# display-board.net
KiCad netlist of a schematic drawn in EAGLE
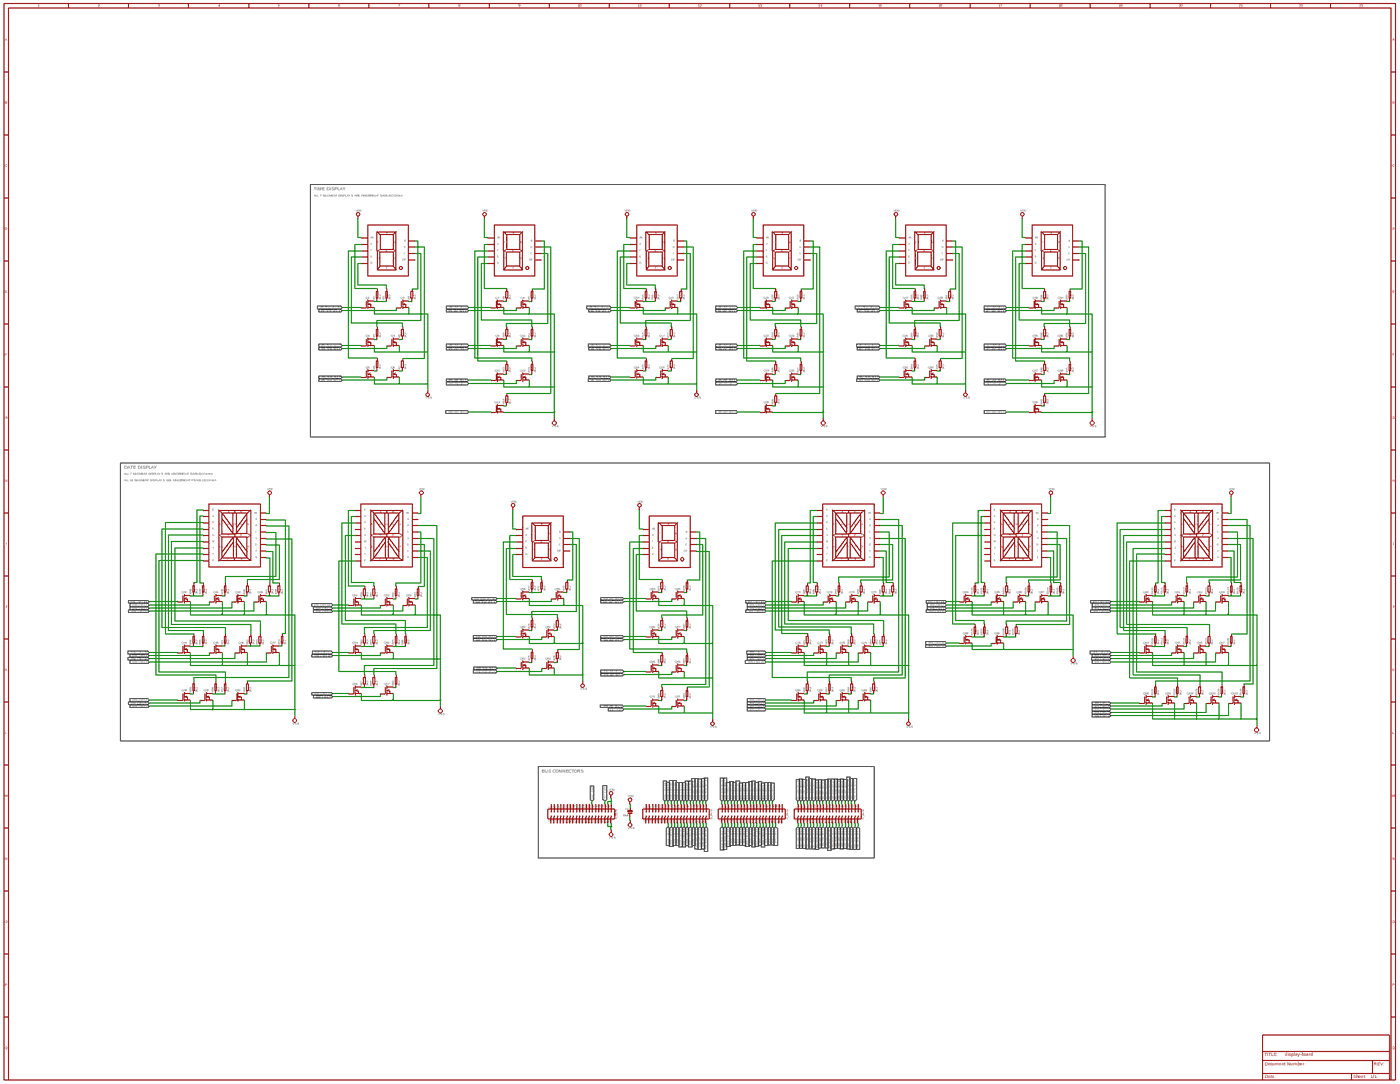
[diagram p0: schematic, sheet 1, overview]
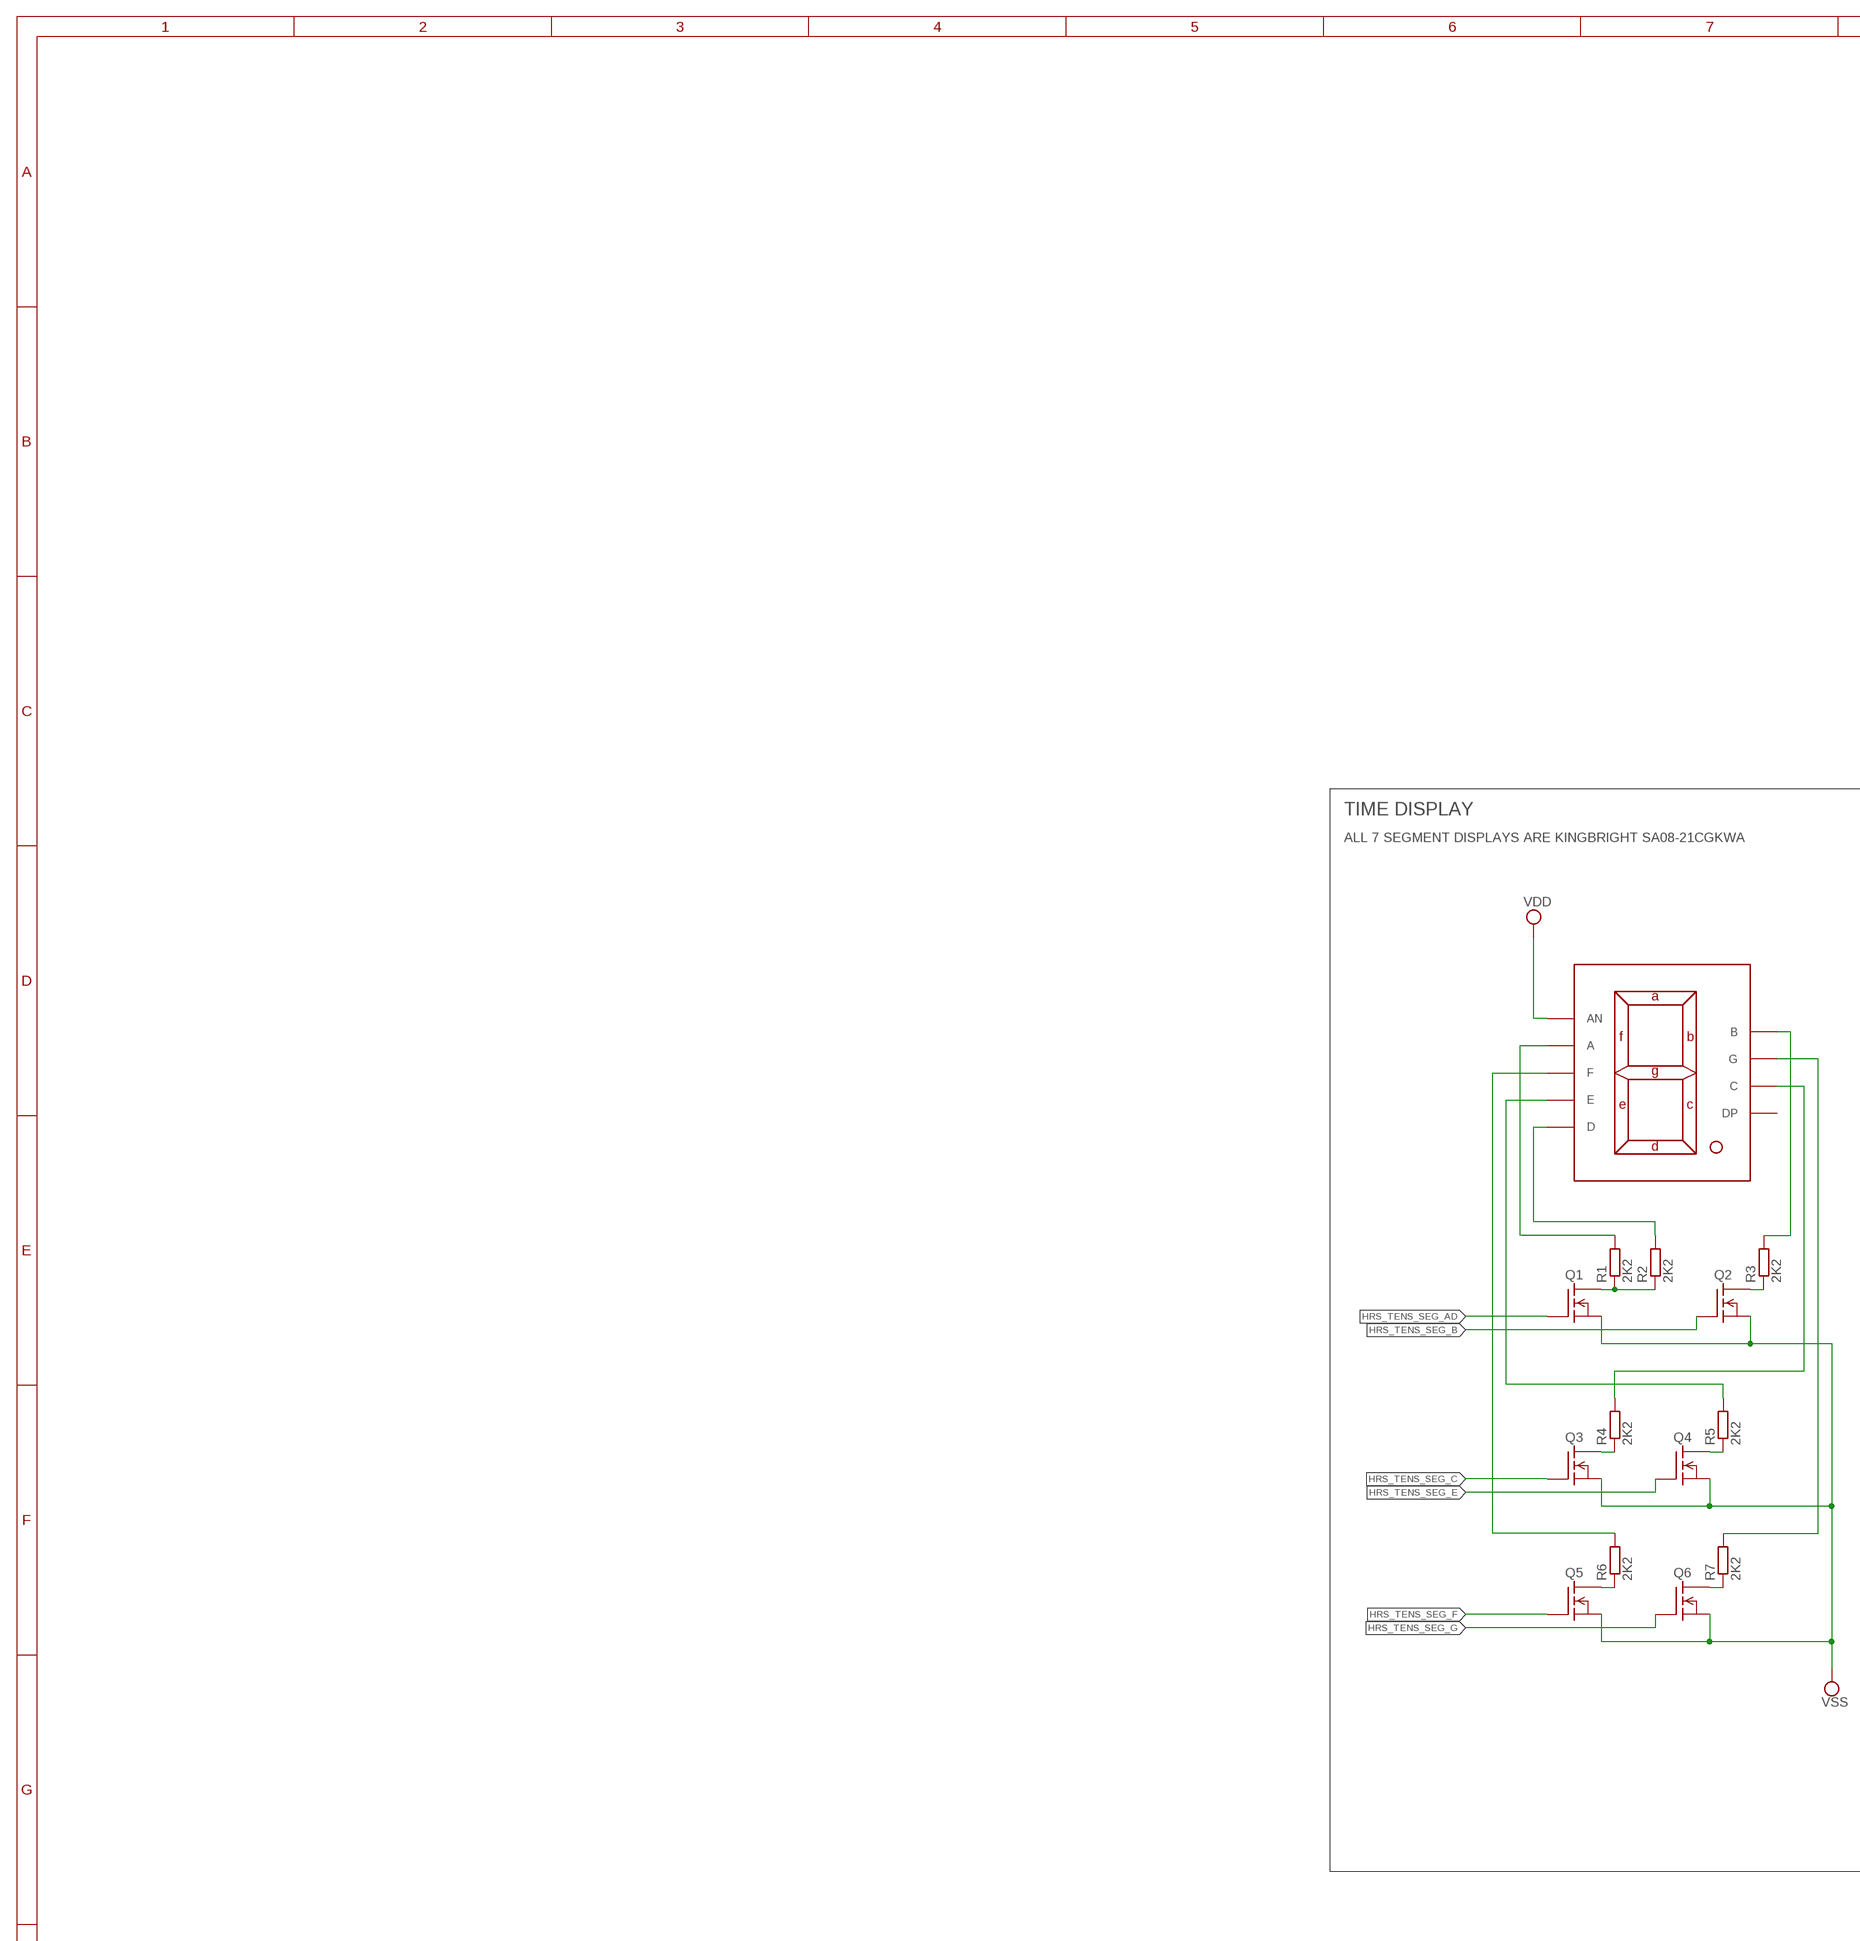
[diagram p1: schematic, sheet 1, part 1 of 6]
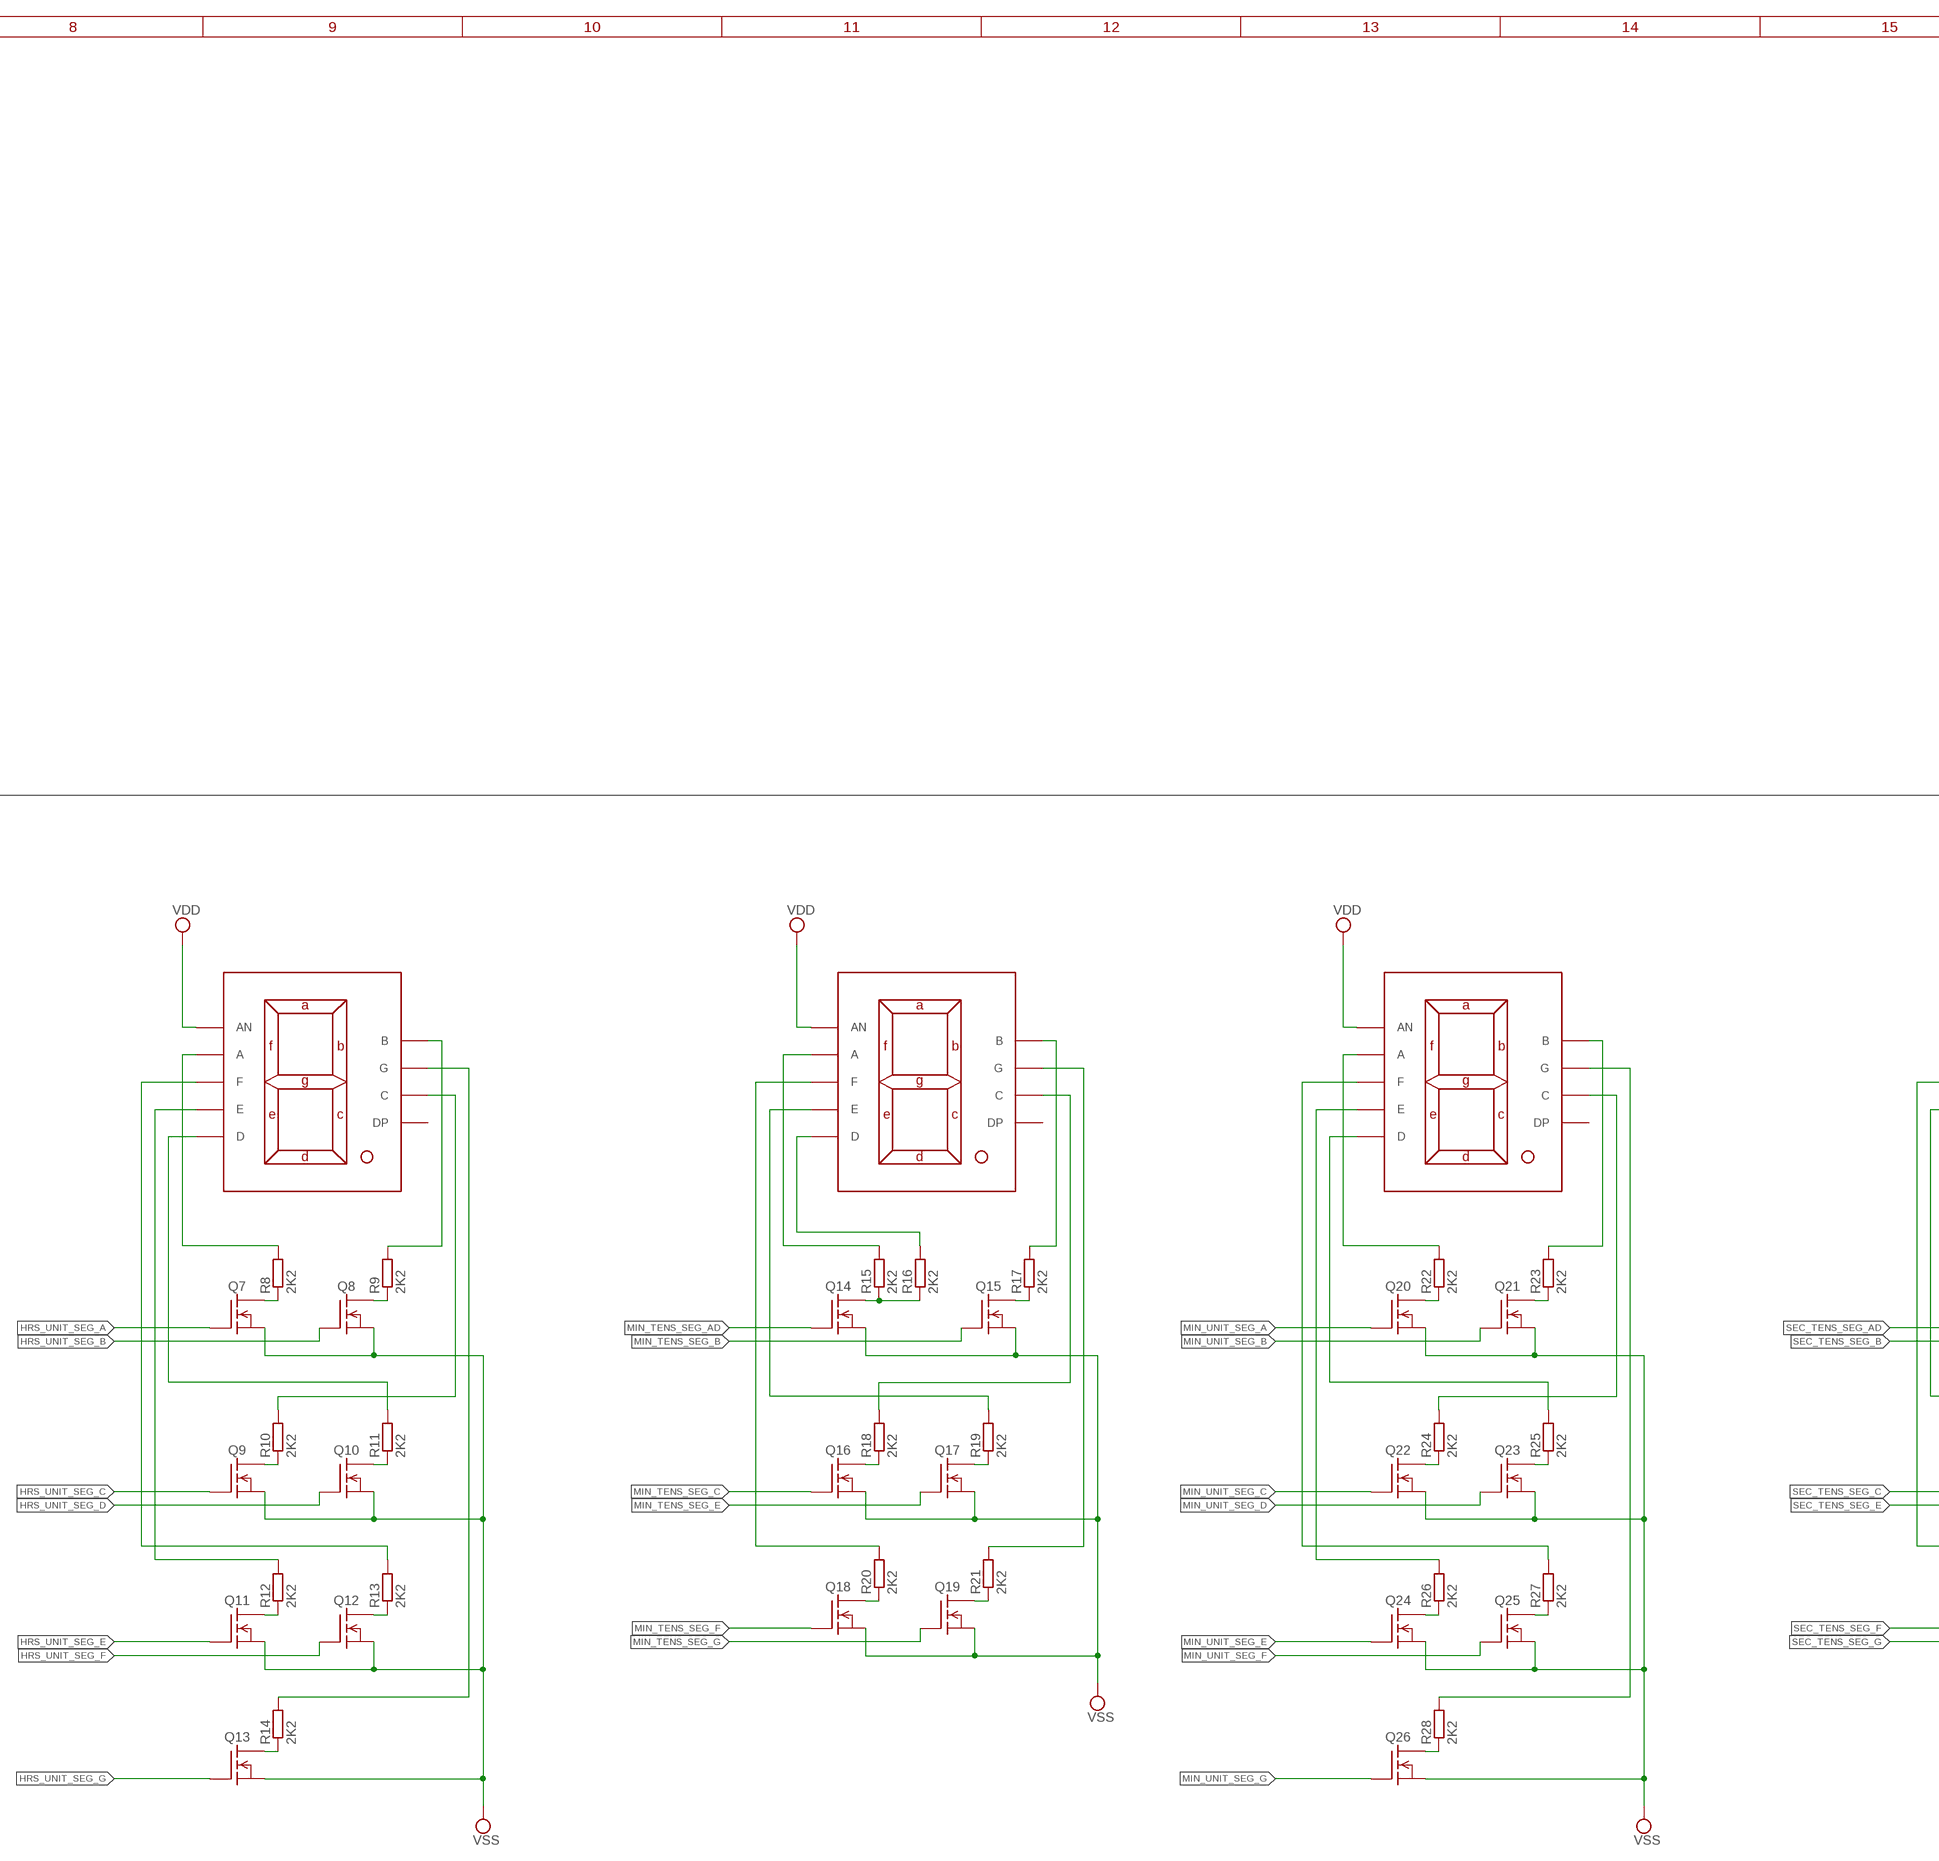
[diagram p2: schematic, sheet 1, part 2 of 6]
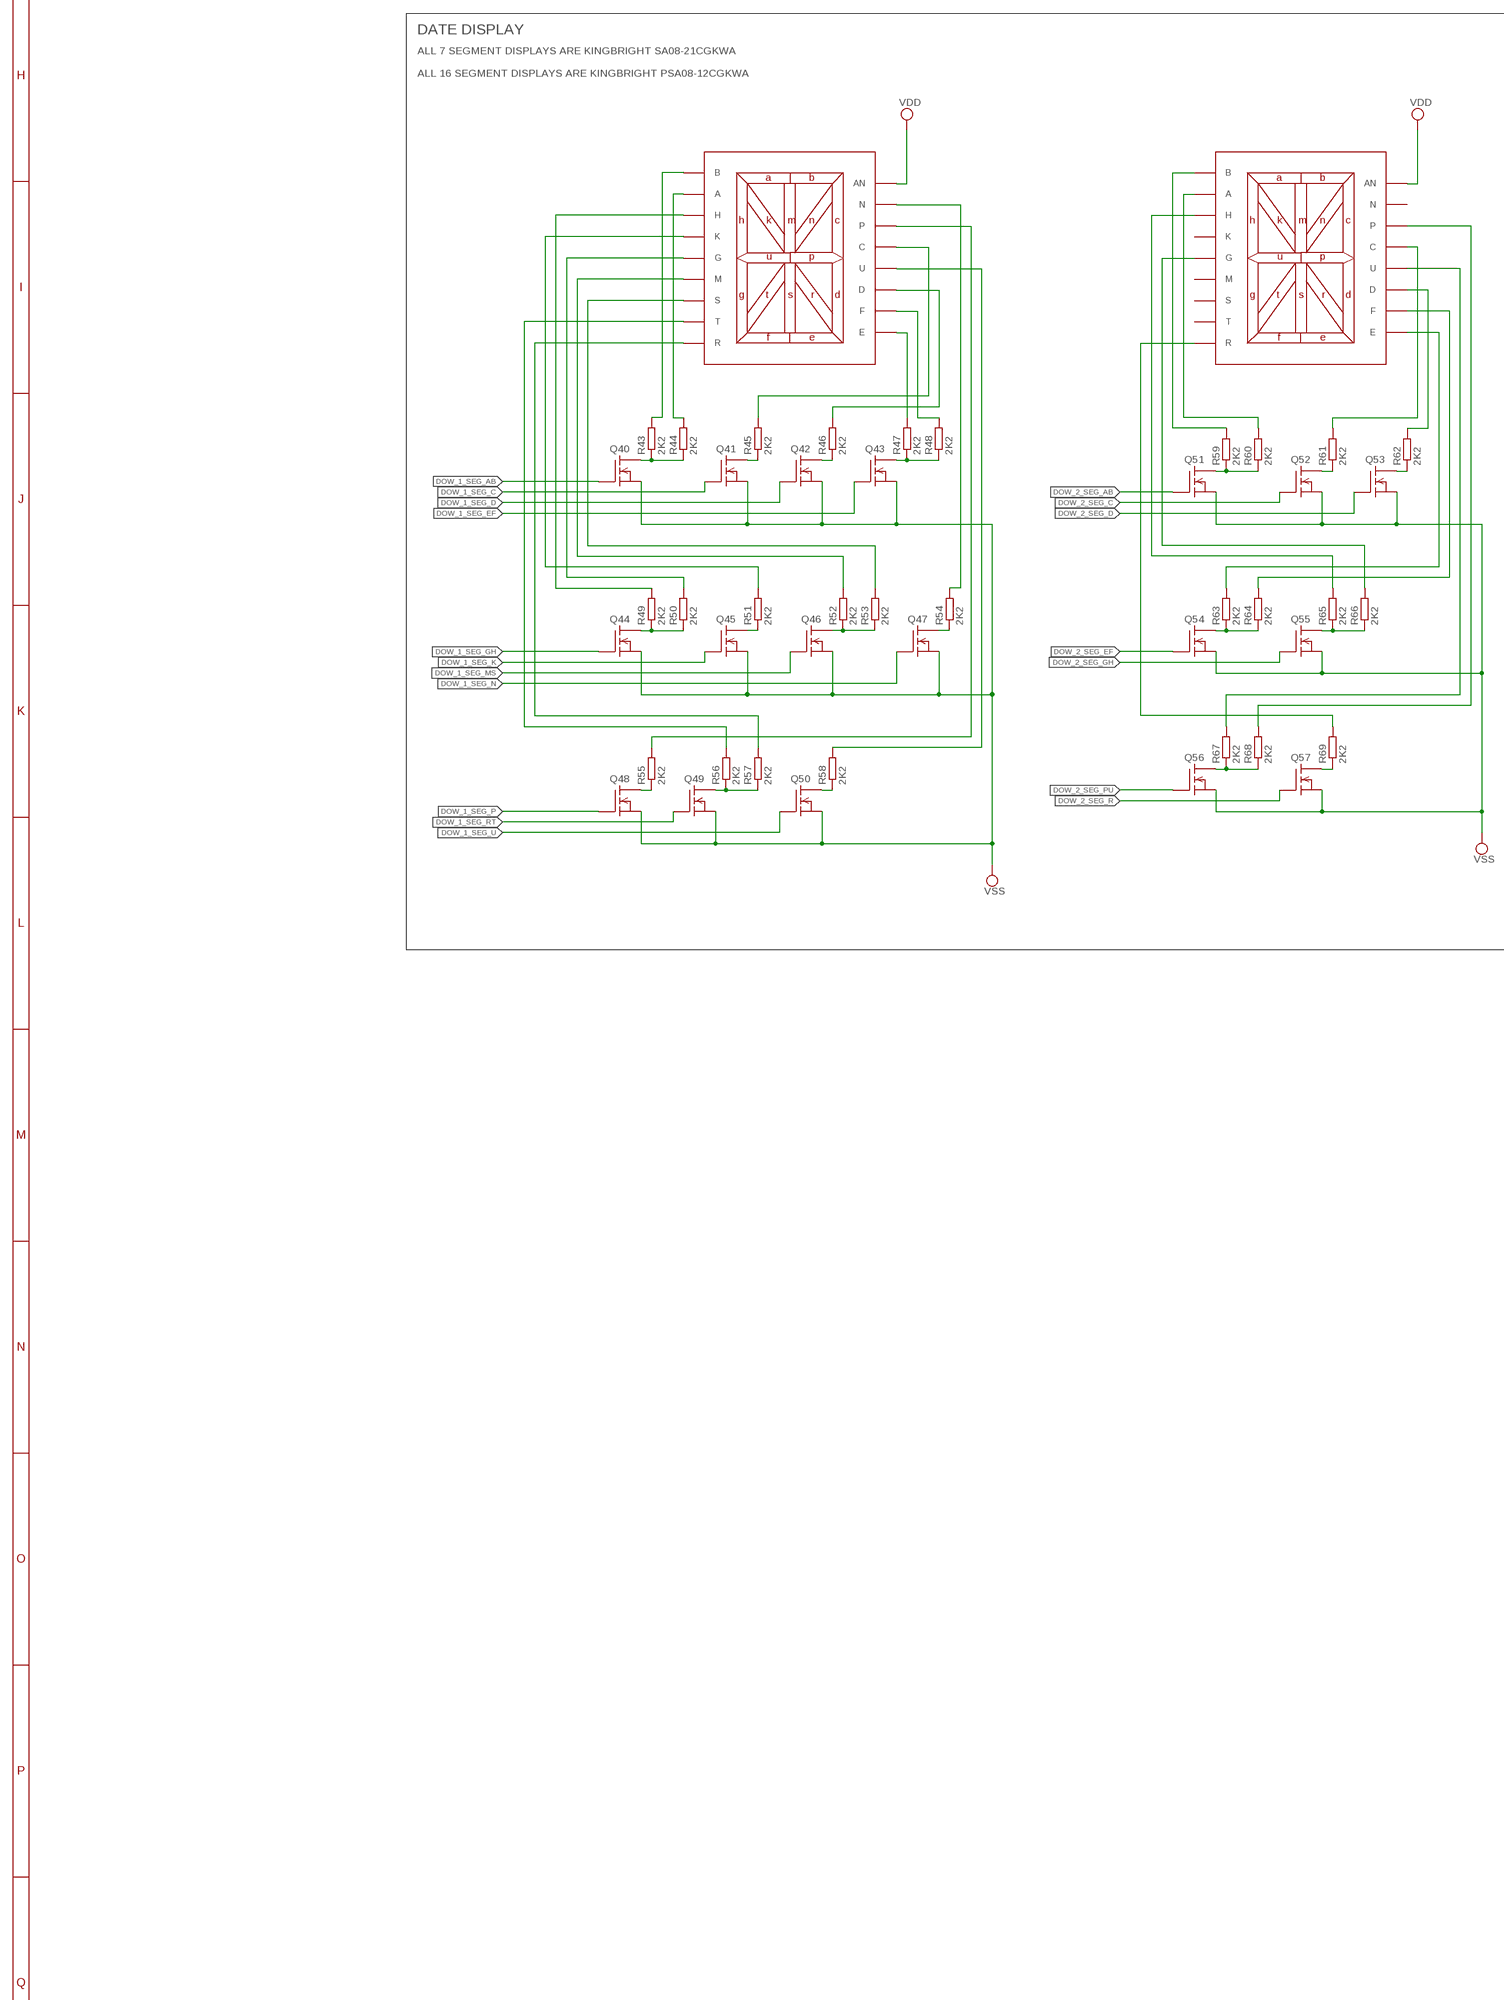
[diagram p3: schematic, sheet 1, part 3 of 6]
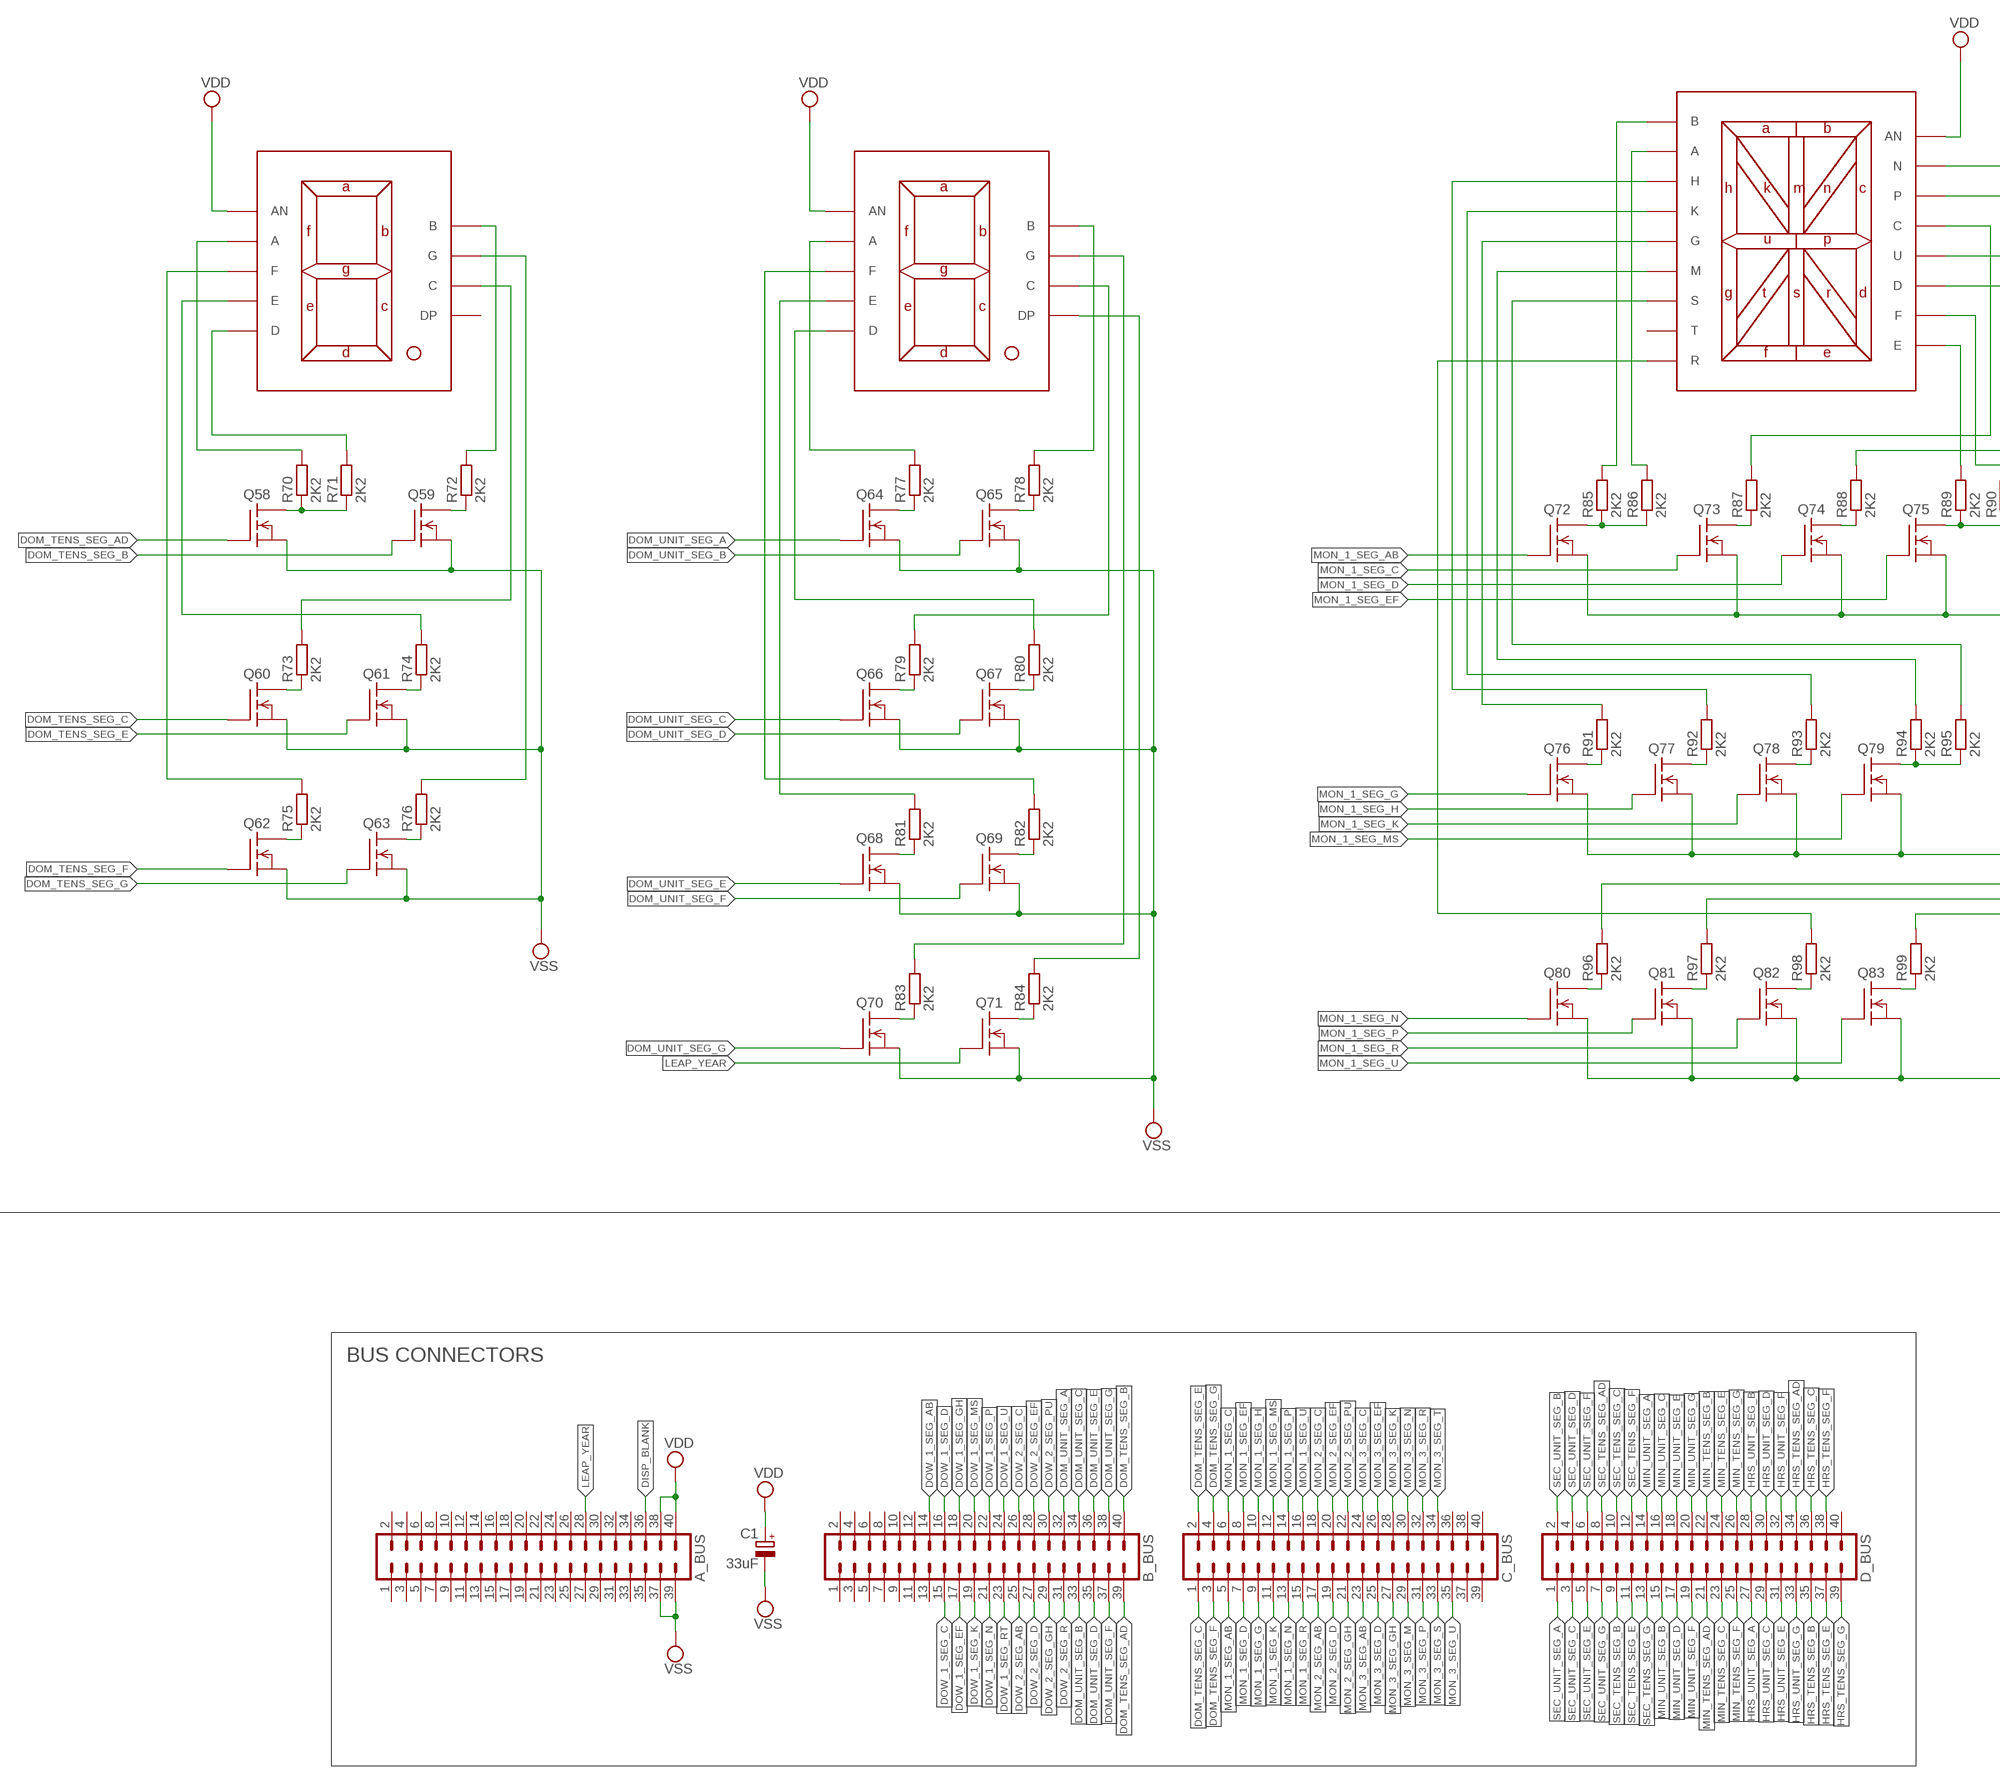
[diagram p4: schematic, sheet 1, part 4 of 6]
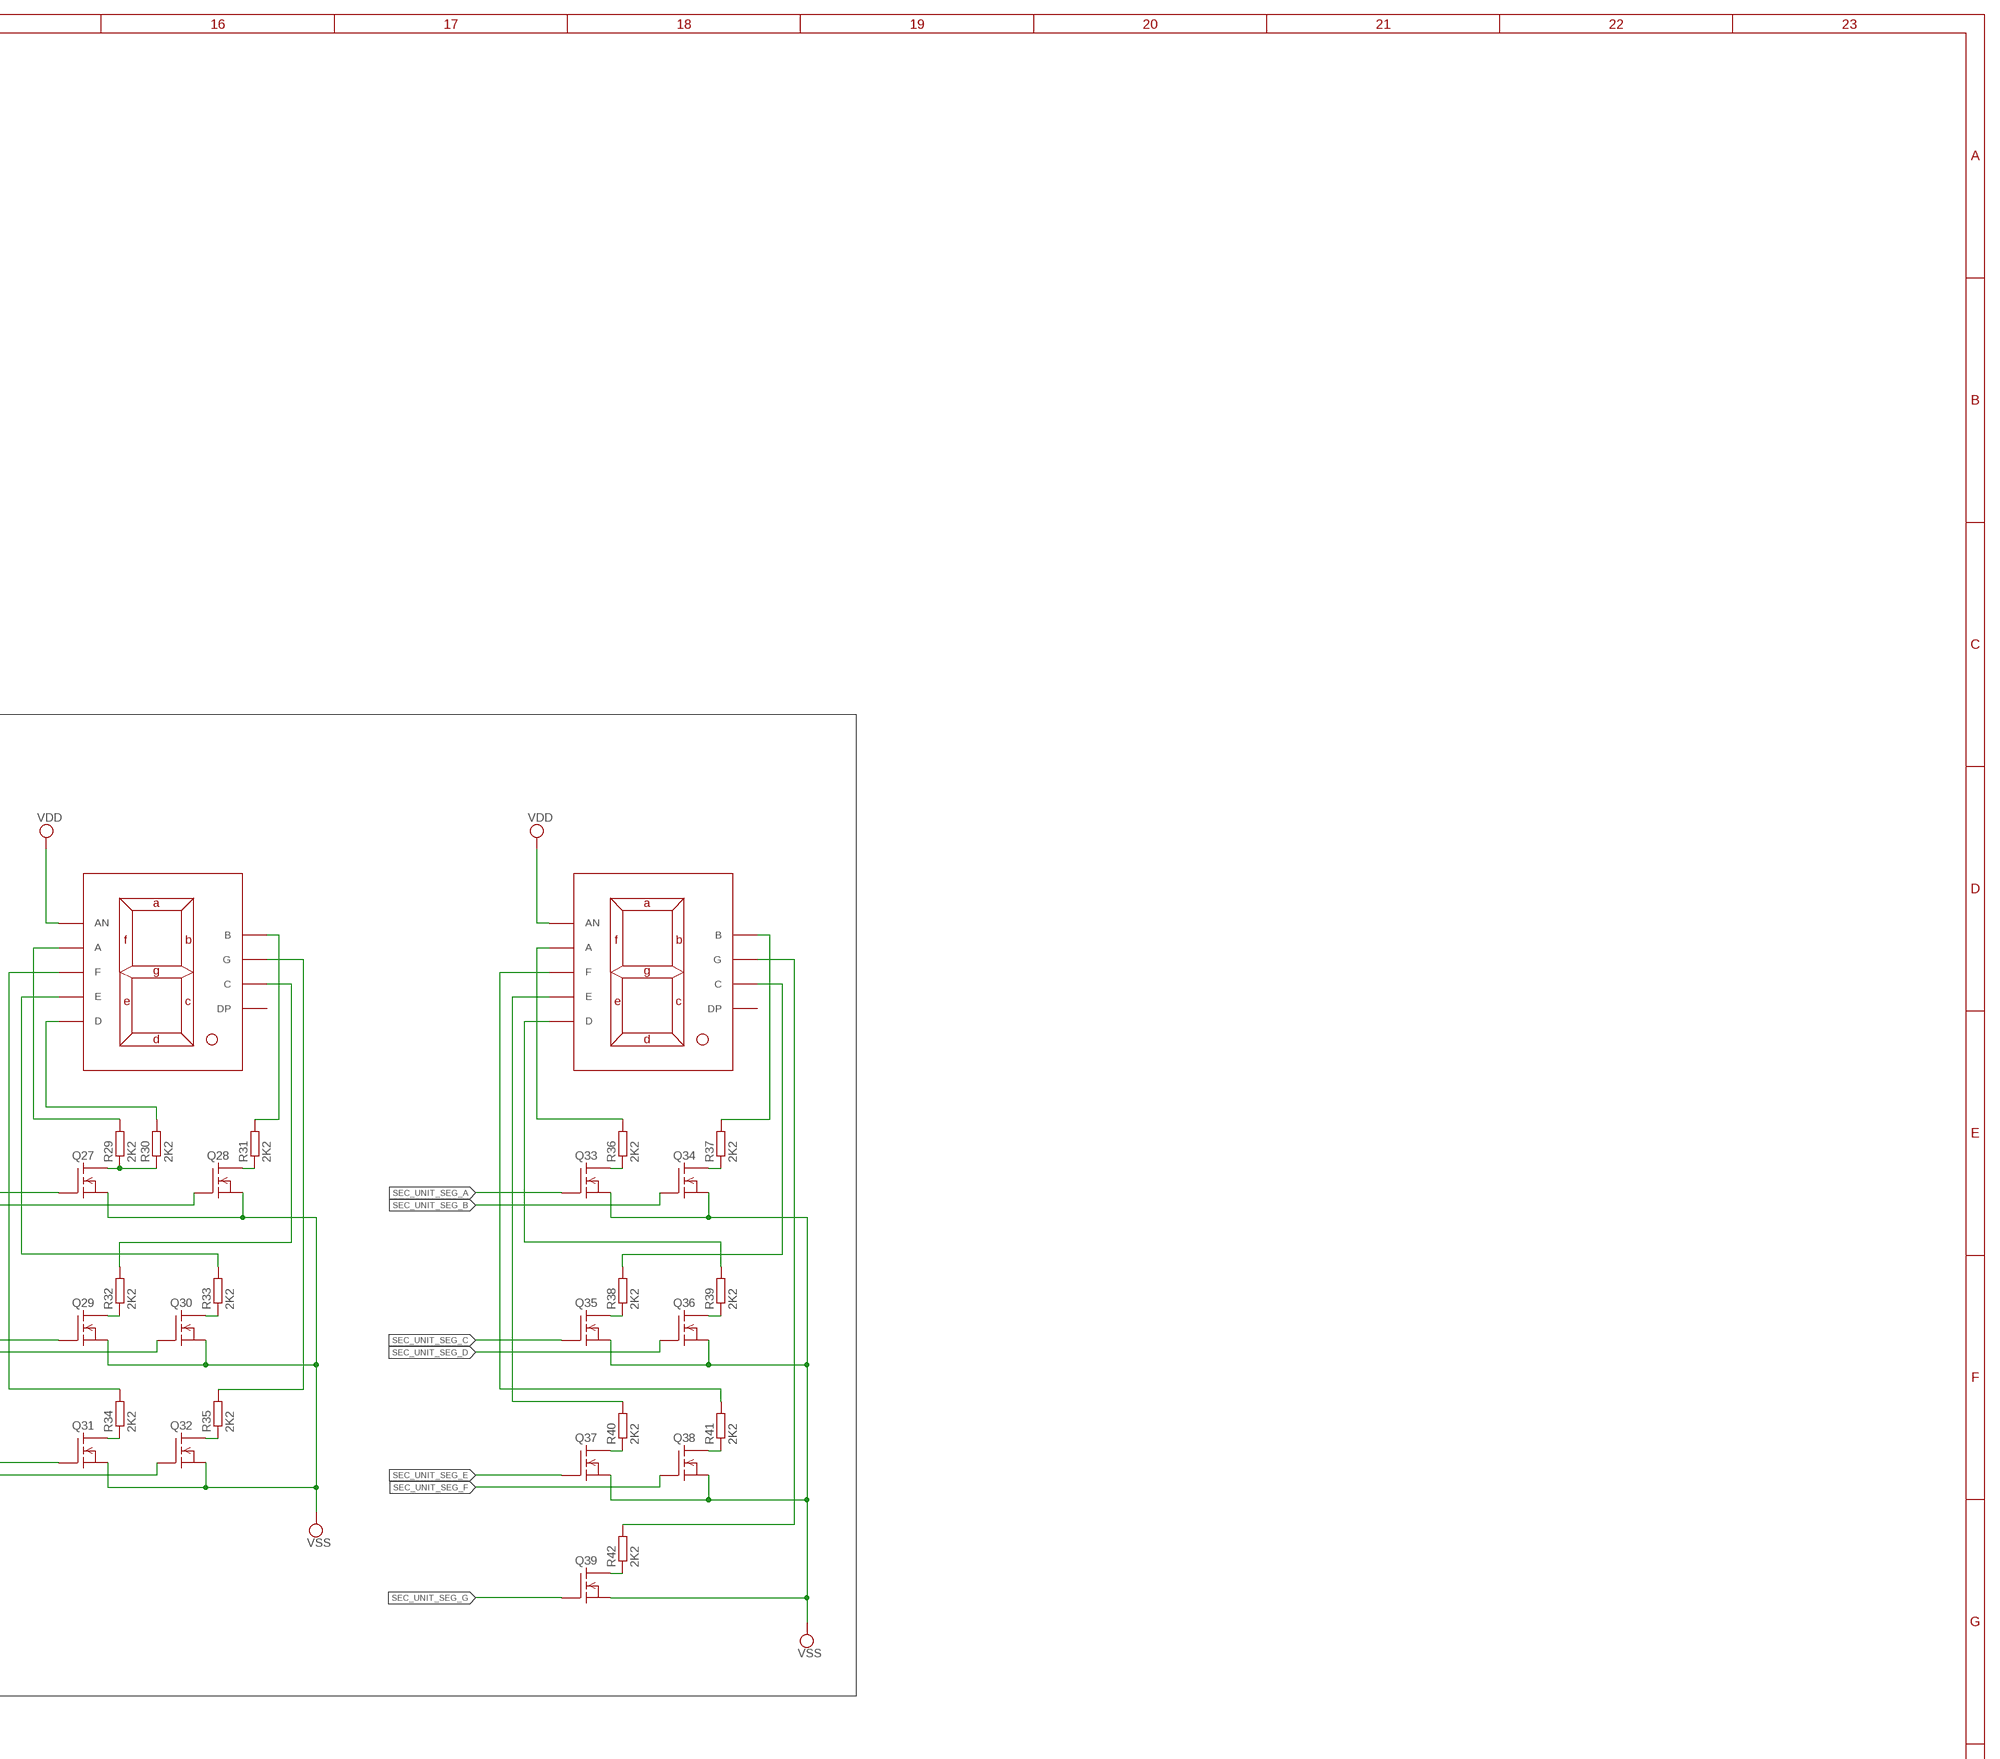
[diagram p5: schematic, sheet 1, part 5 of 6]
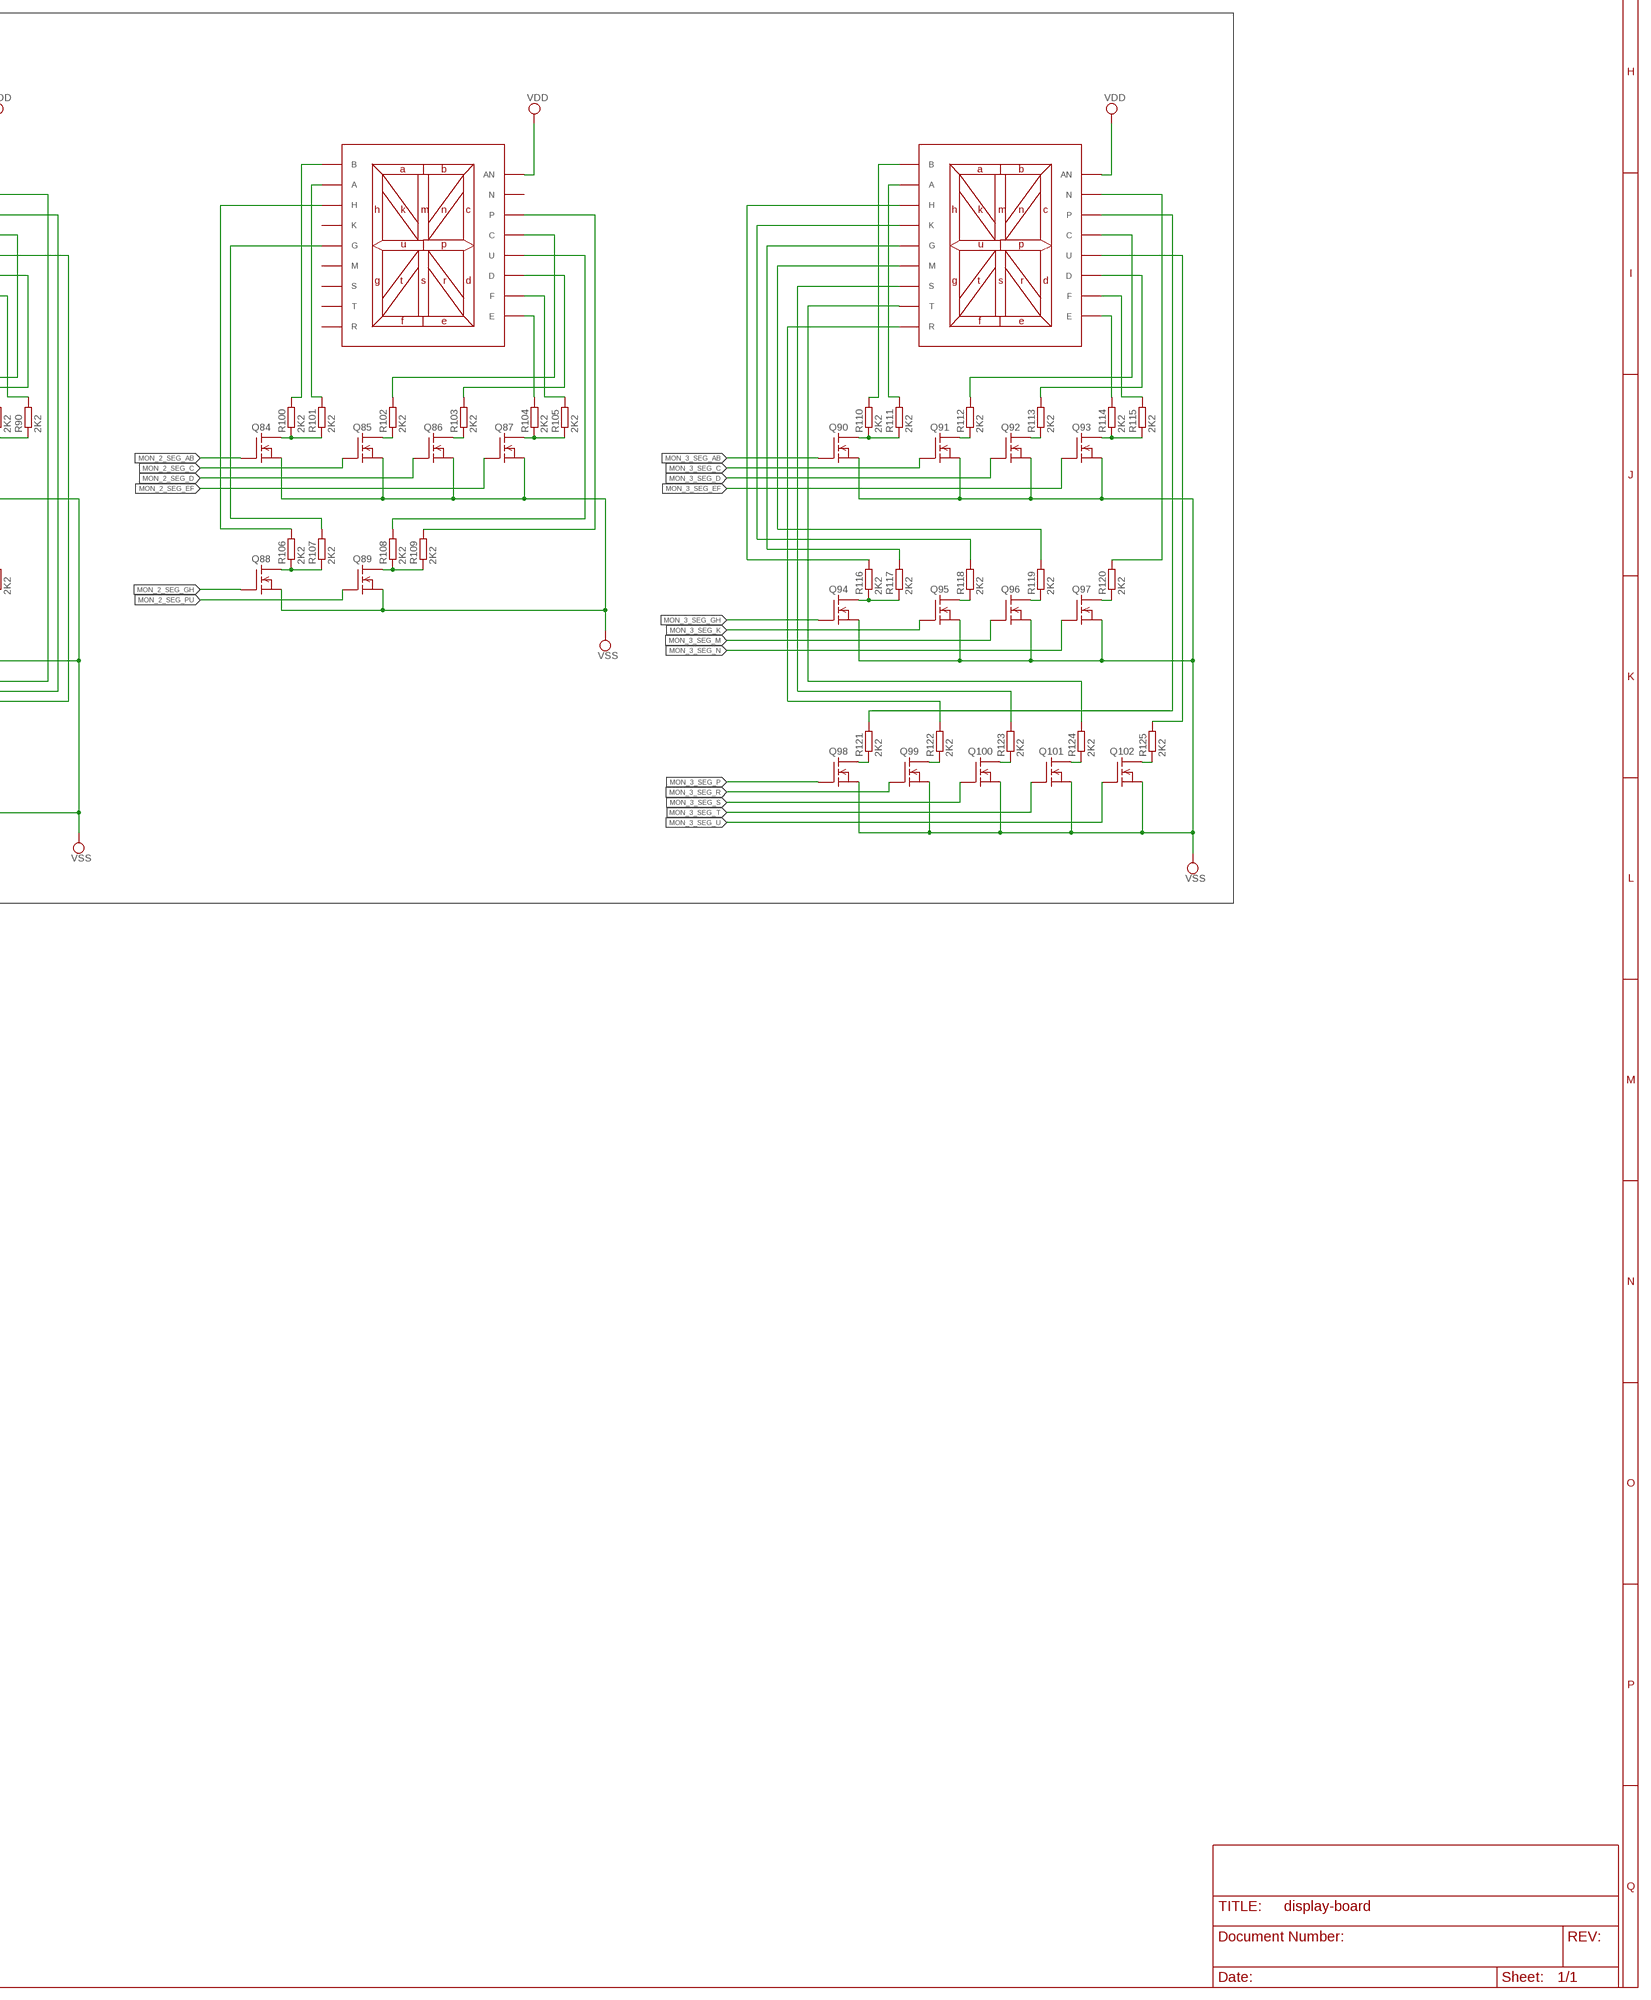
[diagram p6: schematic, sheet 1, part 6 of 6]

(export (version "E")
  (design (tool "Eeschema 10.0.6"))
  (components
    (comp (ref "A_BUS")
      (value "MA20-2")
      (footprint "eagle-import:MA20-2")
      (libsource (lib "eagle-import") (part "MA20-2"))
    )
    (comp (ref "B_BUS")
      (value "MA20-2")
      (footprint "eagle-import:MA20-2")
      (libsource (lib "eagle-import") (part "MA20-2"))
    )
    (comp (ref "C1")
      (value "33uF")
      (footprint "eagle-import:E2,5-6")
      (libsource (lib "eagle-import") (part "CPOL-EUE2.5-6"))
    )
    (comp (ref "C_BUS")
      (value "MA20-2")
      (footprint "eagle-import:MA20-2")
      (libsource (lib "eagle-import") (part "MA20-2"))
    )
    (comp (ref "D_BUS")
      (value "MA20-2")
      (footprint "eagle-import:MA20-2")
      (libsource (lib "eagle-import") (part "MA20-2"))
    )
    (comp (ref "LED1")
      (value "SA08-21CGKWA")
      (footprint "eagle-import:SA08-21CGKWA")
      (libsource (lib "eagle-import") (part "SA08-21CGKWA"))
    )
    (comp (ref "LED2")
      (value "SA08-21CGKWA")
      (footprint "eagle-import:SA08-21CGKWA")
      (libsource (lib "eagle-import") (part "SA08-21CGKWA"))
    )
    (comp (ref "LED3")
      (value "SA08-21CGKWA")
      (footprint "eagle-import:SA08-21CGKWA")
      (libsource (lib "eagle-import") (part "SA08-21CGKWA"))
    )
    (comp (ref "LED4")
      (value "SA08-21CGKWA")
      (footprint "eagle-import:SA08-21CGKWA")
      (libsource (lib "eagle-import") (part "SA08-21CGKWA"))
    )
    (comp (ref "LED5")
      (value "SA08-21CGKWA")
      (footprint "eagle-import:SA08-21CGKWA")
      (libsource (lib "eagle-import") (part "SA08-21CGKWA"))
    )
    (comp (ref "LED6")
      (value "SA08-21CGKWA")
      (footprint "eagle-import:SA08-21CGKWA")
      (libsource (lib "eagle-import") (part "SA08-21CGKWA"))
    )
    (comp (ref "LED7")
      (value "PSA08-12CGKWA")
      (footprint "eagle-import:PSA08-12CGKWA")
      (libsource (lib "eagle-import") (part "PSA08-12CGKWA"))
    )
    (comp (ref "LED8")
      (value "PSA08-12CGKWA")
      (footprint "eagle-import:PSA08-12CGKWA")
      (libsource (lib "eagle-import") (part "PSA08-12CGKWA"))
    )
    (comp (ref "LED9")
      (value "SA08-21CGKWA")
      (footprint "eagle-import:SA08-21CGKWA")
      (libsource (lib "eagle-import") (part "SA08-21CGKWA"))
    )
    (comp (ref "LED10")
      (value "SA08-21CGKWA")
      (footprint "eagle-import:SA08-21CGKWA")
      (libsource (lib "eagle-import") (part "SA08-21CGKWA"))
    )
    (comp (ref "LED11")
      (value "PSA08-12CGKWA")
      (footprint "eagle-import:PSA08-12CGKWA")
      (libsource (lib "eagle-import") (part "PSA08-12CGKWA"))
    )
    (comp (ref "LED12")
      (value "PSA08-12CGKWA")
      (footprint "eagle-import:PSA08-12CGKWA")
      (libsource (lib "eagle-import") (part "PSA08-12CGKWA"))
    )
    (comp (ref "LED13")
      (value "PSA08-12CGKWA")
      (footprint "eagle-import:PSA08-12CGKWA")
      (libsource (lib "eagle-import") (part "PSA08-12CGKWA"))
    )
    (comp (ref "Q1")
      (value "2N7000")
      (footprint "eagle-import:TO-92")
      (libsource (lib "eagle-import") (part "2N7000"))
    )
    (comp (ref "Q2")
      (value "2N7000")
      (footprint "eagle-import:TO-92")
      (libsource (lib "eagle-import") (part "2N7000"))
    )
    (comp (ref "Q3")
      (value "2N7000")
      (footprint "eagle-import:TO-92")
      (libsource (lib "eagle-import") (part "2N7000"))
    )
    (comp (ref "Q4")
      (value "2N7000")
      (footprint "eagle-import:TO-92")
      (libsource (lib "eagle-import") (part "2N7000"))
    )
    (comp (ref "Q5")
      (value "2N7000")
      (footprint "eagle-import:TO-92")
      (libsource (lib "eagle-import") (part "2N7000"))
    )
    (comp (ref "Q6")
      (value "2N7000")
      (footprint "eagle-import:TO-92")
      (libsource (lib "eagle-import") (part "2N7000"))
    )
    (comp (ref "Q7")
      (value "2N7000")
      (footprint "eagle-import:TO-92")
      (libsource (lib "eagle-import") (part "2N7000"))
    )
    (comp (ref "Q8")
      (value "2N7000")
      (footprint "eagle-import:TO-92")
      (libsource (lib "eagle-import") (part "2N7000"))
    )
    (comp (ref "Q9")
      (value "2N7000")
      (footprint "eagle-import:TO-92")
      (libsource (lib "eagle-import") (part "2N7000"))
    )
    (comp (ref "Q10")
      (value "2N7000")
      (footprint "eagle-import:TO-92")
      (libsource (lib "eagle-import") (part "2N7000"))
    )
    (comp (ref "Q11")
      (value "2N7000")
      (footprint "eagle-import:TO-92")
      (libsource (lib "eagle-import") (part "2N7000"))
    )
    (comp (ref "Q12")
      (value "2N7000")
      (footprint "eagle-import:TO-92")
      (libsource (lib "eagle-import") (part "2N7000"))
    )
    (comp (ref "Q13")
      (value "2N7000")
      (footprint "eagle-import:TO-92")
      (libsource (lib "eagle-import") (part "2N7000"))
    )
    (comp (ref "Q14")
      (value "2N7000")
      (footprint "eagle-import:TO-92")
      (libsource (lib "eagle-import") (part "2N7000"))
    )
    (comp (ref "Q15")
      (value "2N7000")
      (footprint "eagle-import:TO-92")
      (libsource (lib "eagle-import") (part "2N7000"))
    )
    (comp (ref "Q16")
      (value "2N7000")
      (footprint "eagle-import:TO-92")
      (libsource (lib "eagle-import") (part "2N7000"))
    )
    (comp (ref "Q17")
      (value "2N7000")
      (footprint "eagle-import:TO-92")
      (libsource (lib "eagle-import") (part "2N7000"))
    )
    (comp (ref "Q18")
      (value "2N7000")
      (footprint "eagle-import:TO-92")
      (libsource (lib "eagle-import") (part "2N7000"))
    )
    (comp (ref "Q19")
      (value "2N7000")
      (footprint "eagle-import:TO-92")
      (libsource (lib "eagle-import") (part "2N7000"))
    )
    (comp (ref "Q20")
      (value "2N7000")
      (footprint "eagle-import:TO-92")
      (libsource (lib "eagle-import") (part "2N7000"))
    )
    (comp (ref "Q21")
      (value "2N7000")
      (footprint "eagle-import:TO-92")
      (libsource (lib "eagle-import") (part "2N7000"))
    )
    (comp (ref "Q22")
      (value "2N7000")
      (footprint "eagle-import:TO-92")
      (libsource (lib "eagle-import") (part "2N7000"))
    )
    (comp (ref "Q23")
      (value "2N7000")
      (footprint "eagle-import:TO-92")
      (libsource (lib "eagle-import") (part "2N7000"))
    )
    (comp (ref "Q24")
      (value "2N7000")
      (footprint "eagle-import:TO-92")
      (libsource (lib "eagle-import") (part "2N7000"))
    )
    (comp (ref "Q25")
      (value "2N7000")
      (footprint "eagle-import:TO-92")
      (libsource (lib "eagle-import") (part "2N7000"))
    )
    (comp (ref "Q26")
      (value "2N7000")
      (footprint "eagle-import:TO-92")
      (libsource (lib "eagle-import") (part "2N7000"))
    )
    (comp (ref "Q27")
      (value "2N7000")
      (footprint "eagle-import:TO-92")
      (libsource (lib "eagle-import") (part "2N7000"))
    )
    (comp (ref "Q28")
      (value "2N7000")
      (footprint "eagle-import:TO-92")
      (libsource (lib "eagle-import") (part "2N7000"))
    )
    (comp (ref "Q29")
      (value "2N7000")
      (footprint "eagle-import:TO-92")
      (libsource (lib "eagle-import") (part "2N7000"))
    )
    (comp (ref "Q30")
      (value "2N7000")
      (footprint "eagle-import:TO-92")
      (libsource (lib "eagle-import") (part "2N7000"))
    )
    (comp (ref "Q31")
      (value "2N7000")
      (footprint "eagle-import:TO-92")
      (libsource (lib "eagle-import") (part "2N7000"))
    )
    (comp (ref "Q32")
      (value "2N7000")
      (footprint "eagle-import:TO-92")
      (libsource (lib "eagle-import") (part "2N7000"))
    )
    (comp (ref "Q33")
      (value "2N7000")
      (footprint "eagle-import:TO-92")
      (libsource (lib "eagle-import") (part "2N7000"))
    )
    (comp (ref "Q34")
      (value "2N7000")
      (footprint "eagle-import:TO-92")
      (libsource (lib "eagle-import") (part "2N7000"))
    )
    (comp (ref "Q35")
      (value "2N7000")
      (footprint "eagle-import:TO-92")
      (libsource (lib "eagle-import") (part "2N7000"))
    )
    (comp (ref "Q36")
      (value "2N7000")
      (footprint "eagle-import:TO-92")
      (libsource (lib "eagle-import") (part "2N7000"))
    )
    (comp (ref "Q37")
      (value "2N7000")
      (footprint "eagle-import:TO-92")
      (libsource (lib "eagle-import") (part "2N7000"))
    )
    (comp (ref "Q38")
      (value "2N7000")
      (footprint "eagle-import:TO-92")
      (libsource (lib "eagle-import") (part "2N7000"))
    )
    (comp (ref "Q39")
      (value "2N7000")
      (footprint "eagle-import:TO-92")
      (libsource (lib "eagle-import") (part "2N7000"))
    )
    (comp (ref "Q40")
      (value "2N7000")
      (footprint "eagle-import:TO-92")
      (libsource (lib "eagle-import") (part "2N7000"))
    )
    (comp (ref "Q41")
      (value "2N7000")
      (footprint "eagle-import:TO-92")
      (libsource (lib "eagle-import") (part "2N7000"))
    )
    (comp (ref "Q42")
      (value "2N7000")
      (footprint "eagle-import:TO-92")
      (libsource (lib "eagle-import") (part "2N7000"))
    )
    (comp (ref "Q43")
      (value "2N7000")
      (footprint "eagle-import:TO-92")
      (libsource (lib "eagle-import") (part "2N7000"))
    )
    (comp (ref "Q44")
      (value "2N7000")
      (footprint "eagle-import:TO-92")
      (libsource (lib "eagle-import") (part "2N7000"))
    )
    (comp (ref "Q45")
      (value "2N7000")
      (footprint "eagle-import:TO-92")
      (libsource (lib "eagle-import") (part "2N7000"))
    )
    (comp (ref "Q46")
      (value "2N7000")
      (footprint "eagle-import:TO-92")
      (libsource (lib "eagle-import") (part "2N7000"))
    )
    (comp (ref "Q47")
      (value "2N7000")
      (footprint "eagle-import:TO-92")
      (libsource (lib "eagle-import") (part "2N7000"))
    )
    (comp (ref "Q48")
      (value "2N7000")
      (footprint "eagle-import:TO-92")
      (libsource (lib "eagle-import") (part "2N7000"))
    )
    (comp (ref "Q49")
      (value "2N7000")
      (footprint "eagle-import:TO-92")
      (libsource (lib "eagle-import") (part "2N7000"))
    )
    (comp (ref "Q50")
      (value "2N7000")
      (footprint "eagle-import:TO-92")
      (libsource (lib "eagle-import") (part "2N7000"))
    )
    (comp (ref "Q51")
      (value "2N7000")
      (footprint "eagle-import:TO-92")
      (libsource (lib "eagle-import") (part "2N7000"))
    )
    (comp (ref "Q52")
      (value "2N7000")
      (footprint "eagle-import:TO-92")
      (libsource (lib "eagle-import") (part "2N7000"))
    )
    (comp (ref "Q53")
      (value "2N7000")
      (footprint "eagle-import:TO-92")
      (libsource (lib "eagle-import") (part "2N7000"))
    )
    (comp (ref "Q54")
      (value "2N7000")
      (footprint "eagle-import:TO-92")
      (libsource (lib "eagle-import") (part "2N7000"))
    )
    (comp (ref "Q55")
      (value "2N7000")
      (footprint "eagle-import:TO-92")
      (libsource (lib "eagle-import") (part "2N7000"))
    )
    (comp (ref "Q56")
      (value "2N7000")
      (footprint "eagle-import:TO-92")
      (libsource (lib "eagle-import") (part "2N7000"))
    )
    (comp (ref "Q57")
      (value "2N7000")
      (footprint "eagle-import:TO-92")
      (libsource (lib "eagle-import") (part "2N7000"))
    )
    (comp (ref "Q58")
      (value "2N7000")
      (footprint "eagle-import:TO-92")
      (libsource (lib "eagle-import") (part "2N7000"))
    )
    (comp (ref "Q59")
      (value "2N7000")
      (footprint "eagle-import:TO-92")
      (libsource (lib "eagle-import") (part "2N7000"))
    )
    (comp (ref "Q60")
      (value "2N7000")
      (footprint "eagle-import:TO-92")
      (libsource (lib "eagle-import") (part "2N7000"))
    )
    (comp (ref "Q61")
      (value "2N7000")
      (footprint "eagle-import:TO-92")
      (libsource (lib "eagle-import") (part "2N7000"))
    )
    (comp (ref "Q62")
      (value "2N7000")
      (footprint "eagle-import:TO-92")
      (libsource (lib "eagle-import") (part "2N7000"))
    )
    (comp (ref "Q63")
      (value "2N7000")
      (footprint "eagle-import:TO-92")
      (libsource (lib "eagle-import") (part "2N7000"))
    )
    (comp (ref "Q64")
      (value "2N7000")
      (footprint "eagle-import:TO-92")
      (libsource (lib "eagle-import") (part "2N7000"))
    )
    (comp (ref "Q65")
      (value "2N7000")
      (footprint "eagle-import:TO-92")
      (libsource (lib "eagle-import") (part "2N7000"))
    )
    (comp (ref "Q66")
      (value "2N7000")
      (footprint "eagle-import:TO-92")
      (libsource (lib "eagle-import") (part "2N7000"))
    )
    (comp (ref "Q67")
      (value "2N7000")
      (footprint "eagle-import:TO-92")
      (libsource (lib "eagle-import") (part "2N7000"))
    )
    (comp (ref "Q68")
      (value "2N7000")
      (footprint "eagle-import:TO-92")
      (libsource (lib "eagle-import") (part "2N7000"))
    )
    (comp (ref "Q69")
      (value "2N7000")
      (footprint "eagle-import:TO-92")
      (libsource (lib "eagle-import") (part "2N7000"))
    )
    (comp (ref "Q70")
      (value "2N7000")
      (footprint "eagle-import:TO-92")
      (libsource (lib "eagle-import") (part "2N7000"))
    )
    (comp (ref "Q71")
      (value "2N7000")
      (footprint "eagle-import:TO-92")
      (libsource (lib "eagle-import") (part "2N7000"))
    )
    (comp (ref "Q72")
      (value "2N7000")
      (footprint "eagle-import:TO-92")
      (libsource (lib "eagle-import") (part "2N7000"))
    )
    (comp (ref "Q73")
      (value "2N7000")
      (footprint "eagle-import:TO-92")
      (libsource (lib "eagle-import") (part "2N7000"))
    )
    (comp (ref "Q74")
      (value "2N7000")
      (footprint "eagle-import:TO-92")
      (libsource (lib "eagle-import") (part "2N7000"))
    )
    (comp (ref "Q75")
      (value "2N7000")
      (footprint "eagle-import:TO-92")
      (libsource (lib "eagle-import") (part "2N7000"))
    )
    (comp (ref "Q76")
      (value "2N7000")
      (footprint "eagle-import:TO-92")
      (libsource (lib "eagle-import") (part "2N7000"))
    )
    (comp (ref "Q77")
      (value "2N7000")
      (footprint "eagle-import:TO-92")
      (libsource (lib "eagle-import") (part "2N7000"))
    )
    (comp (ref "Q78")
      (value "2N7000")
      (footprint "eagle-import:TO-92")
      (libsource (lib "eagle-import") (part "2N7000"))
    )
    (comp (ref "Q79")
      (value "2N7000")
      (footprint "eagle-import:TO-92")
      (libsource (lib "eagle-import") (part "2N7000"))
    )
    (comp (ref "Q80")
      (value "2N7000")
      (footprint "eagle-import:TO-92")
      (libsource (lib "eagle-import") (part "2N7000"))
    )
    (comp (ref "Q81")
      (value "2N7000")
      (footprint "eagle-import:TO-92")
      (libsource (lib "eagle-import") (part "2N7000"))
    )
    (comp (ref "Q82")
      (value "2N7000")
      (footprint "eagle-import:TO-92")
      (libsource (lib "eagle-import") (part "2N7000"))
    )
    (comp (ref "Q83")
      (value "2N7000")
      (footprint "eagle-import:TO-92")
      (libsource (lib "eagle-import") (part "2N7000"))
    )
    (comp (ref "Q84")
      (value "2N7000")
      (footprint "eagle-import:TO-92")
      (libsource (lib "eagle-import") (part "2N7000"))
    )
    (comp (ref "Q85")
      (value "2N7000")
      (footprint "eagle-import:TO-92")
      (libsource (lib "eagle-import") (part "2N7000"))
    )
    (comp (ref "Q86")
      (value "2N7000")
      (footprint "eagle-import:TO-92")
      (libsource (lib "eagle-import") (part "2N7000"))
    )
    (comp (ref "Q87")
      (value "2N7000")
      (footprint "eagle-import:TO-92")
      (libsource (lib "eagle-import") (part "2N7000"))
    )
    (comp (ref "Q88")
      (value "2N7000")
      (footprint "eagle-import:TO-92")
      (libsource (lib "eagle-import") (part "2N7000"))
    )
    (comp (ref "Q89")
      (value "2N7000")
      (footprint "eagle-import:TO-92")
      (libsource (lib "eagle-import") (part "2N7000"))
    )
    (comp (ref "Q90")
      (value "2N7000")
      (footprint "eagle-import:TO-92")
      (libsource (lib "eagle-import") (part "2N7000"))
    )
    (comp (ref "Q91")
      (value "2N7000")
      (footprint "eagle-import:TO-92")
      (libsource (lib "eagle-import") (part "2N7000"))
    )
    (comp (ref "Q92")
      (value "2N7000")
      (footprint "eagle-import:TO-92")
      (libsource (lib "eagle-import") (part "2N7000"))
    )
    (comp (ref "Q93")
      (value "2N7000")
      (footprint "eagle-import:TO-92")
      (libsource (lib "eagle-import") (part "2N7000"))
    )
    (comp (ref "Q94")
      (value "2N7000")
      (footprint "eagle-import:TO-92")
      (libsource (lib "eagle-import") (part "2N7000"))
    )
    (comp (ref "Q95")
      (value "2N7000")
      (footprint "eagle-import:TO-92")
      (libsource (lib "eagle-import") (part "2N7000"))
    )
    (comp (ref "Q96")
      (value "2N7000")
      (footprint "eagle-import:TO-92")
      (libsource (lib "eagle-import") (part "2N7000"))
    )
    (comp (ref "Q97")
      (value "2N7000")
      (footprint "eagle-import:TO-92")
      (libsource (lib "eagle-import") (part "2N7000"))
    )
    (comp (ref "Q98")
      (value "2N7000")
      (footprint "eagle-import:TO-92")
      (libsource (lib "eagle-import") (part "2N7000"))
    )
    (comp (ref "Q99")
      (value "2N7000")
      (footprint "eagle-import:TO-92")
      (libsource (lib "eagle-import") (part "2N7000"))
    )
    (comp (ref "Q100")
      (value "2N7000")
      (footprint "eagle-import:TO-92")
      (libsource (lib "eagle-import") (part "2N7000"))
    )
    (comp (ref "Q101")
      (value "2N7000")
      (footprint "eagle-import:TO-92")
      (libsource (lib "eagle-import") (part "2N7000"))
    )
    (comp (ref "Q102")
      (value "2N7000")
      (footprint "eagle-import:TO-92")
      (libsource (lib "eagle-import") (part "2N7000"))
    )
    (comp (ref "R1")
      (value "2K2")
      (footprint "eagle-import:0207_2V")
      (libsource (lib "eagle-import") (part "R-EU_0207/2V"))
    )
    (comp (ref "R2")
      (value "2K2")
      (footprint "eagle-import:0207_2V")
      (libsource (lib "eagle-import") (part "R-EU_0207/2V"))
    )
    (comp (ref "R3")
      (value "2K2")
      (footprint "eagle-import:0207_2V")
      (libsource (lib "eagle-import") (part "R-EU_0207/2V"))
    )
    (comp (ref "R4")
      (value "2K2")
      (footprint "eagle-import:0207_2V")
      (libsource (lib "eagle-import") (part "R-EU_0207/2V"))
    )
    (comp (ref "R5")
      (value "2K2")
      (footprint "eagle-import:0207_2V")
      (libsource (lib "eagle-import") (part "R-EU_0207/2V"))
    )
    (comp (ref "R6")
      (value "2K2")
      (footprint "eagle-import:0207_2V")
      (libsource (lib "eagle-import") (part "R-EU_0207/2V"))
    )
    (comp (ref "R7")
      (value "2K2")
      (footprint "eagle-import:0207_2V")
      (libsource (lib "eagle-import") (part "R-EU_0207/2V"))
    )
    (comp (ref "R8")
      (value "2K2")
      (footprint "eagle-import:0207_2V")
      (libsource (lib "eagle-import") (part "R-EU_0207/2V"))
    )
    (comp (ref "R9")
      (value "2K2")
      (footprint "eagle-import:0207_2V")
      (libsource (lib "eagle-import") (part "R-EU_0207/2V"))
    )
    (comp (ref "R10")
      (value "2K2")
      (footprint "eagle-import:0207_2V")
      (libsource (lib "eagle-import") (part "R-EU_0207/2V"))
    )
    (comp (ref "R11")
      (value "2K2")
      (footprint "eagle-import:0207_2V")
      (libsource (lib "eagle-import") (part "R-EU_0207/2V"))
    )
    (comp (ref "R12")
      (value "2K2")
      (footprint "eagle-import:0207_2V")
      (libsource (lib "eagle-import") (part "R-EU_0207/2V"))
    )
    (comp (ref "R13")
      (value "2K2")
      (footprint "eagle-import:0207_2V")
      (libsource (lib "eagle-import") (part "R-EU_0207/2V"))
    )
    (comp (ref "R14")
      (value "2K2")
      (footprint "eagle-import:0207_2V")
      (libsource (lib "eagle-import") (part "R-EU_0207/2V"))
    )
    (comp (ref "R15")
      (value "2K2")
      (footprint "eagle-import:0207_2V")
      (libsource (lib "eagle-import") (part "R-EU_0207/2V"))
    )
    (comp (ref "R16")
      (value "2K2")
      (footprint "eagle-import:0207_2V")
      (libsource (lib "eagle-import") (part "R-EU_0207/2V"))
    )
    (comp (ref "R17")
      (value "2K2")
      (footprint "eagle-import:0207_2V")
      (libsource (lib "eagle-import") (part "R-EU_0207/2V"))
    )
    (comp (ref "R18")
      (value "2K2")
      (footprint "eagle-import:0207_2V")
      (libsource (lib "eagle-import") (part "R-EU_0207/2V"))
    )
    (comp (ref "R19")
      (value "2K2")
      (footprint "eagle-import:0207_2V")
      (libsource (lib "eagle-import") (part "R-EU_0207/2V"))
    )
    (comp (ref "R20")
      (value "2K2")
      (footprint "eagle-import:0207_2V")
      (libsource (lib "eagle-import") (part "R-EU_0207/2V"))
    )
    (comp (ref "R21")
      (value "2K2")
      (footprint "eagle-import:0207_2V")
      (libsource (lib "eagle-import") (part "R-EU_0207/2V"))
    )
    (comp (ref "R22")
      (value "2K2")
      (footprint "eagle-import:0207_2V")
      (libsource (lib "eagle-import") (part "R-EU_0207/2V"))
    )
    (comp (ref "R23")
      (value "2K2")
      (footprint "eagle-import:0207_2V")
      (libsource (lib "eagle-import") (part "R-EU_0207/2V"))
    )
    (comp (ref "R24")
      (value "2K2")
      (footprint "eagle-import:0207_2V")
      (libsource (lib "eagle-import") (part "R-EU_0207/2V"))
    )
    (comp (ref "R25")
      (value "2K2")
      (footprint "eagle-import:0207_2V")
      (libsource (lib "eagle-import") (part "R-EU_0207/2V"))
    )
    (comp (ref "R26")
      (value "2K2")
      (footprint "eagle-import:0207_2V")
      (libsource (lib "eagle-import") (part "R-EU_0207/2V"))
    )
    (comp (ref "R27")
      (value "2K2")
      (footprint "eagle-import:0207_2V")
      (libsource (lib "eagle-import") (part "R-EU_0207/2V"))
    )
    (comp (ref "R28")
      (value "2K2")
      (footprint "eagle-import:0207_2V")
      (libsource (lib "eagle-import") (part "R-EU_0207/2V"))
    )
    (comp (ref "R29")
      (value "2K2")
      (footprint "eagle-import:0207_2V")
      (libsource (lib "eagle-import") (part "R-EU_0207/2V"))
    )
    (comp (ref "R30")
      (value "2K2")
      (footprint "eagle-import:0207_2V")
      (libsource (lib "eagle-import") (part "R-EU_0207/2V"))
    )
    (comp (ref "R31")
      (value "2K2")
      (footprint "eagle-import:0207_2V")
      (libsource (lib "eagle-import") (part "R-EU_0207/2V"))
    )
    (comp (ref "R32")
      (value "2K2")
      (footprint "eagle-import:0207_2V")
      (libsource (lib "eagle-import") (part "R-EU_0207/2V"))
    )
    (comp (ref "R33")
      (value "2K2")
      (footprint "eagle-import:0207_2V")
      (libsource (lib "eagle-import") (part "R-EU_0207/2V"))
    )
    (comp (ref "R34")
      (value "2K2")
      (footprint "eagle-import:0207_2V")
      (libsource (lib "eagle-import") (part "R-EU_0207/2V"))
    )
    (comp (ref "R35")
      (value "2K2")
      (footprint "eagle-import:0207_2V")
      (libsource (lib "eagle-import") (part "R-EU_0207/2V"))
    )
    (comp (ref "R36")
      (value "2K2")
      (footprint "eagle-import:0207_2V")
      (libsource (lib "eagle-import") (part "R-EU_0207/2V"))
    )
    (comp (ref "R37")
      (value "2K2")
      (footprint "eagle-import:0207_2V")
      (libsource (lib "eagle-import") (part "R-EU_0207/2V"))
    )
    (comp (ref "R38")
      (value "2K2")
      (footprint "eagle-import:0207_2V")
      (libsource (lib "eagle-import") (part "R-EU_0207/2V"))
    )
    (comp (ref "R39")
      (value "2K2")
      (footprint "eagle-import:0207_2V")
      (libsource (lib "eagle-import") (part "R-EU_0207/2V"))
    )
    (comp (ref "R40")
      (value "2K2")
      (footprint "eagle-import:0207_2V")
      (libsource (lib "eagle-import") (part "R-EU_0207/2V"))
    )
    (comp (ref "R41")
      (value "2K2")
      (footprint "eagle-import:0207_2V")
      (libsource (lib "eagle-import") (part "R-EU_0207/2V"))
    )
    (comp (ref "R42")
      (value "2K2")
      (footprint "eagle-import:0207_2V")
      (libsource (lib "eagle-import") (part "R-EU_0207/2V"))
    )
    (comp (ref "R43")
      (value "2K2")
      (footprint "eagle-import:0207_2V")
      (libsource (lib "eagle-import") (part "R-EU_0207/2V"))
    )
    (comp (ref "R44")
      (value "2K2")
      (footprint "eagle-import:0207_2V")
      (libsource (lib "eagle-import") (part "R-EU_0207/2V"))
    )
    (comp (ref "R45")
      (value "2K2")
      (footprint "eagle-import:0207_2V")
      (libsource (lib "eagle-import") (part "R-EU_0207/2V"))
    )
    (comp (ref "R46")
      (value "2K2")
      (footprint "eagle-import:0207_2V")
      (libsource (lib "eagle-import") (part "R-EU_0207/2V"))
    )
    (comp (ref "R47")
      (value "2K2")
      (footprint "eagle-import:0207_2V")
      (libsource (lib "eagle-import") (part "R-EU_0207/2V"))
    )
    (comp (ref "R48")
      (value "2K2")
      (footprint "eagle-import:0207_2V")
      (libsource (lib "eagle-import") (part "R-EU_0207/2V"))
    )
    (comp (ref "R49")
      (value "2K2")
      (footprint "eagle-import:0207_2V")
      (libsource (lib "eagle-import") (part "R-EU_0207/2V"))
    )
    (comp (ref "R50")
      (value "2K2")
      (footprint "eagle-import:0207_2V")
      (libsource (lib "eagle-import") (part "R-EU_0207/2V"))
    )
    (comp (ref "R51")
      (value "2K2")
      (footprint "eagle-import:0207_2V")
      (libsource (lib "eagle-import") (part "R-EU_0207/2V"))
    )
    (comp (ref "R52")
      (value "2K2")
      (footprint "eagle-import:0207_2V")
      (libsource (lib "eagle-import") (part "R-EU_0207/2V"))
    )
    (comp (ref "R53")
      (value "2K2")
      (footprint "eagle-import:0207_2V")
      (libsource (lib "eagle-import") (part "R-EU_0207/2V"))
    )
    (comp (ref "R54")
      (value "2K2")
      (footprint "eagle-import:0207_2V")
      (libsource (lib "eagle-import") (part "R-EU_0207/2V"))
    )
    (comp (ref "R55")
      (value "2K2")
      (footprint "eagle-import:0207_2V")
      (libsource (lib "eagle-import") (part "R-EU_0207/2V"))
    )
    (comp (ref "R56")
      (value "2K2")
      (footprint "eagle-import:0207_2V")
      (libsource (lib "eagle-import") (part "R-EU_0207/2V"))
    )
    (comp (ref "R57")
      (value "2K2")
      (footprint "eagle-import:0207_2V")
      (libsource (lib "eagle-import") (part "R-EU_0207/2V"))
    )
    (comp (ref "R58")
      (value "2K2")
      (footprint "eagle-import:0207_2V")
      (libsource (lib "eagle-import") (part "R-EU_0207/2V"))
    )
    (comp (ref "R59")
      (value "2K2")
      (footprint "eagle-import:0207_2V")
      (libsource (lib "eagle-import") (part "R-EU_0207/2V"))
    )
    (comp (ref "R60")
      (value "2K2")
      (footprint "eagle-import:0207_2V")
      (libsource (lib "eagle-import") (part "R-EU_0207/2V"))
    )
    (comp (ref "R61")
      (value "2K2")
      (footprint "eagle-import:0207_2V")
      (libsource (lib "eagle-import") (part "R-EU_0207/2V"))
    )
    (comp (ref "R62")
      (value "2K2")
      (footprint "eagle-import:0207_2V")
      (libsource (lib "eagle-import") (part "R-EU_0207/2V"))
    )
    (comp (ref "R63")
      (value "2K2")
      (footprint "eagle-import:0207_2V")
      (libsource (lib "eagle-import") (part "R-EU_0207/2V"))
    )
    (comp (ref "R64")
      (value "2K2")
      (footprint "eagle-import:0207_2V")
      (libsource (lib "eagle-import") (part "R-EU_0207/2V"))
    )
    (comp (ref "R65")
      (value "2K2")
      (footprint "eagle-import:0207_2V")
      (libsource (lib "eagle-import") (part "R-EU_0207/2V"))
    )
    (comp (ref "R66")
      (value "2K2")
      (footprint "eagle-import:0207_2V")
      (libsource (lib "eagle-import") (part "R-EU_0207/2V"))
    )
    (comp (ref "R67")
      (value "2K2")
      (footprint "eagle-import:0207_2V")
      (libsource (lib "eagle-import") (part "R-EU_0207/2V"))
    )
    (comp (ref "R68")
      (value "2K2")
      (footprint "eagle-import:0207_2V")
      (libsource (lib "eagle-import") (part "R-EU_0207/2V"))
    )
    (comp (ref "R69")
      (value "2K2")
      (footprint "eagle-import:0207_2V")
      (libsource (lib "eagle-import") (part "R-EU_0207/2V"))
    )
    (comp (ref "R70")
      (value "2K2")
      (footprint "eagle-import:0207_2V")
      (libsource (lib "eagle-import") (part "R-EU_0207/2V"))
    )
    (comp (ref "R71")
      (value "2K2")
      (footprint "eagle-import:0207_2V")
      (libsource (lib "eagle-import") (part "R-EU_0207/2V"))
    )
    (comp (ref "R72")
      (value "2K2")
      (footprint "eagle-import:0207_2V")
      (libsource (lib "eagle-import") (part "R-EU_0207/2V"))
    )
    (comp (ref "R73")
      (value "2K2")
      (footprint "eagle-import:0207_2V")
      (libsource (lib "eagle-import") (part "R-EU_0207/2V"))
    )
    (comp (ref "R74")
      (value "2K2")
      (footprint "eagle-import:0207_2V")
      (libsource (lib "eagle-import") (part "R-EU_0207/2V"))
    )
    (comp (ref "R75")
      (value "2K2")
      (footprint "eagle-import:0207_2V")
      (libsource (lib "eagle-import") (part "R-EU_0207/2V"))
    )
    (comp (ref "R76")
      (value "2K2")
      (footprint "eagle-import:0207_2V")
      (libsource (lib "eagle-import") (part "R-EU_0207/2V"))
    )
    (comp (ref "R77")
      (value "2K2")
      (footprint "eagle-import:0207_2V")
      (libsource (lib "eagle-import") (part "R-EU_0207/2V"))
    )
    (comp (ref "R78")
      (value "2K2")
      (footprint "eagle-import:0207_2V")
      (libsource (lib "eagle-import") (part "R-EU_0207/2V"))
    )
    (comp (ref "R79")
      (value "2K2")
      (footprint "eagle-import:0207_2V")
      (libsource (lib "eagle-import") (part "R-EU_0207/2V"))
    )
    (comp (ref "R80")
      (value "2K2")
      (footprint "eagle-import:0207_2V")
      (libsource (lib "eagle-import") (part "R-EU_0207/2V"))
    )
    (comp (ref "R81")
      (value "2K2")
      (footprint "eagle-import:0207_2V")
      (libsource (lib "eagle-import") (part "R-EU_0207/2V"))
    )
    (comp (ref "R82")
      (value "2K2")
      (footprint "eagle-import:0207_2V")
      (libsource (lib "eagle-import") (part "R-EU_0207/2V"))
    )
    (comp (ref "R83")
      (value "2K2")
      (footprint "eagle-import:0207_2V")
      (libsource (lib "eagle-import") (part "R-EU_0207/2V"))
    )
    (comp (ref "R84")
      (value "2K2")
      (footprint "eagle-import:0207_2V")
      (libsource (lib "eagle-import") (part "R-EU_0207/2V"))
    )
    (comp (ref "R85")
      (value "2K2")
      (footprint "eagle-import:0207_2V")
      (libsource (lib "eagle-import") (part "R-EU_0207/2V"))
    )
    (comp (ref "R86")
      (value "2K2")
      (footprint "eagle-import:0207_2V")
      (libsource (lib "eagle-import") (part "R-EU_0207/2V"))
    )
    (comp (ref "R87")
      (value "2K2")
      (footprint "eagle-import:0207_2V")
      (libsource (lib "eagle-import") (part "R-EU_0207/2V"))
    )
    (comp (ref "R88")
      (value "2K2")
      (footprint "eagle-import:0207_2V")
      (libsource (lib "eagle-import") (part "R-EU_0207/2V"))
    )
    (comp (ref "R89")
      (value "2K2")
      (footprint "eagle-import:0207_2V")
      (libsource (lib "eagle-import") (part "R-EU_0207/2V"))
    )
    (comp (ref "R90")
      (value "2K2")
      (footprint "eagle-import:0207_2V")
      (libsource (lib "eagle-import") (part "R-EU_0207/2V"))
    )
    (comp (ref "R91")
      (value "2K2")
      (footprint "eagle-import:0207_2V")
      (libsource (lib "eagle-import") (part "R-EU_0207/2V"))
    )
    (comp (ref "R92")
      (value "2K2")
      (footprint "eagle-import:0207_2V")
      (libsource (lib "eagle-import") (part "R-EU_0207/2V"))
    )
    (comp (ref "R93")
      (value "2K2")
      (footprint "eagle-import:0207_2V")
      (libsource (lib "eagle-import") (part "R-EU_0207/2V"))
    )
    (comp (ref "R94")
      (value "2K2")
      (footprint "eagle-import:0207_2V")
      (libsource (lib "eagle-import") (part "R-EU_0207/2V"))
    )
    (comp (ref "R95")
      (value "2K2")
      (footprint "eagle-import:0207_2V")
      (libsource (lib "eagle-import") (part "R-EU_0207/2V"))
    )
    (comp (ref "R96")
      (value "2K2")
      (footprint "eagle-import:0207_2V")
      (libsource (lib "eagle-import") (part "R-EU_0207/2V"))
    )
    (comp (ref "R97")
      (value "2K2")
      (footprint "eagle-import:0207_2V")
      (libsource (lib "eagle-import") (part "R-EU_0207/2V"))
    )
    (comp (ref "R98")
      (value "2K2")
      (footprint "eagle-import:0207_2V")
      (libsource (lib "eagle-import") (part "R-EU_0207/2V"))
    )
    (comp (ref "R99")
      (value "2K2")
      (footprint "eagle-import:0207_2V")
      (libsource (lib "eagle-import") (part "R-EU_0207/2V"))
    )
    (comp (ref "R100")
      (value "2K2")
      (footprint "eagle-import:0207_2V")
      (libsource (lib "eagle-import") (part "R-EU_0207/2V"))
    )
    (comp (ref "R101")
      (value "2K2")
      (footprint "eagle-import:0207_2V")
      (libsource (lib "eagle-import") (part "R-EU_0207/2V"))
    )
    (comp (ref "R102")
      (value "2K2")
      (footprint "eagle-import:0207_2V")
      (libsource (lib "eagle-import") (part "R-EU_0207/2V"))
    )
    (comp (ref "R103")
      (value "2K2")
      (footprint "eagle-import:0207_2V")
      (libsource (lib "eagle-import") (part "R-EU_0207/2V"))
    )
    (comp (ref "R104")
      (value "2K2")
      (footprint "eagle-import:0207_2V")
      (libsource (lib "eagle-import") (part "R-EU_0207/2V"))
    )
    (comp (ref "R105")
      (value "2K2")
      (footprint "eagle-import:0207_2V")
      (libsource (lib "eagle-import") (part "R-EU_0207/2V"))
    )
    (comp (ref "R106")
      (value "2K2")
      (footprint "eagle-import:0207_2V")
      (libsource (lib "eagle-import") (part "R-EU_0207/2V"))
    )
    (comp (ref "R107")
      (value "2K2")
      (footprint "eagle-import:0207_2V")
      (libsource (lib "eagle-import") (part "R-EU_0207/2V"))
    )
    (comp (ref "R108")
      (value "2K2")
      (footprint "eagle-import:0207_2V")
      (libsource (lib "eagle-import") (part "R-EU_0207/2V"))
    )
    (comp (ref "R109")
      (value "2K2")
      (footprint "eagle-import:0207_2V")
      (libsource (lib "eagle-import") (part "R-EU_0207/2V"))
    )
    (comp (ref "R110")
      (value "2K2")
      (footprint "eagle-import:0207_2V")
      (libsource (lib "eagle-import") (part "R-EU_0207/2V"))
    )
    (comp (ref "R111")
      (value "2K2")
      (footprint "eagle-import:0207_2V")
      (libsource (lib "eagle-import") (part "R-EU_0207/2V"))
    )
    (comp (ref "R112")
      (value "2K2")
      (footprint "eagle-import:0207_2V")
      (libsource (lib "eagle-import") (part "R-EU_0207/2V"))
    )
    (comp (ref "R113")
      (value "2K2")
      (footprint "eagle-import:0207_2V")
      (libsource (lib "eagle-import") (part "R-EU_0207/2V"))
    )
    (comp (ref "R114")
      (value "2K2")
      (footprint "eagle-import:0207_2V")
      (libsource (lib "eagle-import") (part "R-EU_0207/2V"))
    )
    (comp (ref "R115")
      (value "2K2")
      (footprint "eagle-import:0207_2V")
      (libsource (lib "eagle-import") (part "R-EU_0207/2V"))
    )
    (comp (ref "R116")
      (value "2K2")
      (footprint "eagle-import:0207_2V")
      (libsource (lib "eagle-import") (part "R-EU_0207/2V"))
    )
    (comp (ref "R117")
      (value "2K2")
      (footprint "eagle-import:0207_2V")
      (libsource (lib "eagle-import") (part "R-EU_0207/2V"))
    )
    (comp (ref "R118")
      (value "2K2")
      (footprint "eagle-import:0207_2V")
      (libsource (lib "eagle-import") (part "R-EU_0207/2V"))
    )
    (comp (ref "R119")
      (value "2K2")
      (footprint "eagle-import:0207_2V")
      (libsource (lib "eagle-import") (part "R-EU_0207/2V"))
    )
    (comp (ref "R120")
      (value "2K2")
      (footprint "eagle-import:0207_2V")
      (libsource (lib "eagle-import") (part "R-EU_0207/2V"))
    )
    (comp (ref "R121")
      (value "2K2")
      (footprint "eagle-import:0207_2V")
      (libsource (lib "eagle-import") (part "R-EU_0207/2V"))
    )
    (comp (ref "R122")
      (value "2K2")
      (footprint "eagle-import:0207_2V")
      (libsource (lib "eagle-import") (part "R-EU_0207/2V"))
    )
    (comp (ref "R123")
      (value "2K2")
      (footprint "eagle-import:0207_2V")
      (libsource (lib "eagle-import") (part "R-EU_0207/2V"))
    )
    (comp (ref "R124")
      (value "2K2")
      (footprint "eagle-import:0207_2V")
      (libsource (lib "eagle-import") (part "R-EU_0207/2V"))
    )
    (comp (ref "R125")
      (value "2K2")
      (footprint "eagle-import:0207_2V")
      (libsource (lib "eagle-import") (part "R-EU_0207/2V"))
    )
  )
  (nets
    (net (code "1") (name "DISP_BLANK") (class "Default")
      (node (ref "A_BUS") (pin "36") (pinfunction "36_36") (pintype "passive"))
    )
    (net (code "2") (name "DOM_TENS_SEG_AD") (class "Default")
      (node (ref "B_BUS") (pin "39") (pinfunction "39_39") (pintype "passive"))
      (node (ref "Q58") (pin "2") (pinfunction "G_2") (pintype "passive"))
    )
    (net (code "3") (name "DOM_TENS_SEG_B") (class "Default")
      (node (ref "B_BUS") (pin "40") (pinfunction "40_40") (pintype "passive"))
      (node (ref "Q59") (pin "2") (pinfunction "G_2") (pintype "passive"))
    )
    (net (code "4") (name "DOM_TENS_SEG_C") (class "Default")
      (node (ref "C_BUS") (pin "1") (pinfunction "1_1") (pintype "passive"))
      (node (ref "Q60") (pin "2") (pinfunction "G_2") (pintype "passive"))
    )
    (net (code "5") (name "DOM_TENS_SEG_E") (class "Default")
      (node (ref "C_BUS") (pin "2") (pinfunction "2_2") (pintype "passive"))
      (node (ref "Q61") (pin "2") (pinfunction "G_2") (pintype "passive"))
    )
    (net (code "6") (name "DOM_TENS_SEG_F") (class "Default")
      (node (ref "C_BUS") (pin "3") (pinfunction "3_3") (pintype "passive"))
      (node (ref "Q62") (pin "2") (pinfunction "G_2") (pintype "passive"))
    )
    (net (code "7") (name "DOM_TENS_SEG_G") (class "Default")
      (node (ref "C_BUS") (pin "4") (pinfunction "4_4") (pintype "passive"))
      (node (ref "Q63") (pin "2") (pinfunction "G_2") (pintype "passive"))
    )
    (net (code "8") (name "DOM_UNIT_SEG_A") (class "Default")
      (node (ref "B_BUS") (pin "32") (pinfunction "32_32") (pintype "passive"))
      (node (ref "Q64") (pin "2") (pinfunction "G_2") (pintype "passive"))
    )
    (net (code "9") (name "DOM_UNIT_SEG_B") (class "Default")
      (node (ref "B_BUS") (pin "33") (pinfunction "33_33") (pintype "passive"))
      (node (ref "Q65") (pin "2") (pinfunction "G_2") (pintype "passive"))
    )
    (net (code "10") (name "DOM_UNIT_SEG_C") (class "Default")
      (node (ref "B_BUS") (pin "34") (pinfunction "34_34") (pintype "passive"))
      (node (ref "Q66") (pin "2") (pinfunction "G_2") (pintype "passive"))
    )
    (net (code "11") (name "DOM_UNIT_SEG_D") (class "Default")
      (node (ref "B_BUS") (pin "35") (pinfunction "35_35") (pintype "passive"))
      (node (ref "Q67") (pin "2") (pinfunction "G_2") (pintype "passive"))
    )
    (net (code "12") (name "DOM_UNIT_SEG_E") (class "Default")
      (node (ref "B_BUS") (pin "36") (pinfunction "36_36") (pintype "passive"))
      (node (ref "Q68") (pin "2") (pinfunction "G_2") (pintype "passive"))
    )
    (net (code "13") (name "DOM_UNIT_SEG_F") (class "Default")
      (node (ref "B_BUS") (pin "37") (pinfunction "37_37") (pintype "passive"))
      (node (ref "Q69") (pin "2") (pinfunction "G_2") (pintype "passive"))
    )
    (net (code "14") (name "DOM_UNIT_SEG_G") (class "Default")
      (node (ref "B_BUS") (pin "38") (pinfunction "38_38") (pintype "passive"))
      (node (ref "Q70") (pin "2") (pinfunction "G_2") (pintype "passive"))
    )
    (net (code "15") (name "DOW_1_SEG_AB") (class "Default")
      (node (ref "B_BUS") (pin "14") (pinfunction "14_14") (pintype "passive"))
      (node (ref "Q40") (pin "2") (pinfunction "G_2") (pintype "passive"))
    )
    (net (code "16") (name "DOW_1_SEG_C") (class "Default")
      (node (ref "B_BUS") (pin "15") (pinfunction "15_15") (pintype "passive"))
      (node (ref "Q41") (pin "2") (pinfunction "G_2") (pintype "passive"))
    )
    (net (code "17") (name "DOW_1_SEG_D") (class "Default")
      (node (ref "B_BUS") (pin "16") (pinfunction "16_16") (pintype "passive"))
      (node (ref "Q42") (pin "2") (pinfunction "G_2") (pintype "passive"))
    )
    (net (code "18") (name "DOW_1_SEG_EF") (class "Default")
      (node (ref "B_BUS") (pin "17") (pinfunction "17_17") (pintype "passive"))
      (node (ref "Q43") (pin "2") (pinfunction "G_2") (pintype "passive"))
    )
    (net (code "19") (name "DOW_1_SEG_GH") (class "Default")
      (node (ref "B_BUS") (pin "18") (pinfunction "18_18") (pintype "passive"))
      (node (ref "Q44") (pin "2") (pinfunction "G_2") (pintype "passive"))
    )
    (net (code "20") (name "DOW_1_SEG_K") (class "Default")
      (node (ref "B_BUS") (pin "19") (pinfunction "19_19") (pintype "passive"))
      (node (ref "Q45") (pin "2") (pinfunction "G_2") (pintype "passive"))
    )
    (net (code "21") (name "DOW_1_SEG_MS") (class "Default")
      (node (ref "B_BUS") (pin "20") (pinfunction "20_20") (pintype "passive"))
      (node (ref "Q46") (pin "2") (pinfunction "G_2") (pintype "passive"))
    )
    (net (code "22") (name "DOW_1_SEG_N") (class "Default")
      (node (ref "B_BUS") (pin "21") (pinfunction "21_21") (pintype "passive"))
      (node (ref "Q47") (pin "2") (pinfunction "G_2") (pintype "passive"))
    )
    (net (code "23") (name "DOW_1_SEG_P") (class "Default")
      (node (ref "B_BUS") (pin "22") (pinfunction "22_22") (pintype "passive"))
      (node (ref "Q48") (pin "2") (pinfunction "G_2") (pintype "passive"))
    )
    (net (code "24") (name "DOW_1_SEG_RT") (class "Default")
      (node (ref "B_BUS") (pin "23") (pinfunction "23_23") (pintype "passive"))
      (node (ref "Q49") (pin "2") (pinfunction "G_2") (pintype "passive"))
    )
    (net (code "25") (name "DOW_1_SEG_U") (class "Default")
      (node (ref "B_BUS") (pin "24") (pinfunction "24_24") (pintype "passive"))
      (node (ref "Q50") (pin "2") (pinfunction "G_2") (pintype "passive"))
    )
    (net (code "26") (name "DOW_2_SEG_AB") (class "Default")
      (node (ref "B_BUS") (pin "25") (pinfunction "25_25") (pintype "passive"))
      (node (ref "Q51") (pin "2") (pinfunction "G_2") (pintype "passive"))
    )
    (net (code "27") (name "DOW_2_SEG_C") (class "Default")
      (node (ref "B_BUS") (pin "26") (pinfunction "26_26") (pintype "passive"))
      (node (ref "Q52") (pin "2") (pinfunction "G_2") (pintype "passive"))
    )
    (net (code "28") (name "DOW_2_SEG_D") (class "Default")
      (node (ref "B_BUS") (pin "27") (pinfunction "27_27") (pintype "passive"))
      (node (ref "Q53") (pin "2") (pinfunction "G_2") (pintype "passive"))
    )
    (net (code "29") (name "DOW_2_SEG_EF") (class "Default")
      (node (ref "B_BUS") (pin "28") (pinfunction "28_28") (pintype "passive"))
      (node (ref "Q54") (pin "2") (pinfunction "G_2") (pintype "passive"))
    )
    (net (code "30") (name "DOW_2_SEG_GH") (class "Default")
      (node (ref "B_BUS") (pin "29") (pinfunction "29_29") (pintype "passive"))
      (node (ref "Q55") (pin "2") (pinfunction "G_2") (pintype "passive"))
    )
    (net (code "31") (name "DOW_2_SEG_PU") (class "Default")
      (node (ref "B_BUS") (pin "30") (pinfunction "30_30") (pintype "passive"))
      (node (ref "Q56") (pin "2") (pinfunction "G_2") (pintype "passive"))
    )
    (net (code "32") (name "DOW_2_SEG_R") (class "Default")
      (node (ref "B_BUS") (pin "31") (pinfunction "31_31") (pintype "passive"))
      (node (ref "Q57") (pin "2") (pinfunction "G_2") (pintype "passive"))
    )
    (net (code "33") (name "HRS_TENS_SEG_AD") (class "Default")
      (node (ref "D_BUS") (pin "34") (pinfunction "34_34") (pintype "passive"))
      (node (ref "Q1") (pin "2") (pinfunction "G_2") (pintype "passive"))
    )
    (net (code "34") (name "HRS_TENS_SEG_B") (class "Default")
      (node (ref "D_BUS") (pin "35") (pinfunction "35_35") (pintype "passive"))
      (node (ref "Q2") (pin "2") (pinfunction "G_2") (pintype "passive"))
    )
    (net (code "35") (name "HRS_TENS_SEG_C") (class "Default")
      (node (ref "D_BUS") (pin "36") (pinfunction "36_36") (pintype "passive"))
      (node (ref "Q3") (pin "2") (pinfunction "G_2") (pintype "passive"))
    )
    (net (code "36") (name "HRS_TENS_SEG_E") (class "Default")
      (node (ref "D_BUS") (pin "37") (pinfunction "37_37") (pintype "passive"))
      (node (ref "Q4") (pin "2") (pinfunction "G_2") (pintype "passive"))
    )
    (net (code "37") (name "HRS_TENS_SEG_F") (class "Default")
      (node (ref "D_BUS") (pin "38") (pinfunction "38_38") (pintype "passive"))
      (node (ref "Q5") (pin "2") (pinfunction "G_2") (pintype "passive"))
    )
    (net (code "38") (name "HRS_TENS_SEG_G") (class "Default")
      (node (ref "D_BUS") (pin "39") (pinfunction "39_39") (pintype "passive"))
      (node (ref "Q6") (pin "2") (pinfunction "G_2") (pintype "passive"))
    )
    (net (code "39") (name "HRS_UNIT_SEG_A") (class "Default")
      (node (ref "D_BUS") (pin "27") (pinfunction "27_27") (pintype "passive"))
      (node (ref "Q7") (pin "2") (pinfunction "G_2") (pintype "passive"))
    )
    (net (code "40") (name "HRS_UNIT_SEG_B") (class "Default")
      (node (ref "D_BUS") (pin "28") (pinfunction "28_28") (pintype "passive"))
      (node (ref "Q8") (pin "2") (pinfunction "G_2") (pintype "passive"))
    )
    (net (code "41") (name "HRS_UNIT_SEG_C") (class "Default")
      (node (ref "D_BUS") (pin "29") (pinfunction "29_29") (pintype "passive"))
      (node (ref "Q9") (pin "2") (pinfunction "G_2") (pintype "passive"))
    )
    (net (code "42") (name "HRS_UNIT_SEG_D") (class "Default")
      (node (ref "D_BUS") (pin "30") (pinfunction "30_30") (pintype "passive"))
      (node (ref "Q10") (pin "2") (pinfunction "G_2") (pintype "passive"))
    )
    (net (code "43") (name "HRS_UNIT_SEG_E") (class "Default")
      (node (ref "D_BUS") (pin "31") (pinfunction "31_31") (pintype "passive"))
      (node (ref "Q11") (pin "2") (pinfunction "G_2") (pintype "passive"))
    )
    (net (code "44") (name "HRS_UNIT_SEG_F") (class "Default")
      (node (ref "D_BUS") (pin "32") (pinfunction "32_32") (pintype "passive"))
      (node (ref "Q12") (pin "2") (pinfunction "G_2") (pintype "passive"))
    )
    (net (code "45") (name "HRS_UNIT_SEG_G") (class "Default")
      (node (ref "D_BUS") (pin "33") (pinfunction "33_33") (pintype "passive"))
      (node (ref "Q13") (pin "2") (pinfunction "G_2") (pintype "passive"))
    )
    (net (code "46") (name "LEAP_YEAR") (class "Default")
      (node (ref "A_BUS") (pin "28") (pinfunction "28_28") (pintype "passive"))
      (node (ref "Q71") (pin "2") (pinfunction "G_2") (pintype "passive"))
    )
    (net (code "47") (name "MIN_TENS_SEG_AD") (class "Default")
      (node (ref "D_BUS") (pin "21") (pinfunction "21_21") (pintype "passive"))
      (node (ref "Q14") (pin "2") (pinfunction "G_2") (pintype "passive"))
    )
    (net (code "48") (name "MIN_TENS_SEG_B") (class "Default")
      (node (ref "D_BUS") (pin "22") (pinfunction "22_22") (pintype "passive"))
      (node (ref "Q15") (pin "2") (pinfunction "G_2") (pintype "passive"))
    )
    (net (code "49") (name "MIN_TENS_SEG_C") (class "Default")
      (node (ref "D_BUS") (pin "23") (pinfunction "23_23") (pintype "passive"))
      (node (ref "Q16") (pin "2") (pinfunction "G_2") (pintype "passive"))
    )
    (net (code "50") (name "MIN_TENS_SEG_E") (class "Default")
      (node (ref "D_BUS") (pin "24") (pinfunction "24_24") (pintype "passive"))
      (node (ref "Q17") (pin "2") (pinfunction "G_2") (pintype "passive"))
    )
    (net (code "51") (name "MIN_TENS_SEG_F") (class "Default")
      (node (ref "D_BUS") (pin "25") (pinfunction "25_25") (pintype "passive"))
      (node (ref "Q18") (pin "2") (pinfunction "G_2") (pintype "passive"))
    )
    (net (code "52") (name "MIN_TENS_SEG_G") (class "Default")
      (node (ref "D_BUS") (pin "26") (pinfunction "26_26") (pintype "passive"))
      (node (ref "Q19") (pin "2") (pinfunction "G_2") (pintype "passive"))
    )
    (net (code "53") (name "MIN_UNIT_SEG_A") (class "Default")
      (node (ref "D_BUS") (pin "14") (pinfunction "14_14") (pintype "passive"))
      (node (ref "Q20") (pin "2") (pinfunction "G_2") (pintype "passive"))
    )
    (net (code "54") (name "MIN_UNIT_SEG_B") (class "Default")
      (node (ref "D_BUS") (pin "15") (pinfunction "15_15") (pintype "passive"))
      (node (ref "Q21") (pin "2") (pinfunction "G_2") (pintype "passive"))
    )
    (net (code "55") (name "MIN_UNIT_SEG_C") (class "Default")
      (node (ref "D_BUS") (pin "16") (pinfunction "16_16") (pintype "passive"))
      (node (ref "Q22") (pin "2") (pinfunction "G_2") (pintype "passive"))
    )
    (net (code "56") (name "MIN_UNIT_SEG_D") (class "Default")
      (node (ref "D_BUS") (pin "17") (pinfunction "17_17") (pintype "passive"))
      (node (ref "Q23") (pin "2") (pinfunction "G_2") (pintype "passive"))
    )
    (net (code "57") (name "MIN_UNIT_SEG_E") (class "Default")
      (node (ref "D_BUS") (pin "18") (pinfunction "18_18") (pintype "passive"))
      (node (ref "Q24") (pin "2") (pinfunction "G_2") (pintype "passive"))
    )
    (net (code "58") (name "MIN_UNIT_SEG_F") (class "Default")
      (node (ref "D_BUS") (pin "19") (pinfunction "19_19") (pintype "passive"))
      (node (ref "Q25") (pin "2") (pinfunction "G_2") (pintype "passive"))
    )
    (net (code "59") (name "MIN_UNIT_SEG_G") (class "Default")
      (node (ref "D_BUS") (pin "20") (pinfunction "20_20") (pintype "passive"))
      (node (ref "Q26") (pin "2") (pinfunction "G_2") (pintype "passive"))
    )
    (net (code "60") (name "MON_1_SEG_AB") (class "Default")
      (node (ref "C_BUS") (pin "5") (pinfunction "5_5") (pintype "passive"))
      (node (ref "Q72") (pin "2") (pinfunction "G_2") (pintype "passive"))
    )
    (net (code "61") (name "MON_1_SEG_C") (class "Default")
      (node (ref "C_BUS") (pin "6") (pinfunction "6_6") (pintype "passive"))
      (node (ref "Q73") (pin "2") (pinfunction "G_2") (pintype "passive"))
    )
    (net (code "62") (name "MON_1_SEG_D") (class "Default")
      (node (ref "C_BUS") (pin "7") (pinfunction "7_7") (pintype "passive"))
      (node (ref "Q74") (pin "2") (pinfunction "G_2") (pintype "passive"))
    )
    (net (code "63") (name "MON_1_SEG_EF") (class "Default")
      (node (ref "C_BUS") (pin "8") (pinfunction "8_8") (pintype "passive"))
      (node (ref "Q75") (pin "2") (pinfunction "G_2") (pintype "passive"))
    )
    (net (code "64") (name "MON_1_SEG_G") (class "Default")
      (node (ref "C_BUS") (pin "9") (pinfunction "9_9") (pintype "passive"))
      (node (ref "Q76") (pin "2") (pinfunction "G_2") (pintype "passive"))
    )
    (net (code "65") (name "MON_1_SEG_H") (class "Default")
      (node (ref "C_BUS") (pin "10") (pinfunction "10_10") (pintype "passive"))
      (node (ref "Q77") (pin "2") (pinfunction "G_2") (pintype "passive"))
    )
    (net (code "66") (name "MON_1_SEG_K") (class "Default")
      (node (ref "C_BUS") (pin "11") (pinfunction "11_11") (pintype "passive"))
      (node (ref "Q78") (pin "2") (pinfunction "G_2") (pintype "passive"))
    )
    (net (code "67") (name "MON_1_SEG_MS") (class "Default")
      (node (ref "C_BUS") (pin "12") (pinfunction "12_12") (pintype "passive"))
      (node (ref "Q79") (pin "2") (pinfunction "G_2") (pintype "passive"))
    )
    (net (code "68") (name "MON_1_SEG_N") (class "Default")
      (node (ref "C_BUS") (pin "13") (pinfunction "13_13") (pintype "passive"))
      (node (ref "Q80") (pin "2") (pinfunction "G_2") (pintype "passive"))
    )
    (net (code "69") (name "MON_1_SEG_P") (class "Default")
      (node (ref "C_BUS") (pin "14") (pinfunction "14_14") (pintype "passive"))
      (node (ref "Q81") (pin "2") (pinfunction "G_2") (pintype "passive"))
    )
    (net (code "70") (name "MON_1_SEG_R") (class "Default")
      (node (ref "C_BUS") (pin "15") (pinfunction "15_15") (pintype "passive"))
      (node (ref "Q82") (pin "2") (pinfunction "G_2") (pintype "passive"))
    )
    (net (code "71") (name "MON_1_SEG_U") (class "Default")
      (node (ref "C_BUS") (pin "16") (pinfunction "16_16") (pintype "passive"))
      (node (ref "Q83") (pin "2") (pinfunction "G_2") (pintype "passive"))
    )
    (net (code "72") (name "MON_2_SEG_AB") (class "Default")
      (node (ref "C_BUS") (pin "17") (pinfunction "17_17") (pintype "passive"))
      (node (ref "Q84") (pin "2") (pinfunction "G_2") (pintype "passive"))
    )
    (net (code "73") (name "MON_2_SEG_C") (class "Default")
      (node (ref "C_BUS") (pin "18") (pinfunction "18_18") (pintype "passive"))
      (node (ref "Q85") (pin "2") (pinfunction "G_2") (pintype "passive"))
    )
    (net (code "74") (name "MON_2_SEG_D") (class "Default")
      (node (ref "C_BUS") (pin "19") (pinfunction "19_19") (pintype "passive"))
      (node (ref "Q86") (pin "2") (pinfunction "G_2") (pintype "passive"))
    )
    (net (code "75") (name "MON_2_SEG_EF") (class "Default")
      (node (ref "C_BUS") (pin "20") (pinfunction "20_20") (pintype "passive"))
      (node (ref "Q87") (pin "2") (pinfunction "G_2") (pintype "passive"))
    )
    (net (code "76") (name "MON_2_SEG_GH") (class "Default")
      (node (ref "C_BUS") (pin "21") (pinfunction "21_21") (pintype "passive"))
      (node (ref "Q88") (pin "2") (pinfunction "G_2") (pintype "passive"))
    )
    (net (code "77") (name "MON_2_SEG_PU") (class "Default")
      (node (ref "C_BUS") (pin "22") (pinfunction "22_22") (pintype "passive"))
      (node (ref "Q89") (pin "2") (pinfunction "G_2") (pintype "passive"))
    )
    (net (code "78") (name "MON_3_SEG_AB") (class "Default")
      (node (ref "C_BUS") (pin "23") (pinfunction "23_23") (pintype "passive"))
      (node (ref "Q90") (pin "2") (pinfunction "G_2") (pintype "passive"))
    )
    (net (code "79") (name "MON_3_SEG_C") (class "Default")
      (node (ref "C_BUS") (pin "24") (pinfunction "24_24") (pintype "passive"))
      (node (ref "Q91") (pin "2") (pinfunction "G_2") (pintype "passive"))
    )
    (net (code "80") (name "MON_3_SEG_D") (class "Default")
      (node (ref "C_BUS") (pin "25") (pinfunction "25_25") (pintype "passive"))
      (node (ref "Q92") (pin "2") (pinfunction "G_2") (pintype "passive"))
    )
    (net (code "81") (name "MON_3_SEG_EF") (class "Default")
      (node (ref "C_BUS") (pin "26") (pinfunction "26_26") (pintype "passive"))
      (node (ref "Q93") (pin "2") (pinfunction "G_2") (pintype "passive"))
    )
    (net (code "82") (name "MON_3_SEG_GH") (class "Default")
      (node (ref "C_BUS") (pin "27") (pinfunction "27_27") (pintype "passive"))
      (node (ref "Q94") (pin "2") (pinfunction "G_2") (pintype "passive"))
    )
    (net (code "83") (name "MON_3_SEG_K") (class "Default")
      (node (ref "C_BUS") (pin "28") (pinfunction "28_28") (pintype "passive"))
      (node (ref "Q95") (pin "2") (pinfunction "G_2") (pintype "passive"))
    )
    (net (code "84") (name "MON_3_SEG_M") (class "Default")
      (node (ref "C_BUS") (pin "29") (pinfunction "29_29") (pintype "passive"))
      (node (ref "Q96") (pin "2") (pinfunction "G_2") (pintype "passive"))
    )
    (net (code "85") (name "MON_3_SEG_N") (class "Default")
      (node (ref "C_BUS") (pin "30") (pinfunction "30_30") (pintype "passive"))
      (node (ref "Q97") (pin "2") (pinfunction "G_2") (pintype "passive"))
    )
    (net (code "86") (name "MON_3_SEG_P") (class "Default")
      (node (ref "C_BUS") (pin "31") (pinfunction "31_31") (pintype "passive"))
      (node (ref "Q98") (pin "2") (pinfunction "G_2") (pintype "passive"))
    )
    (net (code "87") (name "MON_3_SEG_R") (class "Default")
      (node (ref "C_BUS") (pin "32") (pinfunction "32_32") (pintype "passive"))
      (node (ref "Q99") (pin "2") (pinfunction "G_2") (pintype "passive"))
    )
    (net (code "88") (name "MON_3_SEG_S") (class "Default")
      (node (ref "C_BUS") (pin "33") (pinfunction "33_33") (pintype "passive"))
      (node (ref "Q100") (pin "2") (pinfunction "G_2") (pintype "passive"))
    )
    (net (code "89") (name "MON_3_SEG_T") (class "Default")
      (node (ref "C_BUS") (pin "34") (pinfunction "34_34") (pintype "passive"))
      (node (ref "Q101") (pin "2") (pinfunction "G_2") (pintype "passive"))
    )
    (net (code "90") (name "MON_3_SEG_U") (class "Default")
      (node (ref "C_BUS") (pin "35") (pinfunction "35_35") (pintype "passive"))
      (node (ref "Q102") (pin "2") (pinfunction "G_2") (pintype "passive"))
    )
    (net (code "91") (name "Net-(LED1-A)") (class "Default")
      (node (ref "LED1") (pin "P$2") (pinfunction "A_P$2") (pintype "bidirectional"))
      (node (ref "R1") (pin "2") (pinfunction "2_2") (pintype "passive"))
    )
    (net (code "92") (name "Net-(LED1-B)") (class "Default")
      (node (ref "LED1") (pin "P$15") (pinfunction "B_P$15") (pintype "bidirectional"))
      (node (ref "R3") (pin "2") (pinfunction "2_2") (pintype "passive"))
    )
    (net (code "93") (name "Net-(LED1-C)") (class "Default")
      (node (ref "LED1") (pin "P$13") (pinfunction "C_P$13") (pintype "bidirectional"))
      (node (ref "R4") (pin "2") (pinfunction "2_2") (pintype "passive"))
    )
    (net (code "94") (name "Net-(LED1-D-PadP$11)") (class "Default")
      (node (ref "LED1") (pin "P$11") (pinfunction "D_P$11") (pintype "bidirectional"))
      (node (ref "LED1") (pin "P$9") (pinfunction "D_P$9") (pintype "bidirectional"))
      (node (ref "R2") (pin "2") (pinfunction "2_2") (pintype "passive"))
    )
    (net (code "95") (name "Net-(LED1-E-PadP$5)") (class "Default")
      (node (ref "LED1") (pin "P$5") (pinfunction "E_P$5") (pintype "bidirectional"))
      (node (ref "LED1") (pin "P$7") (pinfunction "E_P$7") (pintype "bidirectional"))
      (node (ref "R5") (pin "2") (pinfunction "2_2") (pintype "passive"))
    )
    (net (code "96") (name "Net-(LED1-F)") (class "Default")
      (node (ref "LED1") (pin "P$3") (pinfunction "F_P$3") (pintype "bidirectional"))
      (node (ref "R6") (pin "2") (pinfunction "2_2") (pintype "passive"))
    )
    (net (code "97") (name "Net-(LED1-G)") (class "Default")
      (node (ref "LED1") (pin "P$14") (pinfunction "G_P$14") (pintype "bidirectional"))
      (node (ref "R7") (pin "2") (pinfunction "2_2") (pintype "passive"))
    )
    (net (code "98") (name "Net-(LED2-A)") (class "Default")
      (node (ref "LED2") (pin "P$2") (pinfunction "A_P$2") (pintype "bidirectional"))
      (node (ref "R8") (pin "2") (pinfunction "2_2") (pintype "passive"))
    )
    (net (code "99") (name "Net-(LED2-B)") (class "Default")
      (node (ref "LED2") (pin "P$15") (pinfunction "B_P$15") (pintype "bidirectional"))
      (node (ref "R9") (pin "2") (pinfunction "2_2") (pintype "passive"))
    )
    (net (code "100") (name "Net-(LED2-C)") (class "Default")
      (node (ref "LED2") (pin "P$13") (pinfunction "C_P$13") (pintype "bidirectional"))
      (node (ref "R10") (pin "2") (pinfunction "2_2") (pintype "passive"))
    )
    (net (code "101") (name "Net-(LED2-D-PadP$11)") (class "Default")
      (node (ref "LED2") (pin "P$11") (pinfunction "D_P$11") (pintype "bidirectional"))
      (node (ref "LED2") (pin "P$9") (pinfunction "D_P$9") (pintype "bidirectional"))
      (node (ref "R11") (pin "2") (pinfunction "2_2") (pintype "passive"))
    )
    (net (code "102") (name "Net-(LED2-E-PadP$5)") (class "Default")
      (node (ref "LED2") (pin "P$5") (pinfunction "E_P$5") (pintype "bidirectional"))
      (node (ref "LED2") (pin "P$7") (pinfunction "E_P$7") (pintype "bidirectional"))
      (node (ref "R12") (pin "2") (pinfunction "2_2") (pintype "passive"))
    )
    (net (code "103") (name "Net-(LED2-F)") (class "Default")
      (node (ref "LED2") (pin "P$3") (pinfunction "F_P$3") (pintype "bidirectional"))
      (node (ref "R13") (pin "2") (pinfunction "2_2") (pintype "passive"))
    )
    (net (code "104") (name "Net-(LED2-G)") (class "Default")
      (node (ref "LED2") (pin "P$14") (pinfunction "G_P$14") (pintype "bidirectional"))
      (node (ref "R14") (pin "2") (pinfunction "2_2") (pintype "passive"))
    )
    (net (code "105") (name "Net-(LED3-A)") (class "Default")
      (node (ref "LED3") (pin "P$2") (pinfunction "A_P$2") (pintype "bidirectional"))
      (node (ref "R15") (pin "2") (pinfunction "2_2") (pintype "passive"))
    )
    (net (code "106") (name "Net-(LED3-B)") (class "Default")
      (node (ref "LED3") (pin "P$15") (pinfunction "B_P$15") (pintype "bidirectional"))
      (node (ref "R17") (pin "2") (pinfunction "2_2") (pintype "passive"))
    )
    (net (code "107") (name "Net-(LED3-C)") (class "Default")
      (node (ref "LED3") (pin "P$13") (pinfunction "C_P$13") (pintype "bidirectional"))
      (node (ref "R18") (pin "2") (pinfunction "2_2") (pintype "passive"))
    )
    (net (code "108") (name "Net-(LED3-D-PadP$11)") (class "Default")
      (node (ref "LED3") (pin "P$11") (pinfunction "D_P$11") (pintype "bidirectional"))
      (node (ref "LED3") (pin "P$9") (pinfunction "D_P$9") (pintype "bidirectional"))
      (node (ref "R16") (pin "2") (pinfunction "2_2") (pintype "passive"))
    )
    (net (code "109") (name "Net-(LED3-E-PadP$5)") (class "Default")
      (node (ref "LED3") (pin "P$5") (pinfunction "E_P$5") (pintype "bidirectional"))
      (node (ref "LED3") (pin "P$7") (pinfunction "E_P$7") (pintype "bidirectional"))
      (node (ref "R19") (pin "2") (pinfunction "2_2") (pintype "passive"))
    )
    (net (code "110") (name "Net-(LED3-F)") (class "Default")
      (node (ref "LED3") (pin "P$3") (pinfunction "F_P$3") (pintype "bidirectional"))
      (node (ref "R20") (pin "2") (pinfunction "2_2") (pintype "passive"))
    )
    (net (code "111") (name "Net-(LED3-G)") (class "Default")
      (node (ref "LED3") (pin "P$14") (pinfunction "G_P$14") (pintype "bidirectional"))
      (node (ref "R21") (pin "2") (pinfunction "2_2") (pintype "passive"))
    )
    (net (code "112") (name "Net-(LED4-A)") (class "Default")
      (node (ref "LED4") (pin "P$2") (pinfunction "A_P$2") (pintype "bidirectional"))
      (node (ref "R22") (pin "2") (pinfunction "2_2") (pintype "passive"))
    )
    (net (code "113") (name "Net-(LED4-B)") (class "Default")
      (node (ref "LED4") (pin "P$15") (pinfunction "B_P$15") (pintype "bidirectional"))
      (node (ref "R23") (pin "2") (pinfunction "2_2") (pintype "passive"))
    )
    (net (code "114") (name "Net-(LED4-C)") (class "Default")
      (node (ref "LED4") (pin "P$13") (pinfunction "C_P$13") (pintype "bidirectional"))
      (node (ref "R24") (pin "2") (pinfunction "2_2") (pintype "passive"))
    )
    (net (code "115") (name "Net-(LED4-D-PadP$11)") (class "Default")
      (node (ref "LED4") (pin "P$11") (pinfunction "D_P$11") (pintype "bidirectional"))
      (node (ref "LED4") (pin "P$9") (pinfunction "D_P$9") (pintype "bidirectional"))
      (node (ref "R25") (pin "2") (pinfunction "2_2") (pintype "passive"))
    )
    (net (code "116") (name "Net-(LED4-E-PadP$5)") (class "Default")
      (node (ref "LED4") (pin "P$5") (pinfunction "E_P$5") (pintype "bidirectional"))
      (node (ref "LED4") (pin "P$7") (pinfunction "E_P$7") (pintype "bidirectional"))
      (node (ref "R26") (pin "2") (pinfunction "2_2") (pintype "passive"))
    )
    (net (code "117") (name "Net-(LED4-F)") (class "Default")
      (node (ref "LED4") (pin "P$3") (pinfunction "F_P$3") (pintype "bidirectional"))
      (node (ref "R27") (pin "2") (pinfunction "2_2") (pintype "passive"))
    )
    (net (code "118") (name "Net-(LED4-G)") (class "Default")
      (node (ref "LED4") (pin "P$14") (pinfunction "G_P$14") (pintype "bidirectional"))
      (node (ref "R28") (pin "2") (pinfunction "2_2") (pintype "passive"))
    )
    (net (code "119") (name "Net-(LED5-A)") (class "Default")
      (node (ref "LED5") (pin "P$2") (pinfunction "A_P$2") (pintype "bidirectional"))
      (node (ref "R29") (pin "2") (pinfunction "2_2") (pintype "passive"))
    )
    (net (code "120") (name "Net-(LED5-B)") (class "Default")
      (node (ref "LED5") (pin "P$15") (pinfunction "B_P$15") (pintype "bidirectional"))
      (node (ref "R31") (pin "2") (pinfunction "2_2") (pintype "passive"))
    )
    (net (code "121") (name "Net-(LED5-C)") (class "Default")
      (node (ref "LED5") (pin "P$13") (pinfunction "C_P$13") (pintype "bidirectional"))
      (node (ref "R32") (pin "2") (pinfunction "2_2") (pintype "passive"))
    )
    (net (code "122") (name "Net-(LED5-D-PadP$11)") (class "Default")
      (node (ref "LED5") (pin "P$11") (pinfunction "D_P$11") (pintype "bidirectional"))
      (node (ref "LED5") (pin "P$9") (pinfunction "D_P$9") (pintype "bidirectional"))
      (node (ref "R30") (pin "2") (pinfunction "2_2") (pintype "passive"))
    )
    (net (code "123") (name "Net-(LED5-E-PadP$5)") (class "Default")
      (node (ref "LED5") (pin "P$5") (pinfunction "E_P$5") (pintype "bidirectional"))
      (node (ref "LED5") (pin "P$7") (pinfunction "E_P$7") (pintype "bidirectional"))
      (node (ref "R33") (pin "2") (pinfunction "2_2") (pintype "passive"))
    )
    (net (code "124") (name "Net-(LED5-F)") (class "Default")
      (node (ref "LED5") (pin "P$3") (pinfunction "F_P$3") (pintype "bidirectional"))
      (node (ref "R34") (pin "2") (pinfunction "2_2") (pintype "passive"))
    )
    (net (code "125") (name "Net-(LED5-G)") (class "Default")
      (node (ref "LED5") (pin "P$14") (pinfunction "G_P$14") (pintype "bidirectional"))
      (node (ref "R35") (pin "2") (pinfunction "2_2") (pintype "passive"))
    )
    (net (code "126") (name "Net-(LED6-A)") (class "Default")
      (node (ref "LED6") (pin "P$2") (pinfunction "A_P$2") (pintype "bidirectional"))
      (node (ref "R36") (pin "2") (pinfunction "2_2") (pintype "passive"))
    )
    (net (code "127") (name "Net-(LED6-B)") (class "Default")
      (node (ref "LED6") (pin "P$15") (pinfunction "B_P$15") (pintype "bidirectional"))
      (node (ref "R37") (pin "2") (pinfunction "2_2") (pintype "passive"))
    )
    (net (code "128") (name "Net-(LED6-C)") (class "Default")
      (node (ref "LED6") (pin "P$13") (pinfunction "C_P$13") (pintype "bidirectional"))
      (node (ref "R38") (pin "2") (pinfunction "2_2") (pintype "passive"))
    )
    (net (code "129") (name "Net-(LED6-D-PadP$11)") (class "Default")
      (node (ref "LED6") (pin "P$11") (pinfunction "D_P$11") (pintype "bidirectional"))
      (node (ref "LED6") (pin "P$9") (pinfunction "D_P$9") (pintype "bidirectional"))
      (node (ref "R39") (pin "2") (pinfunction "2_2") (pintype "passive"))
    )
    (net (code "130") (name "Net-(LED6-E-PadP$5)") (class "Default")
      (node (ref "LED6") (pin "P$5") (pinfunction "E_P$5") (pintype "bidirectional"))
      (node (ref "LED6") (pin "P$7") (pinfunction "E_P$7") (pintype "bidirectional"))
      (node (ref "R40") (pin "2") (pinfunction "2_2") (pintype "passive"))
    )
    (net (code "131") (name "Net-(LED6-F)") (class "Default")
      (node (ref "LED6") (pin "P$3") (pinfunction "F_P$3") (pintype "bidirectional"))
      (node (ref "R41") (pin "2") (pinfunction "2_2") (pintype "passive"))
    )
    (net (code "132") (name "Net-(LED6-G)") (class "Default")
      (node (ref "LED6") (pin "P$14") (pinfunction "G_P$14") (pintype "bidirectional"))
      (node (ref "R42") (pin "2") (pinfunction "2_2") (pintype "passive"))
    )
    (net (code "133") (name "Net-(LED7-A)") (class "Default")
      (node (ref "LED7") (pin "P$2") (pinfunction "A_P$2") (pintype "bidirectional"))
      (node (ref "R44") (pin "2") (pinfunction "2_2") (pintype "passive"))
    )
    (net (code "134") (name "Net-(LED7-B)") (class "Default")
      (node (ref "LED7") (pin "P$1") (pinfunction "B_P$1") (pintype "bidirectional"))
      (node (ref "R43") (pin "2") (pinfunction "2_2") (pintype "passive"))
    )
    (net (code "135") (name "Net-(LED7-C)") (class "Default")
      (node (ref "LED7") (pin "P$15") (pinfunction "C_P$15") (pintype "bidirectional"))
      (node (ref "R45") (pin "2") (pinfunction "2_2") (pintype "passive"))
    )
    (net (code "136") (name "Net-(LED7-D)") (class "Default")
      (node (ref "LED7") (pin "P$13") (pinfunction "D_P$13") (pintype "bidirectional"))
      (node (ref "R46") (pin "2") (pinfunction "2_2") (pintype "passive"))
    )
    (net (code "137") (name "Net-(LED7-E)") (class "Default")
      (node (ref "LED7") (pin "P$10") (pinfunction "E_P$10") (pintype "bidirectional"))
      (node (ref "R47") (pin "2") (pinfunction "2_2") (pintype "passive"))
    )
    (net (code "138") (name "Net-(LED7-F)") (class "Default")
      (node (ref "LED7") (pin "P$11") (pinfunction "F_P$11") (pintype "bidirectional"))
      (node (ref "R48") (pin "2") (pinfunction "2_2") (pintype "passive"))
    )
    (net (code "139") (name "Net-(LED7-G)") (class "Default")
      (node (ref "LED7") (pin "P$5") (pinfunction "G_P$5") (pintype "bidirectional"))
      (node (ref "R50") (pin "2") (pinfunction "2_2") (pintype "passive"))
    )
    (net (code "140") (name "Net-(LED7-H)") (class "Default")
      (node (ref "LED7") (pin "P$3") (pinfunction "H_P$3") (pintype "bidirectional"))
      (node (ref "R49") (pin "2") (pinfunction "2_2") (pintype "passive"))
    )
    (net (code "141") (name "Net-(LED7-K)") (class "Default")
      (node (ref "LED7") (pin "P$4") (pinfunction "K_P$4") (pintype "bidirectional"))
      (node (ref "R51") (pin "2") (pinfunction "2_2") (pintype "passive"))
    )
    (net (code "142") (name "Net-(LED7-M)") (class "Default")
      (node (ref "LED7") (pin "P$6") (pinfunction "M_P$6") (pintype "bidirectional"))
      (node (ref "R52") (pin "2") (pinfunction "2_2") (pintype "passive"))
    )
    (net (code "143") (name "Net-(LED7-N)") (class "Default")
      (node (ref "LED7") (pin "P$18") (pinfunction "N_P$18") (pintype "bidirectional"))
      (node (ref "R54") (pin "2") (pinfunction "2_2") (pintype "passive"))
    )
    (net (code "144") (name "Net-(LED7-P)") (class "Default")
      (node (ref "LED7") (pin "P$16") (pinfunction "P_P$16") (pintype "bidirectional"))
      (node (ref "R55") (pin "2") (pinfunction "2_2") (pintype "passive"))
    )
    (net (code "145") (name "Net-(LED7-R)") (class "Default")
      (node (ref "LED7") (pin "P$9") (pinfunction "R_P$9") (pintype "bidirectional"))
      (node (ref "R57") (pin "2") (pinfunction "2_2") (pintype "passive"))
    )
    (net (code "146") (name "Net-(LED7-S)") (class "Default")
      (node (ref "LED7") (pin "P$7") (pinfunction "S_P$7") (pintype "bidirectional"))
      (node (ref "R53") (pin "2") (pinfunction "2_2") (pintype "passive"))
    )
    (net (code "147") (name "Net-(LED7-T)") (class "Default")
      (node (ref "LED7") (pin "P$8") (pinfunction "T_P$8") (pintype "bidirectional"))
      (node (ref "R56") (pin "2") (pinfunction "2_2") (pintype "passive"))
    )
    (net (code "148") (name "Net-(LED7-U)") (class "Default")
      (node (ref "LED7") (pin "P$14") (pinfunction "U_P$14") (pintype "bidirectional"))
      (node (ref "R58") (pin "2") (pinfunction "2_2") (pintype "passive"))
    )
    (net (code "149") (name "Net-(LED8-A)") (class "Default")
      (node (ref "LED8") (pin "P$2") (pinfunction "A_P$2") (pintype "bidirectional"))
      (node (ref "R60") (pin "2") (pinfunction "2_2") (pintype "passive"))
    )
    (net (code "150") (name "Net-(LED8-B)") (class "Default")
      (node (ref "LED8") (pin "P$1") (pinfunction "B_P$1") (pintype "bidirectional"))
      (node (ref "R59") (pin "2") (pinfunction "2_2") (pintype "passive"))
    )
    (net (code "151") (name "Net-(LED8-C)") (class "Default")
      (node (ref "LED8") (pin "P$15") (pinfunction "C_P$15") (pintype "bidirectional"))
      (node (ref "R61") (pin "2") (pinfunction "2_2") (pintype "passive"))
    )
    (net (code "152") (name "Net-(LED8-D)") (class "Default")
      (node (ref "LED8") (pin "P$13") (pinfunction "D_P$13") (pintype "bidirectional"))
      (node (ref "R62") (pin "2") (pinfunction "2_2") (pintype "passive"))
    )
    (net (code "153") (name "Net-(LED8-E)") (class "Default")
      (node (ref "LED8") (pin "P$10") (pinfunction "E_P$10") (pintype "bidirectional"))
      (node (ref "R63") (pin "2") (pinfunction "2_2") (pintype "passive"))
    )
    (net (code "154") (name "Net-(LED8-F)") (class "Default")
      (node (ref "LED8") (pin "P$11") (pinfunction "F_P$11") (pintype "bidirectional"))
      (node (ref "R64") (pin "2") (pinfunction "2_2") (pintype "passive"))
    )
    (net (code "155") (name "Net-(LED8-G)") (class "Default")
      (node (ref "LED8") (pin "P$5") (pinfunction "G_P$5") (pintype "bidirectional"))
      (node (ref "R66") (pin "2") (pinfunction "2_2") (pintype "passive"))
    )
    (net (code "156") (name "Net-(LED8-H)") (class "Default")
      (node (ref "LED8") (pin "P$3") (pinfunction "H_P$3") (pintype "bidirectional"))
      (node (ref "R65") (pin "2") (pinfunction "2_2") (pintype "passive"))
    )
    (net (code "157") (name "Net-(LED8-P)") (class "Default")
      (node (ref "LED8") (pin "P$16") (pinfunction "P_P$16") (pintype "bidirectional"))
      (node (ref "R68") (pin "2") (pinfunction "2_2") (pintype "passive"))
    )
    (net (code "158") (name "Net-(LED8-R)") (class "Default")
      (node (ref "LED8") (pin "P$9") (pinfunction "R_P$9") (pintype "bidirectional"))
      (node (ref "R69") (pin "2") (pinfunction "2_2") (pintype "passive"))
    )
    (net (code "159") (name "Net-(LED8-U)") (class "Default")
      (node (ref "LED8") (pin "P$14") (pinfunction "U_P$14") (pintype "bidirectional"))
      (node (ref "R67") (pin "2") (pinfunction "2_2") (pintype "passive"))
    )
    (net (code "160") (name "Net-(LED9-A)") (class "Default")
      (node (ref "LED9") (pin "P$2") (pinfunction "A_P$2") (pintype "bidirectional"))
      (node (ref "R70") (pin "2") (pinfunction "2_2") (pintype "passive"))
    )
    (net (code "161") (name "Net-(LED9-B)") (class "Default")
      (node (ref "LED9") (pin "P$15") (pinfunction "B_P$15") (pintype "bidirectional"))
      (node (ref "R72") (pin "2") (pinfunction "2_2") (pintype "passive"))
    )
    (net (code "162") (name "Net-(LED9-C)") (class "Default")
      (node (ref "LED9") (pin "P$13") (pinfunction "C_P$13") (pintype "bidirectional"))
      (node (ref "R73") (pin "2") (pinfunction "2_2") (pintype "passive"))
    )
    (net (code "163") (name "Net-(LED9-D-PadP$11)") (class "Default")
      (node (ref "LED9") (pin "P$11") (pinfunction "D_P$11") (pintype "bidirectional"))
      (node (ref "LED9") (pin "P$9") (pinfunction "D_P$9") (pintype "bidirectional"))
      (node (ref "R71") (pin "2") (pinfunction "2_2") (pintype "passive"))
    )
    (net (code "164") (name "Net-(LED9-E-PadP$5)") (class "Default")
      (node (ref "LED9") (pin "P$5") (pinfunction "E_P$5") (pintype "bidirectional"))
      (node (ref "LED9") (pin "P$7") (pinfunction "E_P$7") (pintype "bidirectional"))
      (node (ref "R74") (pin "2") (pinfunction "2_2") (pintype "passive"))
    )
    (net (code "165") (name "Net-(LED9-F)") (class "Default")
      (node (ref "LED9") (pin "P$3") (pinfunction "F_P$3") (pintype "bidirectional"))
      (node (ref "R75") (pin "2") (pinfunction "2_2") (pintype "passive"))
    )
    (net (code "166") (name "Net-(LED9-G)") (class "Default")
      (node (ref "LED9") (pin "P$14") (pinfunction "G_P$14") (pintype "bidirectional"))
      (node (ref "R76") (pin "2") (pinfunction "2_2") (pintype "passive"))
    )
    (net (code "167") (name "Net-(LED10-A)") (class "Default")
      (node (ref "LED10") (pin "P$2") (pinfunction "A_P$2") (pintype "bidirectional"))
      (node (ref "R77") (pin "2") (pinfunction "2_2") (pintype "passive"))
    )
    (net (code "168") (name "Net-(LED10-B)") (class "Default")
      (node (ref "LED10") (pin "P$15") (pinfunction "B_P$15") (pintype "bidirectional"))
      (node (ref "R78") (pin "2") (pinfunction "2_2") (pintype "passive"))
    )
    (net (code "169") (name "Net-(LED10-C)") (class "Default")
      (node (ref "LED10") (pin "P$13") (pinfunction "C_P$13") (pintype "bidirectional"))
      (node (ref "R79") (pin "2") (pinfunction "2_2") (pintype "passive"))
    )
    (net (code "170") (name "Net-(LED10-D-PadP$11)") (class "Default")
      (node (ref "LED10") (pin "P$11") (pinfunction "D_P$11") (pintype "bidirectional"))
      (node (ref "LED10") (pin "P$9") (pinfunction "D_P$9") (pintype "bidirectional"))
      (node (ref "R80") (pin "2") (pinfunction "2_2") (pintype "passive"))
    )
    (net (code "171") (name "Net-(LED10-DP)") (class "Default")
      (node (ref "LED10") (pin "P$10") (pinfunction "DP_P$10") (pintype "bidirectional"))
      (node (ref "R84") (pin "2") (pinfunction "2_2") (pintype "passive"))
    )
    (net (code "172") (name "Net-(LED10-E-PadP$5)") (class "Default")
      (node (ref "LED10") (pin "P$5") (pinfunction "E_P$5") (pintype "bidirectional"))
      (node (ref "LED10") (pin "P$7") (pinfunction "E_P$7") (pintype "bidirectional"))
      (node (ref "R81") (pin "2") (pinfunction "2_2") (pintype "passive"))
    )
    (net (code "173") (name "Net-(LED10-F)") (class "Default")
      (node (ref "LED10") (pin "P$3") (pinfunction "F_P$3") (pintype "bidirectional"))
      (node (ref "R82") (pin "2") (pinfunction "2_2") (pintype "passive"))
    )
    (net (code "174") (name "Net-(LED10-G)") (class "Default")
      (node (ref "LED10") (pin "P$14") (pinfunction "G_P$14") (pintype "bidirectional"))
      (node (ref "R83") (pin "2") (pinfunction "2_2") (pintype "passive"))
    )
    (net (code "175") (name "Net-(LED11-A)") (class "Default")
      (node (ref "LED11") (pin "P$2") (pinfunction "A_P$2") (pintype "bidirectional"))
      (node (ref "R86") (pin "2") (pinfunction "2_2") (pintype "passive"))
    )
    (net (code "176") (name "Net-(LED11-B)") (class "Default")
      (node (ref "LED11") (pin "P$1") (pinfunction "B_P$1") (pintype "bidirectional"))
      (node (ref "R85") (pin "2") (pinfunction "2_2") (pintype "passive"))
    )
    (net (code "177") (name "Net-(LED11-C)") (class "Default")
      (node (ref "LED11") (pin "P$15") (pinfunction "C_P$15") (pintype "bidirectional"))
      (node (ref "R87") (pin "2") (pinfunction "2_2") (pintype "passive"))
    )
    (net (code "178") (name "Net-(LED11-D)") (class "Default")
      (node (ref "LED11") (pin "P$13") (pinfunction "D_P$13") (pintype "bidirectional"))
      (node (ref "R88") (pin "2") (pinfunction "2_2") (pintype "passive"))
    )
    (net (code "179") (name "Net-(LED11-E)") (class "Default")
      (node (ref "LED11") (pin "P$10") (pinfunction "E_P$10") (pintype "bidirectional"))
      (node (ref "R89") (pin "2") (pinfunction "2_2") (pintype "passive"))
    )
    (net (code "180") (name "Net-(LED11-F)") (class "Default")
      (node (ref "LED11") (pin "P$11") (pinfunction "F_P$11") (pintype "bidirectional"))
      (node (ref "R90") (pin "2") (pinfunction "2_2") (pintype "passive"))
    )
    (net (code "181") (name "Net-(LED11-G)") (class "Default")
      (node (ref "LED11") (pin "P$5") (pinfunction "G_P$5") (pintype "bidirectional"))
      (node (ref "R91") (pin "2") (pinfunction "2_2") (pintype "passive"))
    )
    (net (code "182") (name "Net-(LED11-H)") (class "Default")
      (node (ref "LED11") (pin "P$3") (pinfunction "H_P$3") (pintype "bidirectional"))
      (node (ref "R92") (pin "2") (pinfunction "2_2") (pintype "passive"))
    )
    (net (code "183") (name "Net-(LED11-K)") (class "Default")
      (node (ref "LED11") (pin "P$4") (pinfunction "K_P$4") (pintype "bidirectional"))
      (node (ref "R93") (pin "2") (pinfunction "2_2") (pintype "passive"))
    )
    (net (code "184") (name "Net-(LED11-M)") (class "Default")
      (node (ref "LED11") (pin "P$6") (pinfunction "M_P$6") (pintype "bidirectional"))
      (node (ref "R94") (pin "2") (pinfunction "2_2") (pintype "passive"))
    )
    (net (code "185") (name "Net-(LED11-N)") (class "Default")
      (node (ref "LED11") (pin "P$18") (pinfunction "N_P$18") (pintype "bidirectional"))
      (node (ref "R96") (pin "2") (pinfunction "2_2") (pintype "passive"))
    )
    (net (code "186") (name "Net-(LED11-P)") (class "Default")
      (node (ref "LED11") (pin "P$16") (pinfunction "P_P$16") (pintype "bidirectional"))
      (node (ref "R97") (pin "2") (pinfunction "2_2") (pintype "passive"))
    )
    (net (code "187") (name "Net-(LED11-R)") (class "Default")
      (node (ref "LED11") (pin "P$9") (pinfunction "R_P$9") (pintype "bidirectional"))
      (node (ref "R98") (pin "2") (pinfunction "2_2") (pintype "passive"))
    )
    (net (code "188") (name "Net-(LED11-S)") (class "Default")
      (node (ref "LED11") (pin "P$7") (pinfunction "S_P$7") (pintype "bidirectional"))
      (node (ref "R95") (pin "2") (pinfunction "2_2") (pintype "passive"))
    )
    (net (code "189") (name "Net-(LED11-U)") (class "Default")
      (node (ref "LED11") (pin "P$14") (pinfunction "U_P$14") (pintype "bidirectional"))
      (node (ref "R99") (pin "2") (pinfunction "2_2") (pintype "passive"))
    )
    (net (code "190") (name "Net-(LED12-A)") (class "Default")
      (node (ref "LED12") (pin "P$2") (pinfunction "A_P$2") (pintype "bidirectional"))
      (node (ref "R101") (pin "2") (pinfunction "2_2") (pintype "passive"))
    )
    (net (code "191") (name "Net-(LED12-B)") (class "Default")
      (node (ref "LED12") (pin "P$1") (pinfunction "B_P$1") (pintype "bidirectional"))
      (node (ref "R100") (pin "2") (pinfunction "2_2") (pintype "passive"))
    )
    (net (code "192") (name "Net-(LED12-C)") (class "Default")
      (node (ref "LED12") (pin "P$15") (pinfunction "C_P$15") (pintype "bidirectional"))
      (node (ref "R102") (pin "2") (pinfunction "2_2") (pintype "passive"))
    )
    (net (code "193") (name "Net-(LED12-D)") (class "Default")
      (node (ref "LED12") (pin "P$13") (pinfunction "D_P$13") (pintype "bidirectional"))
      (node (ref "R103") (pin "2") (pinfunction "2_2") (pintype "passive"))
    )
    (net (code "194") (name "Net-(LED12-E)") (class "Default")
      (node (ref "LED12") (pin "P$10") (pinfunction "E_P$10") (pintype "bidirectional"))
      (node (ref "R104") (pin "2") (pinfunction "2_2") (pintype "passive"))
    )
    (net (code "195") (name "Net-(LED12-F)") (class "Default")
      (node (ref "LED12") (pin "P$11") (pinfunction "F_P$11") (pintype "bidirectional"))
      (node (ref "R105") (pin "2") (pinfunction "2_2") (pintype "passive"))
    )
    (net (code "196") (name "Net-(LED12-G)") (class "Default")
      (node (ref "LED12") (pin "P$5") (pinfunction "G_P$5") (pintype "bidirectional"))
      (node (ref "R107") (pin "2") (pinfunction "2_2") (pintype "passive"))
    )
    (net (code "197") (name "Net-(LED12-H)") (class "Default")
      (node (ref "LED12") (pin "P$3") (pinfunction "H_P$3") (pintype "bidirectional"))
      (node (ref "R106") (pin "2") (pinfunction "2_2") (pintype "passive"))
    )
    (net (code "198") (name "Net-(LED12-P)") (class "Default")
      (node (ref "LED12") (pin "P$16") (pinfunction "P_P$16") (pintype "bidirectional"))
      (node (ref "R109") (pin "2") (pinfunction "2_2") (pintype "passive"))
    )
    (net (code "199") (name "Net-(LED12-U)") (class "Default")
      (node (ref "LED12") (pin "P$14") (pinfunction "U_P$14") (pintype "bidirectional"))
      (node (ref "R108") (pin "2") (pinfunction "2_2") (pintype "passive"))
    )
    (net (code "200") (name "Net-(LED13-A)") (class "Default")
      (node (ref "LED13") (pin "P$2") (pinfunction "A_P$2") (pintype "bidirectional"))
      (node (ref "R111") (pin "2") (pinfunction "2_2") (pintype "passive"))
    )
    (net (code "201") (name "Net-(LED13-B)") (class "Default")
      (node (ref "LED13") (pin "P$1") (pinfunction "B_P$1") (pintype "bidirectional"))
      (node (ref "R110") (pin "2") (pinfunction "2_2") (pintype "passive"))
    )
    (net (code "202") (name "Net-(LED13-C)") (class "Default")
      (node (ref "LED13") (pin "P$15") (pinfunction "C_P$15") (pintype "bidirectional"))
      (node (ref "R112") (pin "2") (pinfunction "2_2") (pintype "passive"))
    )
    (net (code "203") (name "Net-(LED13-D)") (class "Default")
      (node (ref "LED13") (pin "P$13") (pinfunction "D_P$13") (pintype "bidirectional"))
      (node (ref "R113") (pin "2") (pinfunction "2_2") (pintype "passive"))
    )
    (net (code "204") (name "Net-(LED13-E)") (class "Default")
      (node (ref "LED13") (pin "P$10") (pinfunction "E_P$10") (pintype "bidirectional"))
      (node (ref "R114") (pin "2") (pinfunction "2_2") (pintype "passive"))
    )
    (net (code "205") (name "Net-(LED13-F)") (class "Default")
      (node (ref "LED13") (pin "P$11") (pinfunction "F_P$11") (pintype "bidirectional"))
      (node (ref "R115") (pin "2") (pinfunction "2_2") (pintype "passive"))
    )
    (net (code "206") (name "Net-(LED13-G)") (class "Default")
      (node (ref "LED13") (pin "P$5") (pinfunction "G_P$5") (pintype "bidirectional"))
      (node (ref "R117") (pin "2") (pinfunction "2_2") (pintype "passive"))
    )
    (net (code "207") (name "Net-(LED13-H)") (class "Default")
      (node (ref "LED13") (pin "P$3") (pinfunction "H_P$3") (pintype "bidirectional"))
      (node (ref "R116") (pin "2") (pinfunction "2_2") (pintype "passive"))
    )
    (net (code "208") (name "Net-(LED13-K)") (class "Default")
      (node (ref "LED13") (pin "P$4") (pinfunction "K_P$4") (pintype "bidirectional"))
      (node (ref "R118") (pin "2") (pinfunction "2_2") (pintype "passive"))
    )
    (net (code "209") (name "Net-(LED13-M)") (class "Default")
      (node (ref "LED13") (pin "P$6") (pinfunction "M_P$6") (pintype "bidirectional"))
      (node (ref "R119") (pin "2") (pinfunction "2_2") (pintype "passive"))
    )
    (net (code "210") (name "Net-(LED13-N)") (class "Default")
      (node (ref "LED13") (pin "P$18") (pinfunction "N_P$18") (pintype "bidirectional"))
      (node (ref "R120") (pin "2") (pinfunction "2_2") (pintype "passive"))
    )
    (net (code "211") (name "Net-(LED13-P)") (class "Default")
      (node (ref "LED13") (pin "P$16") (pinfunction "P_P$16") (pintype "bidirectional"))
      (node (ref "R121") (pin "2") (pinfunction "2_2") (pintype "passive"))
    )
    (net (code "212") (name "Net-(LED13-R)") (class "Default")
      (node (ref "LED13") (pin "P$9") (pinfunction "R_P$9") (pintype "bidirectional"))
      (node (ref "R122") (pin "2") (pinfunction "2_2") (pintype "passive"))
    )
    (net (code "213") (name "Net-(LED13-S)") (class "Default")
      (node (ref "LED13") (pin "P$7") (pinfunction "S_P$7") (pintype "bidirectional"))
      (node (ref "R123") (pin "2") (pinfunction "2_2") (pintype "passive"))
    )
    (net (code "214") (name "Net-(LED13-T)") (class "Default")
      (node (ref "LED13") (pin "P$8") (pinfunction "T_P$8") (pintype "bidirectional"))
      (node (ref "R124") (pin "2") (pinfunction "2_2") (pintype "passive"))
    )
    (net (code "215") (name "Net-(LED13-U)") (class "Default")
      (node (ref "LED13") (pin "P$14") (pinfunction "U_P$14") (pintype "bidirectional"))
      (node (ref "R125") (pin "2") (pinfunction "2_2") (pintype "passive"))
    )
    (net (code "216") (name "Net-(Q1-D)") (class "Default")
      (node (ref "Q1") (pin "3") (pinfunction "D_3") (pintype "passive"))
      (node (ref "R1") (pin "1") (pinfunction "1_1") (pintype "passive"))
      (node (ref "R2") (pin "1") (pinfunction "1_1") (pintype "passive"))
    )
    (net (code "217") (name "Net-(Q2-D)") (class "Default")
      (node (ref "Q2") (pin "3") (pinfunction "D_3") (pintype "passive"))
      (node (ref "R3") (pin "1") (pinfunction "1_1") (pintype "passive"))
    )
    (net (code "218") (name "Net-(Q3-D)") (class "Default")
      (node (ref "Q3") (pin "3") (pinfunction "D_3") (pintype "passive"))
      (node (ref "R4") (pin "1") (pinfunction "1_1") (pintype "passive"))
    )
    (net (code "219") (name "Net-(Q4-D)") (class "Default")
      (node (ref "Q4") (pin "3") (pinfunction "D_3") (pintype "passive"))
      (node (ref "R5") (pin "1") (pinfunction "1_1") (pintype "passive"))
    )
    (net (code "220") (name "Net-(Q5-D)") (class "Default")
      (node (ref "Q5") (pin "3") (pinfunction "D_3") (pintype "passive"))
      (node (ref "R6") (pin "1") (pinfunction "1_1") (pintype "passive"))
    )
    (net (code "221") (name "Net-(Q6-D)") (class "Default")
      (node (ref "Q6") (pin "3") (pinfunction "D_3") (pintype "passive"))
      (node (ref "R7") (pin "1") (pinfunction "1_1") (pintype "passive"))
    )
    (net (code "222") (name "Net-(Q7-D)") (class "Default")
      (node (ref "Q7") (pin "3") (pinfunction "D_3") (pintype "passive"))
      (node (ref "R8") (pin "1") (pinfunction "1_1") (pintype "passive"))
    )
    (net (code "223") (name "Net-(Q8-D)") (class "Default")
      (node (ref "Q8") (pin "3") (pinfunction "D_3") (pintype "passive"))
      (node (ref "R9") (pin "1") (pinfunction "1_1") (pintype "passive"))
    )
    (net (code "224") (name "Net-(Q9-D)") (class "Default")
      (node (ref "Q9") (pin "3") (pinfunction "D_3") (pintype "passive"))
      (node (ref "R10") (pin "1") (pinfunction "1_1") (pintype "passive"))
    )
    (net (code "225") (name "Net-(Q10-D)") (class "Default")
      (node (ref "Q10") (pin "3") (pinfunction "D_3") (pintype "passive"))
      (node (ref "R11") (pin "1") (pinfunction "1_1") (pintype "passive"))
    )
    (net (code "226") (name "Net-(Q11-D)") (class "Default")
      (node (ref "Q11") (pin "3") (pinfunction "D_3") (pintype "passive"))
      (node (ref "R12") (pin "1") (pinfunction "1_1") (pintype "passive"))
    )
    (net (code "227") (name "Net-(Q12-D)") (class "Default")
      (node (ref "Q12") (pin "3") (pinfunction "D_3") (pintype "passive"))
      (node (ref "R13") (pin "1") (pinfunction "1_1") (pintype "passive"))
    )
    (net (code "228") (name "Net-(Q13-D)") (class "Default")
      (node (ref "Q13") (pin "3") (pinfunction "D_3") (pintype "passive"))
      (node (ref "R14") (pin "1") (pinfunction "1_1") (pintype "passive"))
    )
    (net (code "229") (name "Net-(Q14-D)") (class "Default")
      (node (ref "Q14") (pin "3") (pinfunction "D_3") (pintype "passive"))
      (node (ref "R15") (pin "1") (pinfunction "1_1") (pintype "passive"))
      (node (ref "R16") (pin "1") (pinfunction "1_1") (pintype "passive"))
    )
    (net (code "230") (name "Net-(Q15-D)") (class "Default")
      (node (ref "Q15") (pin "3") (pinfunction "D_3") (pintype "passive"))
      (node (ref "R17") (pin "1") (pinfunction "1_1") (pintype "passive"))
    )
    (net (code "231") (name "Net-(Q16-D)") (class "Default")
      (node (ref "Q16") (pin "3") (pinfunction "D_3") (pintype "passive"))
      (node (ref "R18") (pin "1") (pinfunction "1_1") (pintype "passive"))
    )
    (net (code "232") (name "Net-(Q17-D)") (class "Default")
      (node (ref "Q17") (pin "3") (pinfunction "D_3") (pintype "passive"))
      (node (ref "R19") (pin "1") (pinfunction "1_1") (pintype "passive"))
    )
    (net (code "233") (name "Net-(Q18-D)") (class "Default")
      (node (ref "Q18") (pin "3") (pinfunction "D_3") (pintype "passive"))
      (node (ref "R20") (pin "1") (pinfunction "1_1") (pintype "passive"))
    )
    (net (code "234") (name "Net-(Q19-D)") (class "Default")
      (node (ref "Q19") (pin "3") (pinfunction "D_3") (pintype "passive"))
      (node (ref "R21") (pin "1") (pinfunction "1_1") (pintype "passive"))
    )
    (net (code "235") (name "Net-(Q20-D)") (class "Default")
      (node (ref "Q20") (pin "3") (pinfunction "D_3") (pintype "passive"))
      (node (ref "R22") (pin "1") (pinfunction "1_1") (pintype "passive"))
    )
    (net (code "236") (name "Net-(Q21-D)") (class "Default")
      (node (ref "Q21") (pin "3") (pinfunction "D_3") (pintype "passive"))
      (node (ref "R23") (pin "1") (pinfunction "1_1") (pintype "passive"))
    )
    (net (code "237") (name "Net-(Q22-D)") (class "Default")
      (node (ref "Q22") (pin "3") (pinfunction "D_3") (pintype "passive"))
      (node (ref "R24") (pin "1") (pinfunction "1_1") (pintype "passive"))
    )
    (net (code "238") (name "Net-(Q23-D)") (class "Default")
      (node (ref "Q23") (pin "3") (pinfunction "D_3") (pintype "passive"))
      (node (ref "R25") (pin "1") (pinfunction "1_1") (pintype "passive"))
    )
    (net (code "239") (name "Net-(Q24-D)") (class "Default")
      (node (ref "Q24") (pin "3") (pinfunction "D_3") (pintype "passive"))
      (node (ref "R26") (pin "1") (pinfunction "1_1") (pintype "passive"))
    )
    (net (code "240") (name "Net-(Q25-D)") (class "Default")
      (node (ref "Q25") (pin "3") (pinfunction "D_3") (pintype "passive"))
      (node (ref "R27") (pin "1") (pinfunction "1_1") (pintype "passive"))
    )
    (net (code "241") (name "Net-(Q26-D)") (class "Default")
      (node (ref "Q26") (pin "3") (pinfunction "D_3") (pintype "passive"))
      (node (ref "R28") (pin "1") (pinfunction "1_1") (pintype "passive"))
    )
    (net (code "242") (name "Net-(Q27-D)") (class "Default")
      (node (ref "Q27") (pin "3") (pinfunction "D_3") (pintype "passive"))
      (node (ref "R29") (pin "1") (pinfunction "1_1") (pintype "passive"))
      (node (ref "R30") (pin "1") (pinfunction "1_1") (pintype "passive"))
    )
    (net (code "243") (name "Net-(Q28-D)") (class "Default")
      (node (ref "Q28") (pin "3") (pinfunction "D_3") (pintype "passive"))
      (node (ref "R31") (pin "1") (pinfunction "1_1") (pintype "passive"))
    )
    (net (code "244") (name "Net-(Q29-D)") (class "Default")
      (node (ref "Q29") (pin "3") (pinfunction "D_3") (pintype "passive"))
      (node (ref "R32") (pin "1") (pinfunction "1_1") (pintype "passive"))
    )
    (net (code "245") (name "Net-(Q30-D)") (class "Default")
      (node (ref "Q30") (pin "3") (pinfunction "D_3") (pintype "passive"))
      (node (ref "R33") (pin "1") (pinfunction "1_1") (pintype "passive"))
    )
    (net (code "246") (name "Net-(Q31-D)") (class "Default")
      (node (ref "Q31") (pin "3") (pinfunction "D_3") (pintype "passive"))
      (node (ref "R34") (pin "1") (pinfunction "1_1") (pintype "passive"))
    )
    (net (code "247") (name "Net-(Q32-D)") (class "Default")
      (node (ref "Q32") (pin "3") (pinfunction "D_3") (pintype "passive"))
      (node (ref "R35") (pin "1") (pinfunction "1_1") (pintype "passive"))
    )
    (net (code "248") (name "Net-(Q33-D)") (class "Default")
      (node (ref "Q33") (pin "3") (pinfunction "D_3") (pintype "passive"))
      (node (ref "R36") (pin "1") (pinfunction "1_1") (pintype "passive"))
    )
    (net (code "249") (name "Net-(Q34-D)") (class "Default")
      (node (ref "Q34") (pin "3") (pinfunction "D_3") (pintype "passive"))
      (node (ref "R37") (pin "1") (pinfunction "1_1") (pintype "passive"))
    )
    (net (code "250") (name "Net-(Q35-D)") (class "Default")
      (node (ref "Q35") (pin "3") (pinfunction "D_3") (pintype "passive"))
      (node (ref "R38") (pin "1") (pinfunction "1_1") (pintype "passive"))
    )
    (net (code "251") (name "Net-(Q36-D)") (class "Default")
      (node (ref "Q36") (pin "3") (pinfunction "D_3") (pintype "passive"))
      (node (ref "R39") (pin "1") (pinfunction "1_1") (pintype "passive"))
    )
    (net (code "252") (name "Net-(Q37-D)") (class "Default")
      (node (ref "Q37") (pin "3") (pinfunction "D_3") (pintype "passive"))
      (node (ref "R40") (pin "1") (pinfunction "1_1") (pintype "passive"))
    )
    (net (code "253") (name "Net-(Q38-D)") (class "Default")
      (node (ref "Q38") (pin "3") (pinfunction "D_3") (pintype "passive"))
      (node (ref "R41") (pin "1") (pinfunction "1_1") (pintype "passive"))
    )
    (net (code "254") (name "Net-(Q39-D)") (class "Default")
      (node (ref "Q39") (pin "3") (pinfunction "D_3") (pintype "passive"))
      (node (ref "R42") (pin "1") (pinfunction "1_1") (pintype "passive"))
    )
    (net (code "255") (name "Net-(Q40-D)") (class "Default")
      (node (ref "Q40") (pin "3") (pinfunction "D_3") (pintype "passive"))
      (node (ref "R43") (pin "1") (pinfunction "1_1") (pintype "passive"))
      (node (ref "R44") (pin "1") (pinfunction "1_1") (pintype "passive"))
    )
    (net (code "256") (name "Net-(Q41-D)") (class "Default")
      (node (ref "Q41") (pin "3") (pinfunction "D_3") (pintype "passive"))
      (node (ref "R45") (pin "1") (pinfunction "1_1") (pintype "passive"))
    )
    (net (code "257") (name "Net-(Q42-D)") (class "Default")
      (node (ref "Q42") (pin "3") (pinfunction "D_3") (pintype "passive"))
      (node (ref "R46") (pin "1") (pinfunction "1_1") (pintype "passive"))
    )
    (net (code "258") (name "Net-(Q43-D)") (class "Default")
      (node (ref "Q43") (pin "3") (pinfunction "D_3") (pintype "passive"))
      (node (ref "R47") (pin "1") (pinfunction "1_1") (pintype "passive"))
      (node (ref "R48") (pin "1") (pinfunction "1_1") (pintype "passive"))
    )
    (net (code "259") (name "Net-(Q44-D)") (class "Default")
      (node (ref "Q44") (pin "3") (pinfunction "D_3") (pintype "passive"))
      (node (ref "R49") (pin "1") (pinfunction "1_1") (pintype "passive"))
      (node (ref "R50") (pin "1") (pinfunction "1_1") (pintype "passive"))
    )
    (net (code "260") (name "Net-(Q45-D)") (class "Default")
      (node (ref "Q45") (pin "3") (pinfunction "D_3") (pintype "passive"))
      (node (ref "R51") (pin "1") (pinfunction "1_1") (pintype "passive"))
    )
    (net (code "261") (name "Net-(Q46-D)") (class "Default")
      (node (ref "Q46") (pin "3") (pinfunction "D_3") (pintype "passive"))
      (node (ref "R52") (pin "1") (pinfunction "1_1") (pintype "passive"))
      (node (ref "R53") (pin "1") (pinfunction "1_1") (pintype "passive"))
    )
    (net (code "262") (name "Net-(Q47-D)") (class "Default")
      (node (ref "Q47") (pin "3") (pinfunction "D_3") (pintype "passive"))
      (node (ref "R54") (pin "1") (pinfunction "1_1") (pintype "passive"))
    )
    (net (code "263") (name "Net-(Q48-D)") (class "Default")
      (node (ref "Q48") (pin "3") (pinfunction "D_3") (pintype "passive"))
      (node (ref "R55") (pin "1") (pinfunction "1_1") (pintype "passive"))
    )
    (net (code "264") (name "Net-(Q49-D)") (class "Default")
      (node (ref "Q49") (pin "3") (pinfunction "D_3") (pintype "passive"))
      (node (ref "R56") (pin "1") (pinfunction "1_1") (pintype "passive"))
      (node (ref "R57") (pin "1") (pinfunction "1_1") (pintype "passive"))
    )
    (net (code "265") (name "Net-(Q50-D)") (class "Default")
      (node (ref "Q50") (pin "3") (pinfunction "D_3") (pintype "passive"))
      (node (ref "R58") (pin "1") (pinfunction "1_1") (pintype "passive"))
    )
    (net (code "266") (name "Net-(Q51-D)") (class "Default")
      (node (ref "Q51") (pin "3") (pinfunction "D_3") (pintype "passive"))
      (node (ref "R59") (pin "1") (pinfunction "1_1") (pintype "passive"))
      (node (ref "R60") (pin "1") (pinfunction "1_1") (pintype "passive"))
    )
    (net (code "267") (name "Net-(Q52-D)") (class "Default")
      (node (ref "Q52") (pin "3") (pinfunction "D_3") (pintype "passive"))
      (node (ref "R61") (pin "1") (pinfunction "1_1") (pintype "passive"))
    )
    (net (code "268") (name "Net-(Q53-D)") (class "Default")
      (node (ref "Q53") (pin "3") (pinfunction "D_3") (pintype "passive"))
      (node (ref "R62") (pin "1") (pinfunction "1_1") (pintype "passive"))
    )
    (net (code "269") (name "Net-(Q54-D)") (class "Default")
      (node (ref "Q54") (pin "3") (pinfunction "D_3") (pintype "passive"))
      (node (ref "R63") (pin "1") (pinfunction "1_1") (pintype "passive"))
      (node (ref "R64") (pin "1") (pinfunction "1_1") (pintype "passive"))
    )
    (net (code "270") (name "Net-(Q55-D)") (class "Default")
      (node (ref "Q55") (pin "3") (pinfunction "D_3") (pintype "passive"))
      (node (ref "R65") (pin "1") (pinfunction "1_1") (pintype "passive"))
      (node (ref "R66") (pin "1") (pinfunction "1_1") (pintype "passive"))
    )
    (net (code "271") (name "Net-(Q56-D)") (class "Default")
      (node (ref "Q56") (pin "3") (pinfunction "D_3") (pintype "passive"))
      (node (ref "R67") (pin "1") (pinfunction "1_1") (pintype "passive"))
      (node (ref "R68") (pin "1") (pinfunction "1_1") (pintype "passive"))
    )
    (net (code "272") (name "Net-(Q57-D)") (class "Default")
      (node (ref "Q57") (pin "3") (pinfunction "D_3") (pintype "passive"))
      (node (ref "R69") (pin "1") (pinfunction "1_1") (pintype "passive"))
    )
    (net (code "273") (name "Net-(Q58-D)") (class "Default")
      (node (ref "Q58") (pin "3") (pinfunction "D_3") (pintype "passive"))
      (node (ref "R70") (pin "1") (pinfunction "1_1") (pintype "passive"))
      (node (ref "R71") (pin "1") (pinfunction "1_1") (pintype "passive"))
    )
    (net (code "274") (name "Net-(Q59-D)") (class "Default")
      (node (ref "Q59") (pin "3") (pinfunction "D_3") (pintype "passive"))
      (node (ref "R72") (pin "1") (pinfunction "1_1") (pintype "passive"))
    )
    (net (code "275") (name "Net-(Q60-D)") (class "Default")
      (node (ref "Q60") (pin "3") (pinfunction "D_3") (pintype "passive"))
      (node (ref "R73") (pin "1") (pinfunction "1_1") (pintype "passive"))
    )
    (net (code "276") (name "Net-(Q61-D)") (class "Default")
      (node (ref "Q61") (pin "3") (pinfunction "D_3") (pintype "passive"))
      (node (ref "R74") (pin "1") (pinfunction "1_1") (pintype "passive"))
    )
    (net (code "277") (name "Net-(Q62-D)") (class "Default")
      (node (ref "Q62") (pin "3") (pinfunction "D_3") (pintype "passive"))
      (node (ref "R75") (pin "1") (pinfunction "1_1") (pintype "passive"))
    )
    (net (code "278") (name "Net-(Q63-D)") (class "Default")
      (node (ref "Q63") (pin "3") (pinfunction "D_3") (pintype "passive"))
      (node (ref "R76") (pin "1") (pinfunction "1_1") (pintype "passive"))
    )
    (net (code "279") (name "Net-(Q64-D)") (class "Default")
      (node (ref "Q64") (pin "3") (pinfunction "D_3") (pintype "passive"))
      (node (ref "R77") (pin "1") (pinfunction "1_1") (pintype "passive"))
    )
    (net (code "280") (name "Net-(Q65-D)") (class "Default")
      (node (ref "Q65") (pin "3") (pinfunction "D_3") (pintype "passive"))
      (node (ref "R78") (pin "1") (pinfunction "1_1") (pintype "passive"))
    )
    (net (code "281") (name "Net-(Q66-D)") (class "Default")
      (node (ref "Q66") (pin "3") (pinfunction "D_3") (pintype "passive"))
      (node (ref "R79") (pin "1") (pinfunction "1_1") (pintype "passive"))
    )
    (net (code "282") (name "Net-(Q67-D)") (class "Default")
      (node (ref "Q67") (pin "3") (pinfunction "D_3") (pintype "passive"))
      (node (ref "R80") (pin "1") (pinfunction "1_1") (pintype "passive"))
    )
    (net (code "283") (name "Net-(Q68-D)") (class "Default")
      (node (ref "Q68") (pin "3") (pinfunction "D_3") (pintype "passive"))
      (node (ref "R81") (pin "1") (pinfunction "1_1") (pintype "passive"))
    )
    (net (code "284") (name "Net-(Q69-D)") (class "Default")
      (node (ref "Q69") (pin "3") (pinfunction "D_3") (pintype "passive"))
      (node (ref "R82") (pin "1") (pinfunction "1_1") (pintype "passive"))
    )
    (net (code "285") (name "Net-(Q70-D)") (class "Default")
      (node (ref "Q70") (pin "3") (pinfunction "D_3") (pintype "passive"))
      (node (ref "R83") (pin "1") (pinfunction "1_1") (pintype "passive"))
    )
    (net (code "286") (name "Net-(Q71-D)") (class "Default")
      (node (ref "Q71") (pin "3") (pinfunction "D_3") (pintype "passive"))
      (node (ref "R84") (pin "1") (pinfunction "1_1") (pintype "passive"))
    )
    (net (code "287") (name "Net-(Q72-D)") (class "Default")
      (node (ref "Q72") (pin "3") (pinfunction "D_3") (pintype "passive"))
      (node (ref "R85") (pin "1") (pinfunction "1_1") (pintype "passive"))
      (node (ref "R86") (pin "1") (pinfunction "1_1") (pintype "passive"))
    )
    (net (code "288") (name "Net-(Q73-D)") (class "Default")
      (node (ref "Q73") (pin "3") (pinfunction "D_3") (pintype "passive"))
      (node (ref "R87") (pin "1") (pinfunction "1_1") (pintype "passive"))
    )
    (net (code "289") (name "Net-(Q74-D)") (class "Default")
      (node (ref "Q74") (pin "3") (pinfunction "D_3") (pintype "passive"))
      (node (ref "R88") (pin "1") (pinfunction "1_1") (pintype "passive"))
    )
    (net (code "290") (name "Net-(Q75-D)") (class "Default")
      (node (ref "Q75") (pin "3") (pinfunction "D_3") (pintype "passive"))
      (node (ref "R89") (pin "1") (pinfunction "1_1") (pintype "passive"))
      (node (ref "R90") (pin "1") (pinfunction "1_1") (pintype "passive"))
    )
    (net (code "291") (name "Net-(Q76-D)") (class "Default")
      (node (ref "Q76") (pin "3") (pinfunction "D_3") (pintype "passive"))
      (node (ref "R91") (pin "1") (pinfunction "1_1") (pintype "passive"))
    )
    (net (code "292") (name "Net-(Q77-D)") (class "Default")
      (node (ref "Q77") (pin "3") (pinfunction "D_3") (pintype "passive"))
      (node (ref "R92") (pin "1") (pinfunction "1_1") (pintype "passive"))
    )
    (net (code "293") (name "Net-(Q78-D)") (class "Default")
      (node (ref "Q78") (pin "3") (pinfunction "D_3") (pintype "passive"))
      (node (ref "R93") (pin "1") (pinfunction "1_1") (pintype "passive"))
    )
    (net (code "294") (name "Net-(Q79-D)") (class "Default")
      (node (ref "Q79") (pin "3") (pinfunction "D_3") (pintype "passive"))
      (node (ref "R94") (pin "1") (pinfunction "1_1") (pintype "passive"))
      (node (ref "R95") (pin "1") (pinfunction "1_1") (pintype "passive"))
    )
    (net (code "295") (name "Net-(Q80-D)") (class "Default")
      (node (ref "Q80") (pin "3") (pinfunction "D_3") (pintype "passive"))
      (node (ref "R96") (pin "1") (pinfunction "1_1") (pintype "passive"))
    )
    (net (code "296") (name "Net-(Q81-D)") (class "Default")
      (node (ref "Q81") (pin "3") (pinfunction "D_3") (pintype "passive"))
      (node (ref "R97") (pin "1") (pinfunction "1_1") (pintype "passive"))
    )
    (net (code "297") (name "Net-(Q82-D)") (class "Default")
      (node (ref "Q82") (pin "3") (pinfunction "D_3") (pintype "passive"))
      (node (ref "R98") (pin "1") (pinfunction "1_1") (pintype "passive"))
    )
    (net (code "298") (name "Net-(Q83-D)") (class "Default")
      (node (ref "Q83") (pin "3") (pinfunction "D_3") (pintype "passive"))
      (node (ref "R99") (pin "1") (pinfunction "1_1") (pintype "passive"))
    )
    (net (code "299") (name "Net-(Q84-D)") (class "Default")
      (node (ref "Q84") (pin "3") (pinfunction "D_3") (pintype "passive"))
      (node (ref "R100") (pin "1") (pinfunction "1_1") (pintype "passive"))
      (node (ref "R101") (pin "1") (pinfunction "1_1") (pintype "passive"))
    )
    (net (code "300") (name "Net-(Q85-D)") (class "Default")
      (node (ref "Q85") (pin "3") (pinfunction "D_3") (pintype "passive"))
      (node (ref "R102") (pin "1") (pinfunction "1_1") (pintype "passive"))
    )
    (net (code "301") (name "Net-(Q86-D)") (class "Default")
      (node (ref "Q86") (pin "3") (pinfunction "D_3") (pintype "passive"))
      (node (ref "R103") (pin "1") (pinfunction "1_1") (pintype "passive"))
    )
    (net (code "302") (name "Net-(Q87-D)") (class "Default")
      (node (ref "Q87") (pin "3") (pinfunction "D_3") (pintype "passive"))
      (node (ref "R104") (pin "1") (pinfunction "1_1") (pintype "passive"))
      (node (ref "R105") (pin "1") (pinfunction "1_1") (pintype "passive"))
    )
    (net (code "303") (name "Net-(Q88-D)") (class "Default")
      (node (ref "Q88") (pin "3") (pinfunction "D_3") (pintype "passive"))
      (node (ref "R106") (pin "1") (pinfunction "1_1") (pintype "passive"))
      (node (ref "R107") (pin "1") (pinfunction "1_1") (pintype "passive"))
    )
    (net (code "304") (name "Net-(Q89-D)") (class "Default")
      (node (ref "Q89") (pin "3") (pinfunction "D_3") (pintype "passive"))
      (node (ref "R108") (pin "1") (pinfunction "1_1") (pintype "passive"))
      (node (ref "R109") (pin "1") (pinfunction "1_1") (pintype "passive"))
    )
    (net (code "305") (name "Net-(Q90-D)") (class "Default")
      (node (ref "Q90") (pin "3") (pinfunction "D_3") (pintype "passive"))
      (node (ref "R110") (pin "1") (pinfunction "1_1") (pintype "passive"))
      (node (ref "R111") (pin "1") (pinfunction "1_1") (pintype "passive"))
    )
    (net (code "306") (name "Net-(Q91-D)") (class "Default")
      (node (ref "Q91") (pin "3") (pinfunction "D_3") (pintype "passive"))
      (node (ref "R112") (pin "1") (pinfunction "1_1") (pintype "passive"))
    )
    (net (code "307") (name "Net-(Q92-D)") (class "Default")
      (node (ref "Q92") (pin "3") (pinfunction "D_3") (pintype "passive"))
      (node (ref "R113") (pin "1") (pinfunction "1_1") (pintype "passive"))
    )
    (net (code "308") (name "Net-(Q93-D)") (class "Default")
      (node (ref "Q93") (pin "3") (pinfunction "D_3") (pintype "passive"))
      (node (ref "R114") (pin "1") (pinfunction "1_1") (pintype "passive"))
      (node (ref "R115") (pin "1") (pinfunction "1_1") (pintype "passive"))
    )
    (net (code "309") (name "Net-(Q94-D)") (class "Default")
      (node (ref "Q94") (pin "3") (pinfunction "D_3") (pintype "passive"))
      (node (ref "R116") (pin "1") (pinfunction "1_1") (pintype "passive"))
      (node (ref "R117") (pin "1") (pinfunction "1_1") (pintype "passive"))
    )
    (net (code "310") (name "Net-(Q95-D)") (class "Default")
      (node (ref "Q95") (pin "3") (pinfunction "D_3") (pintype "passive"))
      (node (ref "R118") (pin "1") (pinfunction "1_1") (pintype "passive"))
    )
    (net (code "311") (name "Net-(Q96-D)") (class "Default")
      (node (ref "Q96") (pin "3") (pinfunction "D_3") (pintype "passive"))
      (node (ref "R119") (pin "1") (pinfunction "1_1") (pintype "passive"))
    )
    (net (code "312") (name "Net-(Q97-D)") (class "Default")
      (node (ref "Q97") (pin "3") (pinfunction "D_3") (pintype "passive"))
      (node (ref "R120") (pin "1") (pinfunction "1_1") (pintype "passive"))
    )
    (net (code "313") (name "Net-(Q98-D)") (class "Default")
      (node (ref "Q98") (pin "3") (pinfunction "D_3") (pintype "passive"))
      (node (ref "R121") (pin "1") (pinfunction "1_1") (pintype "passive"))
    )
    (net (code "314") (name "Net-(Q99-D)") (class "Default")
      (node (ref "Q99") (pin "3") (pinfunction "D_3") (pintype "passive"))
      (node (ref "R122") (pin "1") (pinfunction "1_1") (pintype "passive"))
    )
    (net (code "315") (name "Net-(Q100-D)") (class "Default")
      (node (ref "Q100") (pin "3") (pinfunction "D_3") (pintype "passive"))
      (node (ref "R123") (pin "1") (pinfunction "1_1") (pintype "passive"))
    )
    (net (code "316") (name "Net-(Q101-D)") (class "Default")
      (node (ref "Q101") (pin "3") (pinfunction "D_3") (pintype "passive"))
      (node (ref "R124") (pin "1") (pinfunction "1_1") (pintype "passive"))
    )
    (net (code "317") (name "Net-(Q102-D)") (class "Default")
      (node (ref "Q102") (pin "3") (pinfunction "D_3") (pintype "passive"))
      (node (ref "R125") (pin "1") (pinfunction "1_1") (pintype "passive"))
    )
    (net (code "318") (name "SEC_TENS_SEG_AD") (class "Default")
      (node (ref "D_BUS") (pin "8") (pinfunction "8_8") (pintype "passive"))
      (node (ref "Q27") (pin "2") (pinfunction "G_2") (pintype "passive"))
    )
    (net (code "319") (name "SEC_TENS_SEG_B") (class "Default")
      (node (ref "D_BUS") (pin "9") (pinfunction "9_9") (pintype "passive"))
      (node (ref "Q28") (pin "2") (pinfunction "G_2") (pintype "passive"))
    )
    (net (code "320") (name "SEC_TENS_SEG_C") (class "Default")
      (node (ref "D_BUS") (pin "10") (pinfunction "10_10") (pintype "passive"))
      (node (ref "Q29") (pin "2") (pinfunction "G_2") (pintype "passive"))
    )
    (net (code "321") (name "SEC_TENS_SEG_E") (class "Default")
      (node (ref "D_BUS") (pin "11") (pinfunction "11_11") (pintype "passive"))
      (node (ref "Q30") (pin "2") (pinfunction "G_2") (pintype "passive"))
    )
    (net (code "322") (name "SEC_TENS_SEG_F") (class "Default")
      (node (ref "D_BUS") (pin "12") (pinfunction "12_12") (pintype "passive"))
      (node (ref "Q31") (pin "2") (pinfunction "G_2") (pintype "passive"))
    )
    (net (code "323") (name "SEC_TENS_SEG_G") (class "Default")
      (node (ref "D_BUS") (pin "13") (pinfunction "13_13") (pintype "passive"))
      (node (ref "Q32") (pin "2") (pinfunction "G_2") (pintype "passive"))
    )
    (net (code "324") (name "SEC_UNIT_SEG_A") (class "Default")
      (node (ref "D_BUS") (pin "1") (pinfunction "1_1") (pintype "passive"))
      (node (ref "Q33") (pin "2") (pinfunction "G_2") (pintype "passive"))
    )
    (net (code "325") (name "SEC_UNIT_SEG_B") (class "Default")
      (node (ref "D_BUS") (pin "2") (pinfunction "2_2") (pintype "passive"))
      (node (ref "Q34") (pin "2") (pinfunction "G_2") (pintype "passive"))
    )
    (net (code "326") (name "SEC_UNIT_SEG_C") (class "Default")
      (node (ref "D_BUS") (pin "3") (pinfunction "3_3") (pintype "passive"))
      (node (ref "Q35") (pin "2") (pinfunction "G_2") (pintype "passive"))
    )
    (net (code "327") (name "SEC_UNIT_SEG_D") (class "Default")
      (node (ref "D_BUS") (pin "4") (pinfunction "4_4") (pintype "passive"))
      (node (ref "Q36") (pin "2") (pinfunction "G_2") (pintype "passive"))
    )
    (net (code "328") (name "SEC_UNIT_SEG_E") (class "Default")
      (node (ref "D_BUS") (pin "5") (pinfunction "5_5") (pintype "passive"))
      (node (ref "Q37") (pin "2") (pinfunction "G_2") (pintype "passive"))
    )
    (net (code "329") (name "SEC_UNIT_SEG_F") (class "Default")
      (node (ref "D_BUS") (pin "6") (pinfunction "6_6") (pintype "passive"))
      (node (ref "Q38") (pin "2") (pinfunction "G_2") (pintype "passive"))
    )
    (net (code "330") (name "SEC_UNIT_SEG_G") (class "Default")
      (node (ref "D_BUS") (pin "7") (pinfunction "7_7") (pintype "passive"))
      (node (ref "Q39") (pin "2") (pinfunction "G_2") (pintype "passive"))
    )
    (net (code "331") (name "VDD") (class "Default")
      (node (ref "A_BUS") (pin "38") (pinfunction "38_38") (pintype "passive"))
      (node (ref "A_BUS") (pin "40") (pinfunction "40_40") (pintype "passive"))
      (node (ref "C1") (pin "+") (pinfunction "+_+") (pintype "passive"))
      (node (ref "LED1") (pin "P$12") (pinfunction "AN_P$12") (pintype "bidirectional"))
      (node (ref "LED1") (pin "P$17") (pinfunction "AN_P$17") (pintype "bidirectional"))
      (node (ref "LED1") (pin "P$4") (pinfunction "AN_P$4") (pintype "bidirectional"))
      (node (ref "LED10") (pin "P$12") (pinfunction "AN_P$12") (pintype "bidirectional"))
      (node (ref "LED10") (pin "P$17") (pinfunction "AN_P$17") (pintype "bidirectional"))
      (node (ref "LED10") (pin "P$4") (pinfunction "AN_P$4") (pintype "bidirectional"))
      (node (ref "LED11") (pin "P$12") (pinfunction "AN_P$12") (pintype "bidirectional"))
      (node (ref "LED11") (pin "P$17") (pinfunction "AN_P$17") (pintype "bidirectional"))
      (node (ref "LED12") (pin "P$12") (pinfunction "AN_P$12") (pintype "bidirectional"))
      (node (ref "LED12") (pin "P$17") (pinfunction "AN_P$17") (pintype "bidirectional"))
      (node (ref "LED13") (pin "P$12") (pinfunction "AN_P$12") (pintype "bidirectional"))
      (node (ref "LED13") (pin "P$17") (pinfunction "AN_P$17") (pintype "bidirectional"))
      (node (ref "LED2") (pin "P$12") (pinfunction "AN_P$12") (pintype "bidirectional"))
      (node (ref "LED2") (pin "P$17") (pinfunction "AN_P$17") (pintype "bidirectional"))
      (node (ref "LED2") (pin "P$4") (pinfunction "AN_P$4") (pintype "bidirectional"))
      (node (ref "LED3") (pin "P$12") (pinfunction "AN_P$12") (pintype "bidirectional"))
      (node (ref "LED3") (pin "P$17") (pinfunction "AN_P$17") (pintype "bidirectional"))
      (node (ref "LED3") (pin "P$4") (pinfunction "AN_P$4") (pintype "bidirectional"))
      (node (ref "LED4") (pin "P$12") (pinfunction "AN_P$12") (pintype "bidirectional"))
      (node (ref "LED4") (pin "P$17") (pinfunction "AN_P$17") (pintype "bidirectional"))
      (node (ref "LED4") (pin "P$4") (pinfunction "AN_P$4") (pintype "bidirectional"))
      (node (ref "LED5") (pin "P$12") (pinfunction "AN_P$12") (pintype "bidirectional"))
      (node (ref "LED5") (pin "P$17") (pinfunction "AN_P$17") (pintype "bidirectional"))
      (node (ref "LED5") (pin "P$4") (pinfunction "AN_P$4") (pintype "bidirectional"))
      (node (ref "LED6") (pin "P$12") (pinfunction "AN_P$12") (pintype "bidirectional"))
      (node (ref "LED6") (pin "P$17") (pinfunction "AN_P$17") (pintype "bidirectional"))
      (node (ref "LED6") (pin "P$4") (pinfunction "AN_P$4") (pintype "bidirectional"))
      (node (ref "LED7") (pin "P$12") (pinfunction "AN_P$12") (pintype "bidirectional"))
      (node (ref "LED7") (pin "P$17") (pinfunction "AN_P$17") (pintype "bidirectional"))
      (node (ref "LED8") (pin "P$12") (pinfunction "AN_P$12") (pintype "bidirectional"))
      (node (ref "LED8") (pin "P$17") (pinfunction "AN_P$17") (pintype "bidirectional"))
      (node (ref "LED9") (pin "P$12") (pinfunction "AN_P$12") (pintype "bidirectional"))
      (node (ref "LED9") (pin "P$17") (pinfunction "AN_P$17") (pintype "bidirectional"))
      (node (ref "LED9") (pin "P$4") (pinfunction "AN_P$4") (pintype "bidirectional"))
    )
    (net (code "332") (name "VSS") (class "Default")
      (node (ref "A_BUS") (pin "37") (pinfunction "37_37") (pintype "passive"))
      (node (ref "A_BUS") (pin "39") (pinfunction "39_39") (pintype "passive"))
      (node (ref "C1") (pin "-") (pinfunction "-_-") (pintype "passive"))
      (node (ref "Q1") (pin "1") (pinfunction "S_1") (pintype "passive"))
      (node (ref "Q10") (pin "1") (pinfunction "S_1") (pintype "passive"))
      (node (ref "Q100") (pin "1") (pinfunction "S_1") (pintype "passive"))
      (node (ref "Q101") (pin "1") (pinfunction "S_1") (pintype "passive"))
      (node (ref "Q102") (pin "1") (pinfunction "S_1") (pintype "passive"))
      (node (ref "Q11") (pin "1") (pinfunction "S_1") (pintype "passive"))
      (node (ref "Q12") (pin "1") (pinfunction "S_1") (pintype "passive"))
      (node (ref "Q13") (pin "1") (pinfunction "S_1") (pintype "passive"))
      (node (ref "Q14") (pin "1") (pinfunction "S_1") (pintype "passive"))
      (node (ref "Q15") (pin "1") (pinfunction "S_1") (pintype "passive"))
      (node (ref "Q16") (pin "1") (pinfunction "S_1") (pintype "passive"))
      (node (ref "Q17") (pin "1") (pinfunction "S_1") (pintype "passive"))
      (node (ref "Q18") (pin "1") (pinfunction "S_1") (pintype "passive"))
      (node (ref "Q19") (pin "1") (pinfunction "S_1") (pintype "passive"))
      (node (ref "Q2") (pin "1") (pinfunction "S_1") (pintype "passive"))
      (node (ref "Q20") (pin "1") (pinfunction "S_1") (pintype "passive"))
      (node (ref "Q21") (pin "1") (pinfunction "S_1") (pintype "passive"))
      (node (ref "Q22") (pin "1") (pinfunction "S_1") (pintype "passive"))
      (node (ref "Q23") (pin "1") (pinfunction "S_1") (pintype "passive"))
      (node (ref "Q24") (pin "1") (pinfunction "S_1") (pintype "passive"))
      (node (ref "Q25") (pin "1") (pinfunction "S_1") (pintype "passive"))
      (node (ref "Q26") (pin "1") (pinfunction "S_1") (pintype "passive"))
      (node (ref "Q27") (pin "1") (pinfunction "S_1") (pintype "passive"))
      (node (ref "Q28") (pin "1") (pinfunction "S_1") (pintype "passive"))
      (node (ref "Q29") (pin "1") (pinfunction "S_1") (pintype "passive"))
      (node (ref "Q3") (pin "1") (pinfunction "S_1") (pintype "passive"))
      (node (ref "Q30") (pin "1") (pinfunction "S_1") (pintype "passive"))
      (node (ref "Q31") (pin "1") (pinfunction "S_1") (pintype "passive"))
      (node (ref "Q32") (pin "1") (pinfunction "S_1") (pintype "passive"))
      (node (ref "Q33") (pin "1") (pinfunction "S_1") (pintype "passive"))
      (node (ref "Q34") (pin "1") (pinfunction "S_1") (pintype "passive"))
      (node (ref "Q35") (pin "1") (pinfunction "S_1") (pintype "passive"))
      (node (ref "Q36") (pin "1") (pinfunction "S_1") (pintype "passive"))
      (node (ref "Q37") (pin "1") (pinfunction "S_1") (pintype "passive"))
      (node (ref "Q38") (pin "1") (pinfunction "S_1") (pintype "passive"))
      (node (ref "Q39") (pin "1") (pinfunction "S_1") (pintype "passive"))
      (node (ref "Q4") (pin "1") (pinfunction "S_1") (pintype "passive"))
      (node (ref "Q40") (pin "1") (pinfunction "S_1") (pintype "passive"))
      (node (ref "Q41") (pin "1") (pinfunction "S_1") (pintype "passive"))
      (node (ref "Q42") (pin "1") (pinfunction "S_1") (pintype "passive"))
      (node (ref "Q43") (pin "1") (pinfunction "S_1") (pintype "passive"))
      (node (ref "Q44") (pin "1") (pinfunction "S_1") (pintype "passive"))
      (node (ref "Q45") (pin "1") (pinfunction "S_1") (pintype "passive"))
      (node (ref "Q46") (pin "1") (pinfunction "S_1") (pintype "passive"))
      (node (ref "Q47") (pin "1") (pinfunction "S_1") (pintype "passive"))
      (node (ref "Q48") (pin "1") (pinfunction "S_1") (pintype "passive"))
      (node (ref "Q49") (pin "1") (pinfunction "S_1") (pintype "passive"))
      (node (ref "Q5") (pin "1") (pinfunction "S_1") (pintype "passive"))
      (node (ref "Q50") (pin "1") (pinfunction "S_1") (pintype "passive"))
      (node (ref "Q51") (pin "1") (pinfunction "S_1") (pintype "passive"))
      (node (ref "Q52") (pin "1") (pinfunction "S_1") (pintype "passive"))
      (node (ref "Q53") (pin "1") (pinfunction "S_1") (pintype "passive"))
      (node (ref "Q54") (pin "1") (pinfunction "S_1") (pintype "passive"))
      (node (ref "Q55") (pin "1") (pinfunction "S_1") (pintype "passive"))
      (node (ref "Q56") (pin "1") (pinfunction "S_1") (pintype "passive"))
      (node (ref "Q57") (pin "1") (pinfunction "S_1") (pintype "passive"))
      (node (ref "Q58") (pin "1") (pinfunction "S_1") (pintype "passive"))
      (node (ref "Q59") (pin "1") (pinfunction "S_1") (pintype "passive"))
      (node (ref "Q6") (pin "1") (pinfunction "S_1") (pintype "passive"))
      (node (ref "Q60") (pin "1") (pinfunction "S_1") (pintype "passive"))
      (node (ref "Q61") (pin "1") (pinfunction "S_1") (pintype "passive"))
      (node (ref "Q62") (pin "1") (pinfunction "S_1") (pintype "passive"))
      (node (ref "Q63") (pin "1") (pinfunction "S_1") (pintype "passive"))
      (node (ref "Q64") (pin "1") (pinfunction "S_1") (pintype "passive"))
      (node (ref "Q65") (pin "1") (pinfunction "S_1") (pintype "passive"))
      (node (ref "Q66") (pin "1") (pinfunction "S_1") (pintype "passive"))
      (node (ref "Q67") (pin "1") (pinfunction "S_1") (pintype "passive"))
      (node (ref "Q68") (pin "1") (pinfunction "S_1") (pintype "passive"))
      (node (ref "Q69") (pin "1") (pinfunction "S_1") (pintype "passive"))
      (node (ref "Q7") (pin "1") (pinfunction "S_1") (pintype "passive"))
      (node (ref "Q70") (pin "1") (pinfunction "S_1") (pintype "passive"))
      (node (ref "Q71") (pin "1") (pinfunction "S_1") (pintype "passive"))
      (node (ref "Q72") (pin "1") (pinfunction "S_1") (pintype "passive"))
      (node (ref "Q73") (pin "1") (pinfunction "S_1") (pintype "passive"))
      (node (ref "Q74") (pin "1") (pinfunction "S_1") (pintype "passive"))
      (node (ref "Q75") (pin "1") (pinfunction "S_1") (pintype "passive"))
      (node (ref "Q76") (pin "1") (pinfunction "S_1") (pintype "passive"))
      (node (ref "Q77") (pin "1") (pinfunction "S_1") (pintype "passive"))
      (node (ref "Q78") (pin "1") (pinfunction "S_1") (pintype "passive"))
      (node (ref "Q79") (pin "1") (pinfunction "S_1") (pintype "passive"))
      (node (ref "Q8") (pin "1") (pinfunction "S_1") (pintype "passive"))
      (node (ref "Q80") (pin "1") (pinfunction "S_1") (pintype "passive"))
      (node (ref "Q81") (pin "1") (pinfunction "S_1") (pintype "passive"))
      (node (ref "Q82") (pin "1") (pinfunction "S_1") (pintype "passive"))
      (node (ref "Q83") (pin "1") (pinfunction "S_1") (pintype "passive"))
      (node (ref "Q84") (pin "1") (pinfunction "S_1") (pintype "passive"))
      (node (ref "Q85") (pin "1") (pinfunction "S_1") (pintype "passive"))
      (node (ref "Q86") (pin "1") (pinfunction "S_1") (pintype "passive"))
      (node (ref "Q87") (pin "1") (pinfunction "S_1") (pintype "passive"))
      (node (ref "Q88") (pin "1") (pinfunction "S_1") (pintype "passive"))
      (node (ref "Q89") (pin "1") (pinfunction "S_1") (pintype "passive"))
      (node (ref "Q9") (pin "1") (pinfunction "S_1") (pintype "passive"))
      (node (ref "Q90") (pin "1") (pinfunction "S_1") (pintype "passive"))
      (node (ref "Q91") (pin "1") (pinfunction "S_1") (pintype "passive"))
      (node (ref "Q92") (pin "1") (pinfunction "S_1") (pintype "passive"))
      (node (ref "Q93") (pin "1") (pinfunction "S_1") (pintype "passive"))
      (node (ref "Q94") (pin "1") (pinfunction "S_1") (pintype "passive"))
      (node (ref "Q95") (pin "1") (pinfunction "S_1") (pintype "passive"))
      (node (ref "Q96") (pin "1") (pinfunction "S_1") (pintype "passive"))
      (node (ref "Q97") (pin "1") (pinfunction "S_1") (pintype "passive"))
      (node (ref "Q98") (pin "1") (pinfunction "S_1") (pintype "passive"))
      (node (ref "Q99") (pin "1") (pinfunction "S_1") (pintype "passive"))
    )
    (net (code "333") (name "unconnected-(A_BUS-Pad1)") (class "Default")
      (node (ref "A_BUS") (pin "1") (pinfunction "1_1") (pintype "passive"))
    )
    (net (code "334") (name "unconnected-(A_BUS-Pad2)") (class "Default")
      (node (ref "A_BUS") (pin "2") (pinfunction "2_2") (pintype "passive"))
    )
    (net (code "335") (name "unconnected-(A_BUS-Pad3)") (class "Default")
      (node (ref "A_BUS") (pin "3") (pinfunction "3_3") (pintype "passive"))
    )
    (net (code "336") (name "unconnected-(A_BUS-Pad4)") (class "Default")
      (node (ref "A_BUS") (pin "4") (pinfunction "4_4") (pintype "passive"))
    )
    (net (code "337") (name "unconnected-(A_BUS-Pad5)") (class "Default")
      (node (ref "A_BUS") (pin "5") (pinfunction "5_5") (pintype "passive"))
    )
    (net (code "338") (name "unconnected-(A_BUS-Pad6)") (class "Default")
      (node (ref "A_BUS") (pin "6") (pinfunction "6_6") (pintype "passive"))
    )
    (net (code "339") (name "unconnected-(A_BUS-Pad7)") (class "Default")
      (node (ref "A_BUS") (pin "7") (pinfunction "7_7") (pintype "passive"))
    )
    (net (code "340") (name "unconnected-(A_BUS-Pad8)") (class "Default")
      (node (ref "A_BUS") (pin "8") (pinfunction "8_8") (pintype "passive"))
    )
    (net (code "341") (name "unconnected-(A_BUS-Pad9)") (class "Default")
      (node (ref "A_BUS") (pin "9") (pinfunction "9_9") (pintype "passive"))
    )
    (net (code "342") (name "unconnected-(A_BUS-Pad10)") (class "Default")
      (node (ref "A_BUS") (pin "10") (pinfunction "10_10") (pintype "passive"))
    )
    (net (code "343") (name "unconnected-(A_BUS-Pad11)") (class "Default")
      (node (ref "A_BUS") (pin "11") (pinfunction "11_11") (pintype "passive"))
    )
    (net (code "344") (name "unconnected-(A_BUS-Pad12)") (class "Default")
      (node (ref "A_BUS") (pin "12") (pinfunction "12_12") (pintype "passive"))
    )
    (net (code "345") (name "unconnected-(A_BUS-Pad13)") (class "Default")
      (node (ref "A_BUS") (pin "13") (pinfunction "13_13") (pintype "passive"))
    )
    (net (code "346") (name "unconnected-(A_BUS-Pad14)") (class "Default")
      (node (ref "A_BUS") (pin "14") (pinfunction "14_14") (pintype "passive"))
    )
    (net (code "347") (name "unconnected-(A_BUS-Pad15)") (class "Default")
      (node (ref "A_BUS") (pin "15") (pinfunction "15_15") (pintype "passive"))
    )
    (net (code "348") (name "unconnected-(A_BUS-Pad16)") (class "Default")
      (node (ref "A_BUS") (pin "16") (pinfunction "16_16") (pintype "passive"))
    )
    (net (code "349") (name "unconnected-(A_BUS-Pad17)") (class "Default")
      (node (ref "A_BUS") (pin "17") (pinfunction "17_17") (pintype "passive"))
    )
    (net (code "350") (name "unconnected-(A_BUS-Pad18)") (class "Default")
      (node (ref "A_BUS") (pin "18") (pinfunction "18_18") (pintype "passive"))
    )
    (net (code "351") (name "unconnected-(A_BUS-Pad19)") (class "Default")
      (node (ref "A_BUS") (pin "19") (pinfunction "19_19") (pintype "passive"))
    )
    (net (code "352") (name "unconnected-(A_BUS-Pad20)") (class "Default")
      (node (ref "A_BUS") (pin "20") (pinfunction "20_20") (pintype "passive"))
    )
    (net (code "353") (name "unconnected-(A_BUS-Pad21)") (class "Default")
      (node (ref "A_BUS") (pin "21") (pinfunction "21_21") (pintype "passive"))
    )
    (net (code "354") (name "unconnected-(A_BUS-Pad22)") (class "Default")
      (node (ref "A_BUS") (pin "22") (pinfunction "22_22") (pintype "passive"))
    )
    (net (code "355") (name "unconnected-(A_BUS-Pad23)") (class "Default")
      (node (ref "A_BUS") (pin "23") (pinfunction "23_23") (pintype "passive"))
    )
    (net (code "356") (name "unconnected-(A_BUS-Pad24)") (class "Default")
      (node (ref "A_BUS") (pin "24") (pinfunction "24_24") (pintype "passive"))
    )
    (net (code "357") (name "unconnected-(A_BUS-Pad25)") (class "Default")
      (node (ref "A_BUS") (pin "25") (pinfunction "25_25") (pintype "passive"))
    )
    (net (code "358") (name "unconnected-(A_BUS-Pad26)") (class "Default")
      (node (ref "A_BUS") (pin "26") (pinfunction "26_26") (pintype "passive"))
    )
    (net (code "359") (name "unconnected-(A_BUS-Pad27)") (class "Default")
      (node (ref "A_BUS") (pin "27") (pinfunction "27_27") (pintype "passive"))
    )
    (net (code "360") (name "unconnected-(A_BUS-Pad29)") (class "Default")
      (node (ref "A_BUS") (pin "29") (pinfunction "29_29") (pintype "passive"))
    )
    (net (code "361") (name "unconnected-(A_BUS-Pad30)") (class "Default")
      (node (ref "A_BUS") (pin "30") (pinfunction "30_30") (pintype "passive"))
    )
    (net (code "362") (name "unconnected-(A_BUS-Pad31)") (class "Default")
      (node (ref "A_BUS") (pin "31") (pinfunction "31_31") (pintype "passive"))
    )
    (net (code "363") (name "unconnected-(A_BUS-Pad32)") (class "Default")
      (node (ref "A_BUS") (pin "32") (pinfunction "32_32") (pintype "passive"))
    )
    (net (code "364") (name "unconnected-(A_BUS-Pad33)") (class "Default")
      (node (ref "A_BUS") (pin "33") (pinfunction "33_33") (pintype "passive"))
    )
    (net (code "365") (name "unconnected-(A_BUS-Pad34)") (class "Default")
      (node (ref "A_BUS") (pin "34") (pinfunction "34_34") (pintype "passive"))
    )
    (net (code "366") (name "unconnected-(A_BUS-Pad35)") (class "Default")
      (node (ref "A_BUS") (pin "35") (pinfunction "35_35") (pintype "passive"))
    )
    (net (code "367") (name "unconnected-(B_BUS-Pad1)") (class "Default")
      (node (ref "B_BUS") (pin "1") (pinfunction "1_1") (pintype "passive"))
    )
    (net (code "368") (name "unconnected-(B_BUS-Pad2)") (class "Default")
      (node (ref "B_BUS") (pin "2") (pinfunction "2_2") (pintype "passive"))
    )
    (net (code "369") (name "unconnected-(B_BUS-Pad3)") (class "Default")
      (node (ref "B_BUS") (pin "3") (pinfunction "3_3") (pintype "passive"))
    )
    (net (code "370") (name "unconnected-(B_BUS-Pad4)") (class "Default")
      (node (ref "B_BUS") (pin "4") (pinfunction "4_4") (pintype "passive"))
    )
    (net (code "371") (name "unconnected-(B_BUS-Pad5)") (class "Default")
      (node (ref "B_BUS") (pin "5") (pinfunction "5_5") (pintype "passive"))
    )
    (net (code "372") (name "unconnected-(B_BUS-Pad6)") (class "Default")
      (node (ref "B_BUS") (pin "6") (pinfunction "6_6") (pintype "passive"))
    )
    (net (code "373") (name "unconnected-(B_BUS-Pad7)") (class "Default")
      (node (ref "B_BUS") (pin "7") (pinfunction "7_7") (pintype "passive"))
    )
    (net (code "374") (name "unconnected-(B_BUS-Pad8)") (class "Default")
      (node (ref "B_BUS") (pin "8") (pinfunction "8_8") (pintype "passive"))
    )
    (net (code "375") (name "unconnected-(B_BUS-Pad9)") (class "Default")
      (node (ref "B_BUS") (pin "9") (pinfunction "9_9") (pintype "passive"))
    )
    (net (code "376") (name "unconnected-(B_BUS-Pad10)") (class "Default")
      (node (ref "B_BUS") (pin "10") (pinfunction "10_10") (pintype "passive"))
    )
    (net (code "377") (name "unconnected-(B_BUS-Pad11)") (class "Default")
      (node (ref "B_BUS") (pin "11") (pinfunction "11_11") (pintype "passive"))
    )
    (net (code "378") (name "unconnected-(B_BUS-Pad12)") (class "Default")
      (node (ref "B_BUS") (pin "12") (pinfunction "12_12") (pintype "passive"))
    )
    (net (code "379") (name "unconnected-(B_BUS-Pad13)") (class "Default")
      (node (ref "B_BUS") (pin "13") (pinfunction "13_13") (pintype "passive"))
    )
    (net (code "380") (name "unconnected-(C_BUS-Pad36)") (class "Default")
      (node (ref "C_BUS") (pin "36") (pinfunction "36_36") (pintype "passive"))
    )
    (net (code "381") (name "unconnected-(C_BUS-Pad37)") (class "Default")
      (node (ref "C_BUS") (pin "37") (pinfunction "37_37") (pintype "passive"))
    )
    (net (code "382") (name "unconnected-(C_BUS-Pad38)") (class "Default")
      (node (ref "C_BUS") (pin "38") (pinfunction "38_38") (pintype "passive"))
    )
    (net (code "383") (name "unconnected-(C_BUS-Pad39)") (class "Default")
      (node (ref "C_BUS") (pin "39") (pinfunction "39_39") (pintype "passive"))
    )
    (net (code "384") (name "unconnected-(C_BUS-Pad40)") (class "Default")
      (node (ref "C_BUS") (pin "40") (pinfunction "40_40") (pintype "passive"))
    )
    (net (code "385") (name "unconnected-(D_BUS-Pad40)") (class "Default")
      (node (ref "D_BUS") (pin "40") (pinfunction "40_40") (pintype "passive"))
    )
    (net (code "386") (name "unconnected-(LED1-DP-PadP$10)") (class "Default")
      (node (ref "LED1") (pin "P$10") (pinfunction "DP_P$10") (pintype "bidirectional"))
    )
    (net (code "387") (name "unconnected-(LED2-DP-PadP$10)") (class "Default")
      (node (ref "LED2") (pin "P$10") (pinfunction "DP_P$10") (pintype "bidirectional"))
    )
    (net (code "388") (name "unconnected-(LED3-DP-PadP$10)") (class "Default")
      (node (ref "LED3") (pin "P$10") (pinfunction "DP_P$10") (pintype "bidirectional"))
    )
    (net (code "389") (name "unconnected-(LED4-DP-PadP$10)") (class "Default")
      (node (ref "LED4") (pin "P$10") (pinfunction "DP_P$10") (pintype "bidirectional"))
    )
    (net (code "390") (name "unconnected-(LED5-DP-PadP$10)") (class "Default")
      (node (ref "LED5") (pin "P$10") (pinfunction "DP_P$10") (pintype "bidirectional"))
    )
    (net (code "391") (name "unconnected-(LED6-DP-PadP$10)") (class "Default")
      (node (ref "LED6") (pin "P$10") (pinfunction "DP_P$10") (pintype "bidirectional"))
    )
    (net (code "392") (name "unconnected-(LED8-K-PadP$4)") (class "Default")
      (node (ref "LED8") (pin "P$4") (pinfunction "K_P$4") (pintype "bidirectional"))
    )
    (net (code "393") (name "unconnected-(LED8-M-PadP$6)") (class "Default")
      (node (ref "LED8") (pin "P$6") (pinfunction "M_P$6") (pintype "bidirectional"))
    )
    (net (code "394") (name "unconnected-(LED8-N-PadP$18)") (class "Default")
      (node (ref "LED8") (pin "P$18") (pinfunction "N_P$18") (pintype "bidirectional"))
    )
    (net (code "395") (name "unconnected-(LED8-S-PadP$7)") (class "Default")
      (node (ref "LED8") (pin "P$7") (pinfunction "S_P$7") (pintype "bidirectional"))
    )
    (net (code "396") (name "unconnected-(LED8-T-PadP$8)") (class "Default")
      (node (ref "LED8") (pin "P$8") (pinfunction "T_P$8") (pintype "bidirectional"))
    )
    (net (code "397") (name "unconnected-(LED9-DP-PadP$10)") (class "Default")
      (node (ref "LED9") (pin "P$10") (pinfunction "DP_P$10") (pintype "bidirectional"))
    )
    (net (code "398") (name "unconnected-(LED11-T-PadP$8)") (class "Default")
      (node (ref "LED11") (pin "P$8") (pinfunction "T_P$8") (pintype "bidirectional"))
    )
    (net (code "399") (name "unconnected-(LED12-K-PadP$4)") (class "Default")
      (node (ref "LED12") (pin "P$4") (pinfunction "K_P$4") (pintype "bidirectional"))
    )
    (net (code "400") (name "unconnected-(LED12-M-PadP$6)") (class "Default")
      (node (ref "LED12") (pin "P$6") (pinfunction "M_P$6") (pintype "bidirectional"))
    )
    (net (code "401") (name "unconnected-(LED12-N-PadP$18)") (class "Default")
      (node (ref "LED12") (pin "P$18") (pinfunction "N_P$18") (pintype "bidirectional"))
    )
    (net (code "402") (name "unconnected-(LED12-R-PadP$9)") (class "Default")
      (node (ref "LED12") (pin "P$9") (pinfunction "R_P$9") (pintype "bidirectional"))
    )
    (net (code "403") (name "unconnected-(LED12-S-PadP$7)") (class "Default")
      (node (ref "LED12") (pin "P$7") (pinfunction "S_P$7") (pintype "bidirectional"))
    )
    (net (code "404") (name "unconnected-(LED12-T-PadP$8)") (class "Default")
      (node (ref "LED12") (pin "P$8") (pinfunction "T_P$8") (pintype "bidirectional"))
    )
  )
)
